# SMPS.net
KiCad netlist of a schematic drawn in Altium Designer
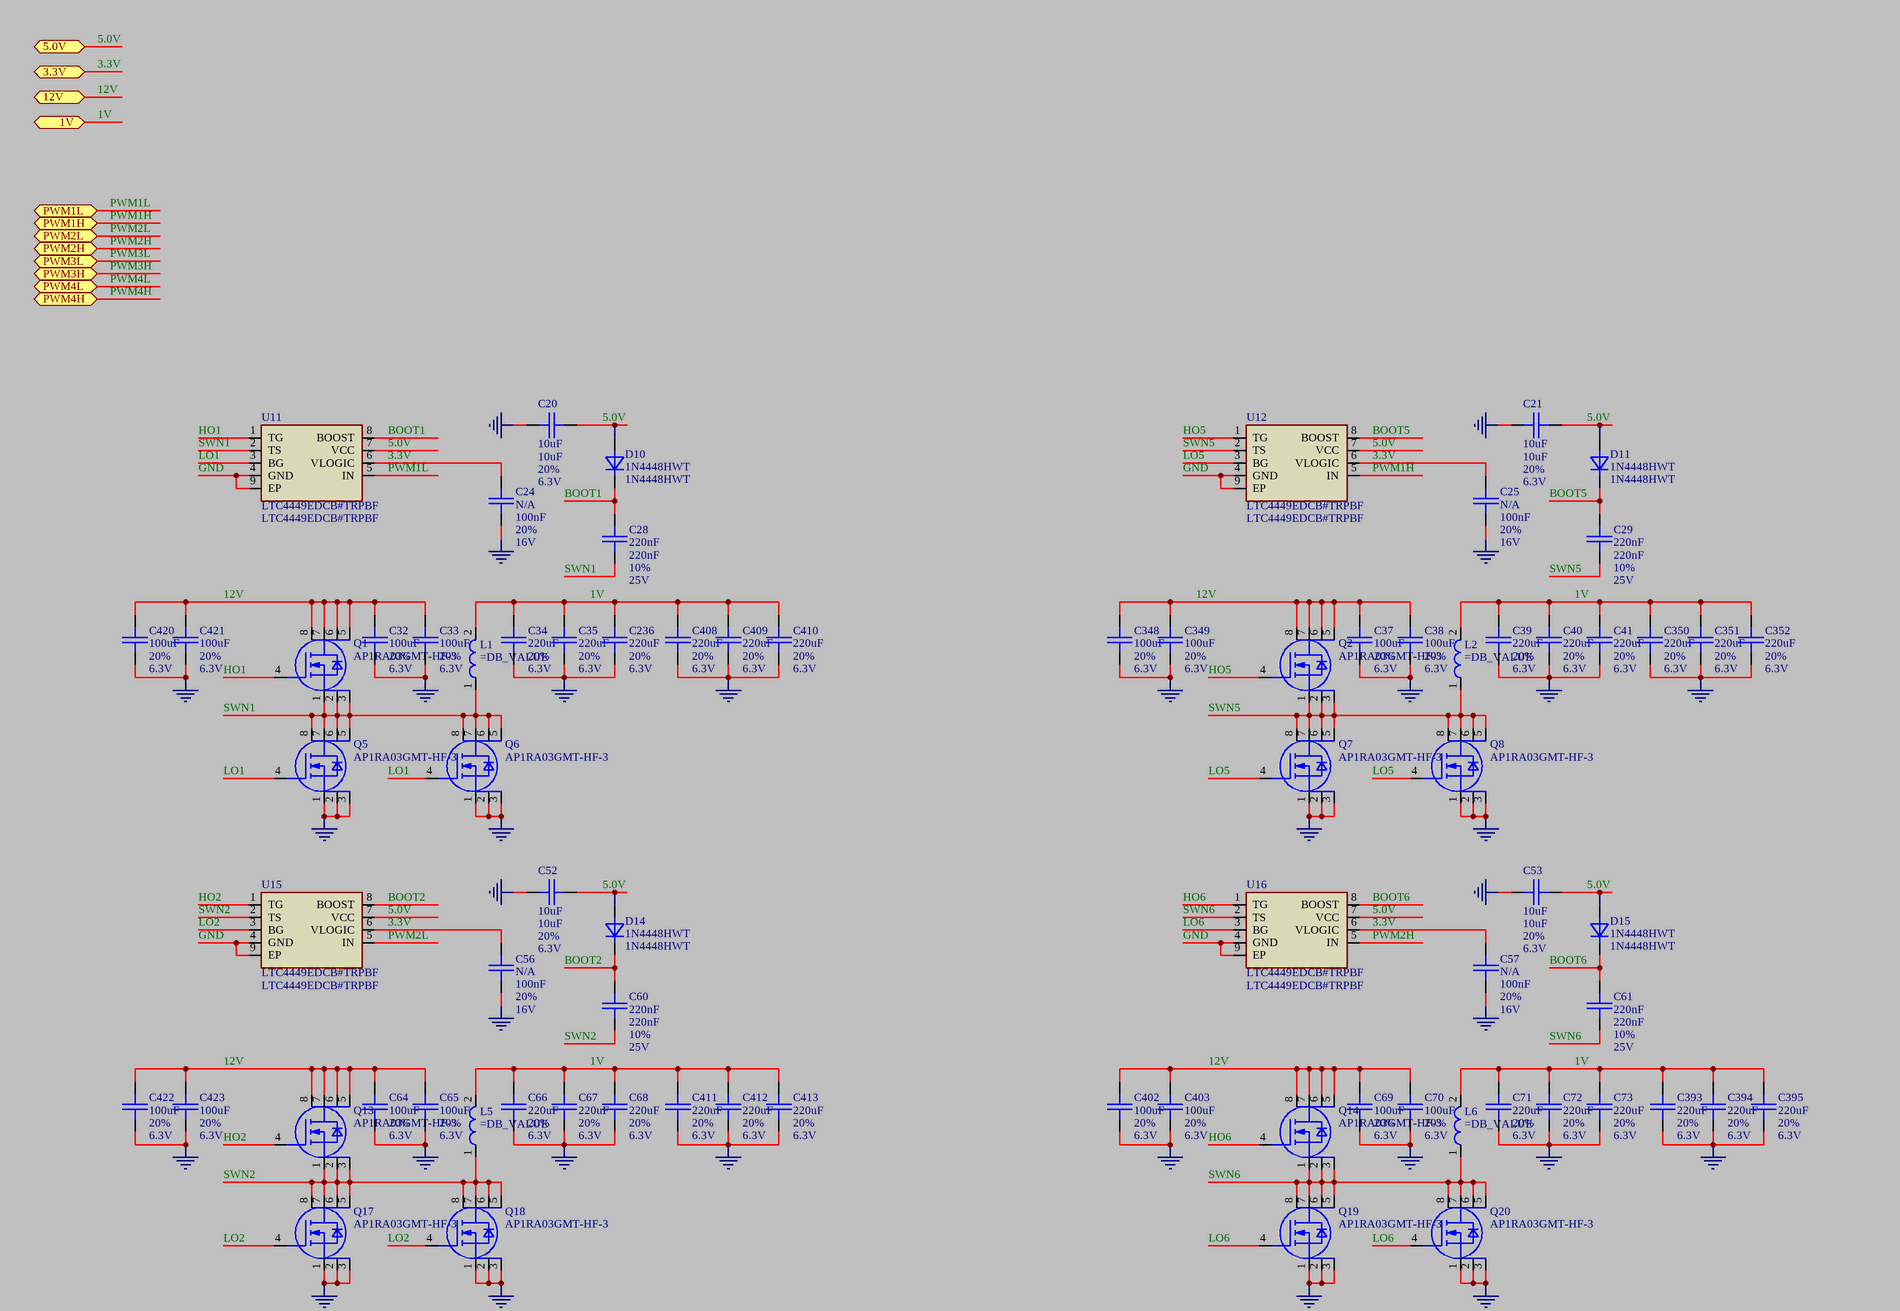
[diagram p0: SMPS.SchDoc, top left]
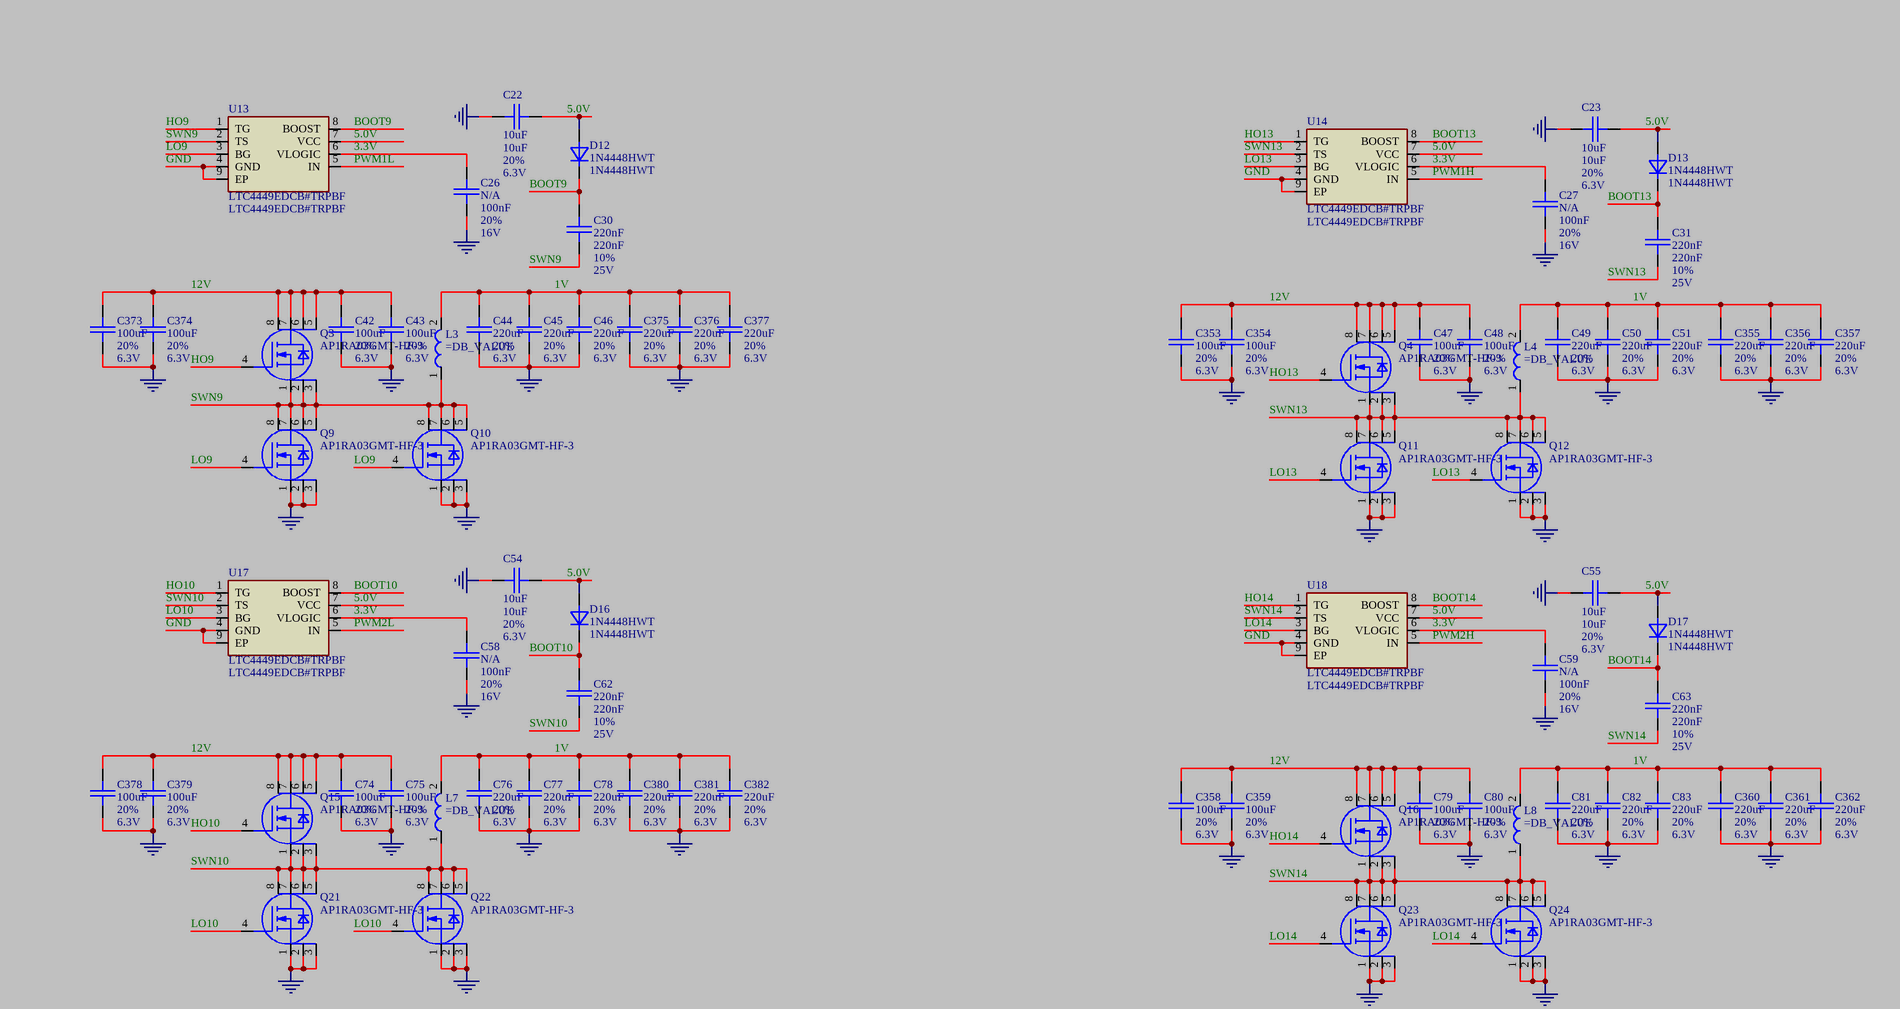
[diagram p1: SMPS.SchDoc, top right]
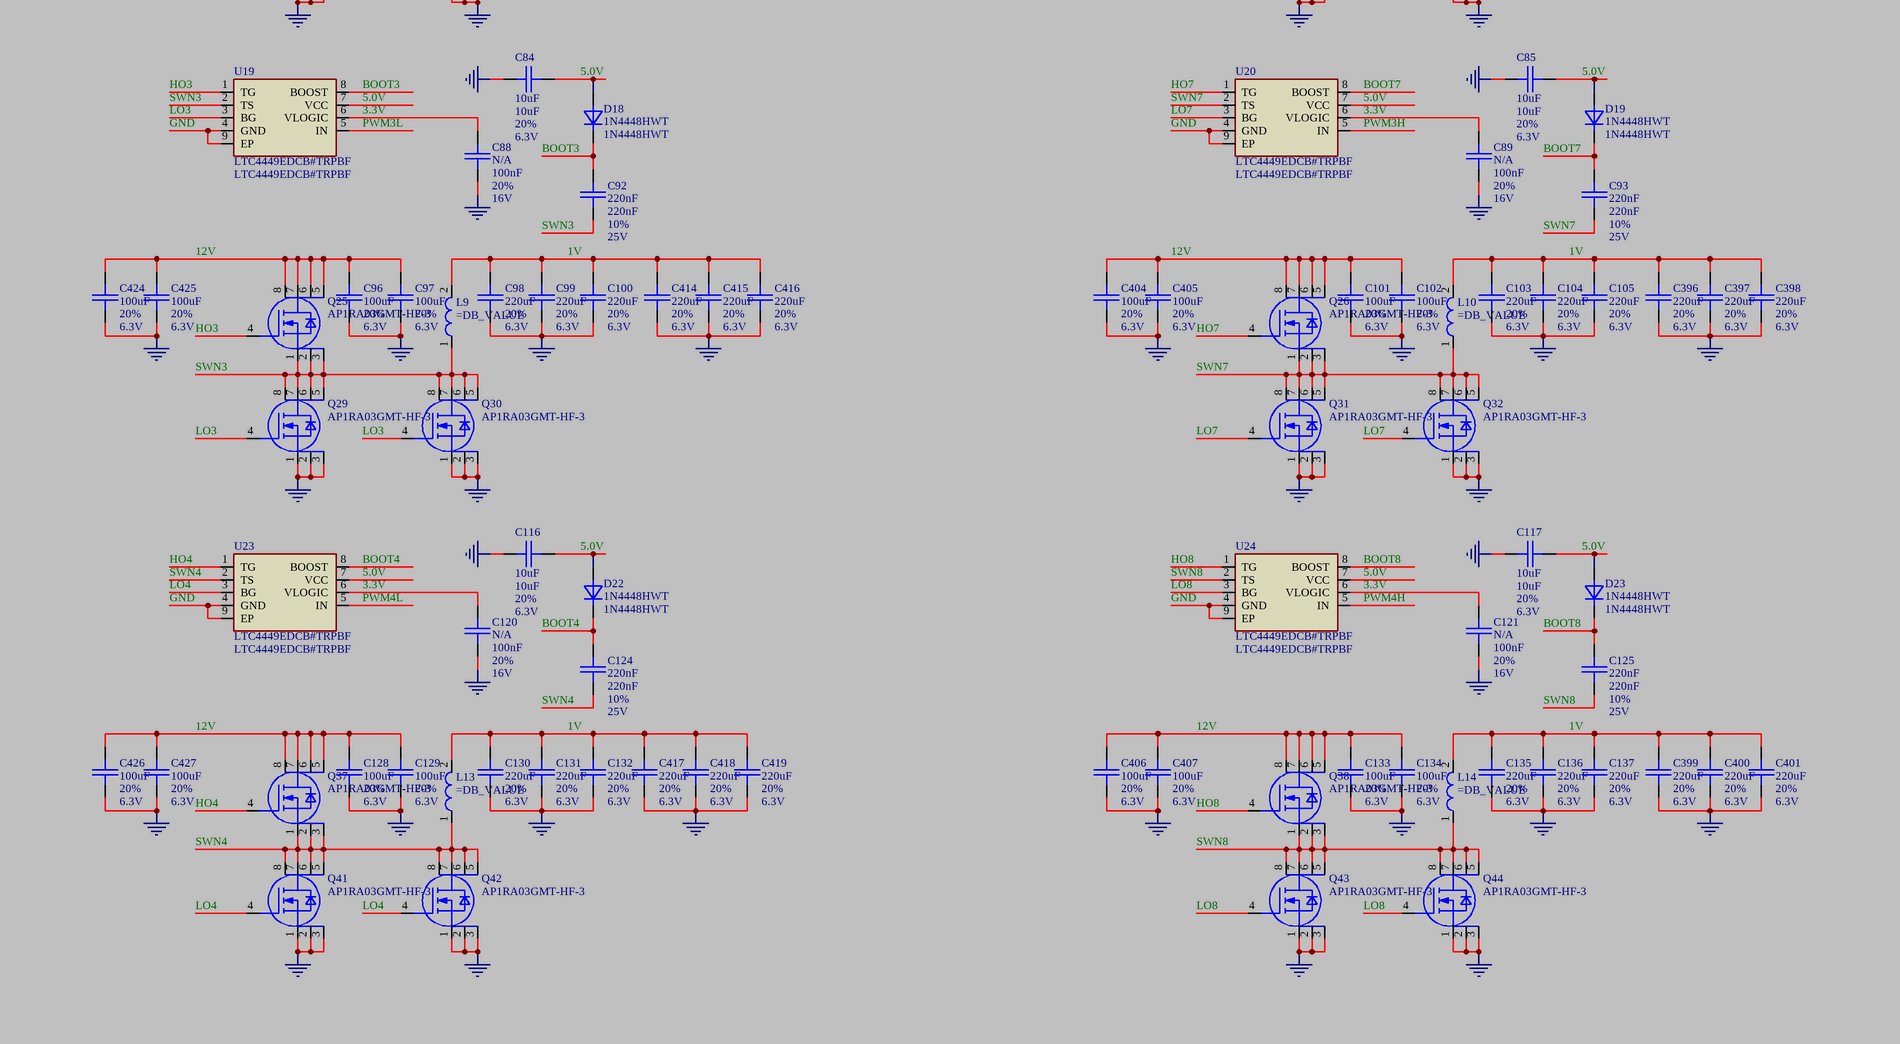
[diagram p2: SMPS.SchDoc, bottom left]
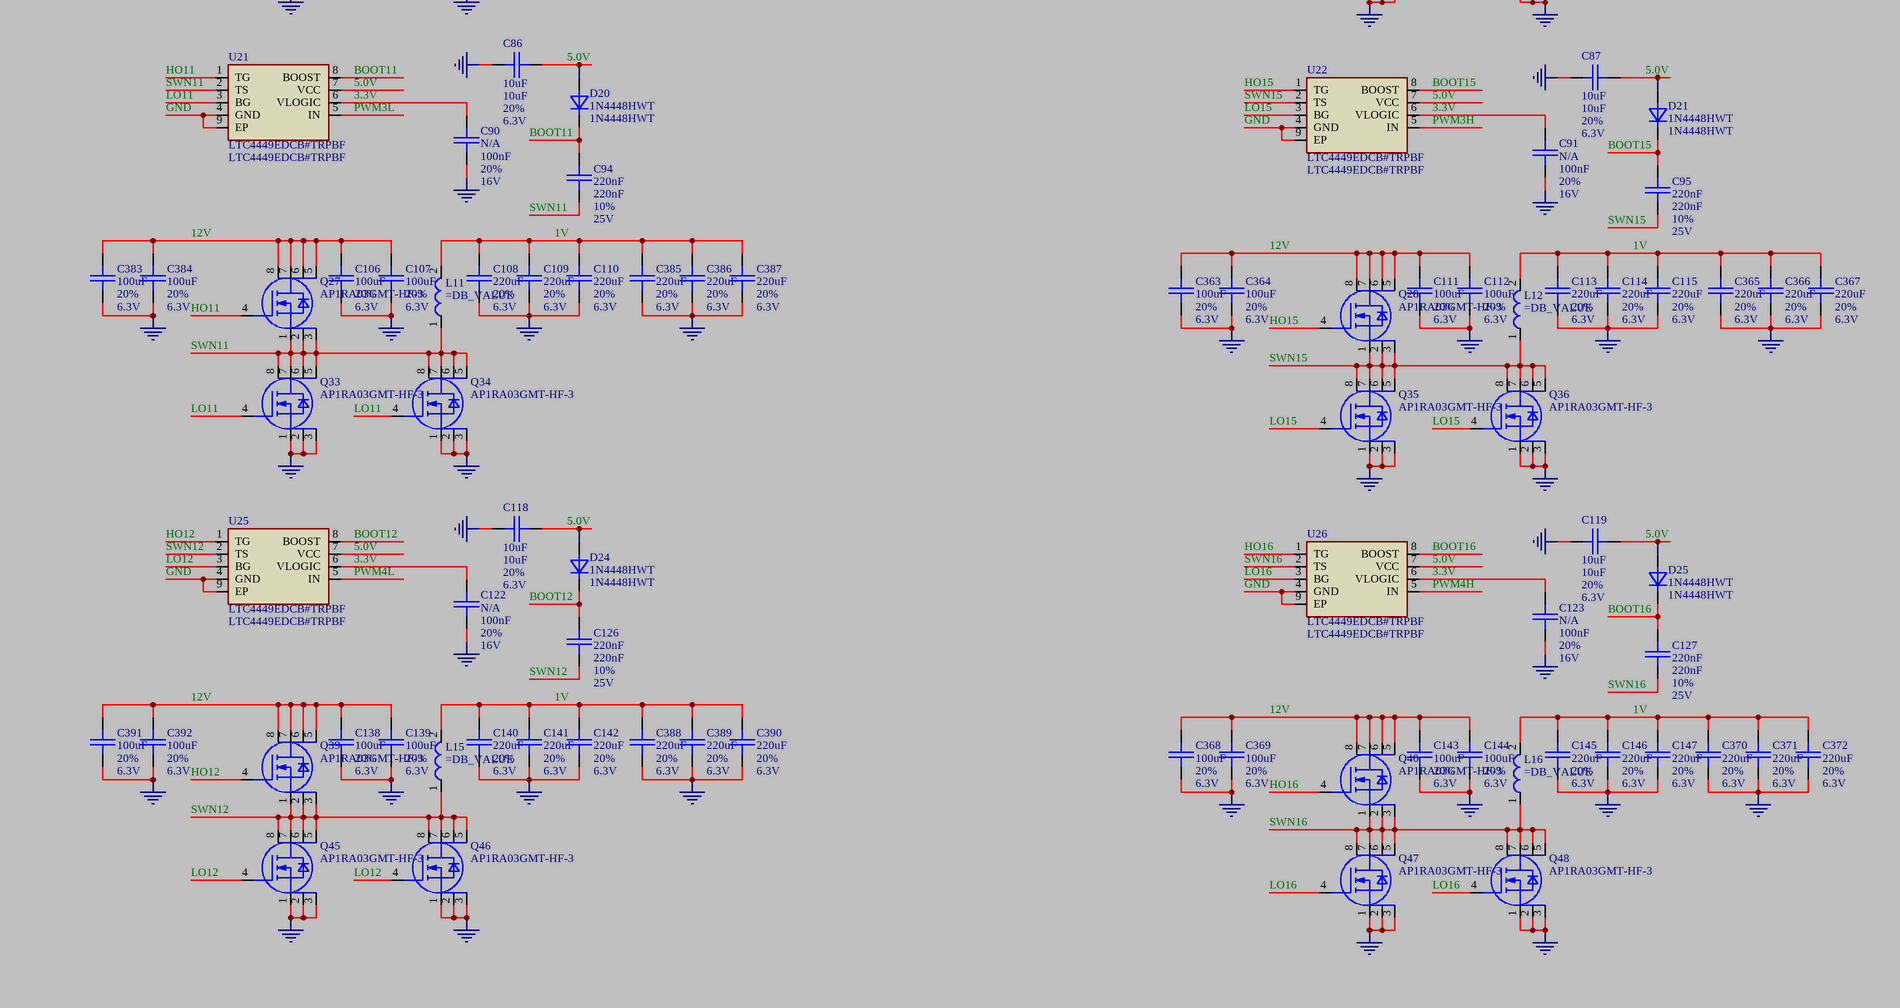
[diagram p3: SMPS.SchDoc, bottom right]

(export (version "E")
  (design (tool "Eeschema 10.0.6"))
  (components
    (comp (ref "C20")
      (value "10uF")
      (footprint "SMD_0603_CAPC1608X95N")
      (fields
        (field (name "DB_PART_NUMBER") "CAP000043646")
        (field (name "DB_VALUE") "10uF")
        (field (name "DB_TOLERANCE") "20%")
        (field (name "DB_VOLTAGE") "6.3V")
        (field (name "DB_MANUFACTURER_PART") "KEMET    C0603C106M9PAC")
      )
      (libsource (lib "Database_Libs1") (part "=DB_VALUE"))
    )
    (comp (ref "C21")
      (value "10uF")
      (footprint "SMD_0603_CAPC1608X95N")
      (fields
        (field (name "DB_PART_NUMBER") "CAP000043646")
        (field (name "DB_VALUE") "10uF")
        (field (name "DB_TOLERANCE") "20%")
        (field (name "DB_VOLTAGE") "6.3V")
        (field (name "DB_MANUFACTURER_PART") "KEMET    C0603C106M9PAC")
      )
      (libsource (lib "Database_Libs1") (part "=DB_VALUE"))
    )
    (comp (ref "C22")
      (value "10uF")
      (footprint "SMD_0603_CAPC1608X95N")
      (fields
        (field (name "DB_PART_NUMBER") "CAP000043646")
        (field (name "DB_VALUE") "10uF")
        (field (name "DB_TOLERANCE") "20%")
        (field (name "DB_VOLTAGE") "6.3V")
        (field (name "DB_MANUFACTURER_PART") "KEMET    C0603C106M9PAC")
      )
      (libsource (lib "Database_Libs1") (part "=DB_VALUE"))
    )
    (comp (ref "C23")
      (value "10uF")
      (footprint "SMD_0603_CAPC1608X95N")
      (fields
        (field (name "DB_PART_NUMBER") "CAP000043646")
        (field (name "DB_VALUE") "10uF")
        (field (name "DB_TOLERANCE") "20%")
        (field (name "DB_VOLTAGE") "6.3V")
        (field (name "DB_MANUFACTURER_PART") "KEMET    C0603C106M9PAC")
      )
      (libsource (lib "Database_Libs1") (part "=DB_VALUE"))
    )
    (comp (ref "C24")
      (value "N/A")
      (footprint "SMD_0402_CAPC1005X55N")
      (fields
        (field (name "DB_PART_NUMBER") "CAP000022751")
        (field (name "DB_VALUE") "100nF")
        (field (name "DB_TOLERANCE") "20%")
        (field (name "DB_VOLTAGE") "16V")
        (field (name "DB_MANUFACTURER_PART") "KEMET    C0402F104M4RAC")
      )
      (libsource (lib "Database_Libs1") (part "=DB_VALUE"))
    )
    (comp (ref "C25")
      (value "N/A")
      (footprint "SMD_0402_CAPC1005X55N")
      (fields
        (field (name "DB_PART_NUMBER") "CAP000022751")
        (field (name "DB_VALUE") "100nF")
        (field (name "DB_TOLERANCE") "20%")
        (field (name "DB_VOLTAGE") "16V")
        (field (name "DB_MANUFACTURER_PART") "KEMET    C0402F104M4RAC")
      )
      (libsource (lib "Database_Libs1") (part "=DB_VALUE"))
    )
    (comp (ref "C26")
      (value "N/A")
      (footprint "SMD_0402_CAPC1005X55N")
      (fields
        (field (name "DB_PART_NUMBER") "CAP000022751")
        (field (name "DB_VALUE") "100nF")
        (field (name "DB_TOLERANCE") "20%")
        (field (name "DB_VOLTAGE") "16V")
        (field (name "DB_MANUFACTURER_PART") "KEMET    C0402F104M4RAC")
      )
      (libsource (lib "Database_Libs1") (part "=DB_VALUE"))
    )
    (comp (ref "C27")
      (value "N/A")
      (footprint "SMD_0402_CAPC1005X55N")
      (fields
        (field (name "DB_PART_NUMBER") "CAP000022751")
        (field (name "DB_VALUE") "100nF")
        (field (name "DB_TOLERANCE") "20%")
        (field (name "DB_VOLTAGE") "16V")
        (field (name "DB_MANUFACTURER_PART") "KEMET    C0402F104M4RAC")
      )
      (libsource (lib "Database_Libs1") (part "=DB_VALUE"))
    )
    (comp (ref "C28")
      (value "220nF")
      (footprint "SMD_0603_CAPC1608X95N")
      (fields
        (field (name "DB_PART_NUMBER") "CAP000022968")
        (field (name "DB_VALUE") "220nF")
        (field (name "DB_TOLERANCE") "10%")
        (field (name "DB_VOLTAGE") "25V")
        (field (name "DB_MANUFACTURER_PART") "KEMET    C0603F224K3RAC")
      )
      (libsource (lib "Database_Libs1") (part "=DB_VALUE"))
    )
    (comp (ref "C29")
      (value "220nF")
      (footprint "SMD_0603_CAPC1608X95N")
      (fields
        (field (name "DB_PART_NUMBER") "CAP000022968")
        (field (name "DB_VALUE") "220nF")
        (field (name "DB_TOLERANCE") "10%")
        (field (name "DB_VOLTAGE") "25V")
        (field (name "DB_MANUFACTURER_PART") "KEMET    C0603F224K3RAC")
      )
      (libsource (lib "Database_Libs1") (part "=DB_VALUE"))
    )
    (comp (ref "C30")
      (value "220nF")
      (footprint "SMD_0603_CAPC1608X95N")
      (fields
        (field (name "DB_PART_NUMBER") "CAP000022968")
        (field (name "DB_VALUE") "220nF")
        (field (name "DB_TOLERANCE") "10%")
        (field (name "DB_VOLTAGE") "25V")
        (field (name "DB_MANUFACTURER_PART") "KEMET    C0603F224K3RAC")
      )
      (libsource (lib "Database_Libs1") (part "=DB_VALUE"))
    )
    (comp (ref "C31")
      (value "220nF")
      (footprint "SMD_0603_CAPC1608X95N")
      (fields
        (field (name "DB_PART_NUMBER") "CAP000022968")
        (field (name "DB_VALUE") "220nF")
        (field (name "DB_TOLERANCE") "10%")
        (field (name "DB_VOLTAGE") "25V")
        (field (name "DB_MANUFACTURER_PART") "KEMET    C0603F224K3RAC")
      )
      (libsource (lib "Database_Libs1") (part "=DB_VALUE"))
    )
    (comp (ref "C32")
      (value "100uF")
      (footprint "SMD_1210_CAPC3225X270N")
      (fields
        (field (name "DB_PART_NUMBER") "CAP000043701")
        (field (name "DB_VALUE") "100uF")
        (field (name "DB_TOLERANCE") "20%")
        (field (name "DB_VOLTAGE") "6.3V")
        (field (name "DB_MANUFACTURER_PART") "KEMET    C1210C107M9PAC")
      )
      (libsource (lib "Database_Libs1") (part "=DB_VALUE"))
    )
    (comp (ref "C33")
      (value "100uF")
      (footprint "SMD_1210_CAPC3225X270N")
      (fields
        (field (name "DB_PART_NUMBER") "CAP000043701")
        (field (name "DB_VALUE") "100uF")
        (field (name "DB_TOLERANCE") "20%")
        (field (name "DB_VOLTAGE") "6.3V")
        (field (name "DB_MANUFACTURER_PART") "KEMET    C1210C107M9PAC")
      )
      (libsource (lib "Database_Libs1") (part "=DB_VALUE"))
    )
    (comp (ref "C34")
      (value "220uF")
      (footprint "SMD_1210_CAPC3225X279N")
      (fields
        (field (name "DB_PART_NUMBER") "CAP000047355")
        (field (name "DB_VALUE") "220uF")
        (field (name "DB_TOLERANCE") "20%")
        (field (name "DB_VOLTAGE") "6.3V")
        (field (name "DB_MANUFACTURER_PART") "SAMSUNG    CL32A227MQVNNNE")
        (field (name "DB_APPROVED_BY") "VSN")
      )
      (libsource (lib "Database_Libs1") (part "=DB_VALUE"))
    )
    (comp (ref "C35")
      (value "220uF")
      (footprint "SMD_1210_CAPC3225X279N")
      (fields
        (field (name "DB_PART_NUMBER") "CAP000047355")
        (field (name "DB_VALUE") "220uF")
        (field (name "DB_TOLERANCE") "20%")
        (field (name "DB_VOLTAGE") "6.3V")
        (field (name "DB_MANUFACTURER_PART") "SAMSUNG    CL32A227MQVNNNE")
        (field (name "DB_APPROVED_BY") "VSN")
      )
      (libsource (lib "Database_Libs1") (part "=DB_VALUE"))
    )
    (comp (ref "C37")
      (value "100uF")
      (footprint "SMD_1210_CAPC3225X270N")
      (fields
        (field (name "DB_PART_NUMBER") "CAP000043701")
        (field (name "DB_VALUE") "100uF")
        (field (name "DB_TOLERANCE") "20%")
        (field (name "DB_VOLTAGE") "6.3V")
        (field (name "DB_MANUFACTURER_PART") "KEMET    C1210C107M9PAC")
      )
      (libsource (lib "Database_Libs1") (part "=DB_VALUE"))
    )
    (comp (ref "C38")
      (value "100uF")
      (footprint "SMD_1210_CAPC3225X270N")
      (fields
        (field (name "DB_PART_NUMBER") "CAP000043701")
        (field (name "DB_VALUE") "100uF")
        (field (name "DB_TOLERANCE") "20%")
        (field (name "DB_VOLTAGE") "6.3V")
        (field (name "DB_MANUFACTURER_PART") "KEMET    C1210C107M9PAC")
      )
      (libsource (lib "Database_Libs1") (part "=DB_VALUE"))
    )
    (comp (ref "C39")
      (value "220uF")
      (footprint "SMD_1210_CAPC3225X279N")
      (fields
        (field (name "DB_PART_NUMBER") "CAP000047355")
        (field (name "DB_VALUE") "220uF")
        (field (name "DB_TOLERANCE") "20%")
        (field (name "DB_VOLTAGE") "6.3V")
        (field (name "DB_MANUFACTURER_PART") "SAMSUNG    CL32A227MQVNNNE")
        (field (name "DB_APPROVED_BY") "VSN")
      )
      (libsource (lib "Database_Libs1") (part "=DB_VALUE"))
    )
    (comp (ref "C40")
      (value "220uF")
      (footprint "SMD_1210_CAPC3225X279N")
      (fields
        (field (name "DB_PART_NUMBER") "CAP000047355")
        (field (name "DB_VALUE") "220uF")
        (field (name "DB_TOLERANCE") "20%")
        (field (name "DB_VOLTAGE") "6.3V")
        (field (name "DB_MANUFACTURER_PART") "SAMSUNG    CL32A227MQVNNNE")
        (field (name "DB_APPROVED_BY") "VSN")
      )
      (libsource (lib "Database_Libs1") (part "=DB_VALUE"))
    )
    (comp (ref "C41")
      (value "220uF")
      (footprint "SMD_1210_CAPC3225X279N")
      (fields
        (field (name "DB_PART_NUMBER") "CAP000047355")
        (field (name "DB_VALUE") "220uF")
        (field (name "DB_TOLERANCE") "20%")
        (field (name "DB_VOLTAGE") "6.3V")
        (field (name "DB_MANUFACTURER_PART") "SAMSUNG    CL32A227MQVNNNE")
        (field (name "DB_APPROVED_BY") "VSN")
      )
      (libsource (lib "Database_Libs1") (part "=DB_VALUE"))
    )
    (comp (ref "C42")
      (value "100uF")
      (footprint "SMD_1210_CAPC3225X270N")
      (fields
        (field (name "DB_PART_NUMBER") "CAP000043701")
        (field (name "DB_VALUE") "100uF")
        (field (name "DB_TOLERANCE") "20%")
        (field (name "DB_VOLTAGE") "6.3V")
        (field (name "DB_MANUFACTURER_PART") "KEMET    C1210C107M9PAC")
      )
      (libsource (lib "Database_Libs1") (part "=DB_VALUE"))
    )
    (comp (ref "C43")
      (value "100uF")
      (footprint "SMD_1210_CAPC3225X270N")
      (fields
        (field (name "DB_PART_NUMBER") "CAP000043701")
        (field (name "DB_VALUE") "100uF")
        (field (name "DB_TOLERANCE") "20%")
        (field (name "DB_VOLTAGE") "6.3V")
        (field (name "DB_MANUFACTURER_PART") "KEMET    C1210C107M9PAC")
      )
      (libsource (lib "Database_Libs1") (part "=DB_VALUE"))
    )
    (comp (ref "C44")
      (value "220uF")
      (footprint "SMD_1210_CAPC3225X279N")
      (fields
        (field (name "DB_PART_NUMBER") "CAP000047355")
        (field (name "DB_VALUE") "220uF")
        (field (name "DB_TOLERANCE") "20%")
        (field (name "DB_VOLTAGE") "6.3V")
        (field (name "DB_MANUFACTURER_PART") "SAMSUNG    CL32A227MQVNNNE")
        (field (name "DB_APPROVED_BY") "VSN")
      )
      (libsource (lib "Database_Libs1") (part "=DB_VALUE"))
    )
    (comp (ref "C45")
      (value "220uF")
      (footprint "SMD_1210_CAPC3225X279N")
      (fields
        (field (name "DB_PART_NUMBER") "CAP000047355")
        (field (name "DB_VALUE") "220uF")
        (field (name "DB_TOLERANCE") "20%")
        (field (name "DB_VOLTAGE") "6.3V")
        (field (name "DB_MANUFACTURER_PART") "SAMSUNG    CL32A227MQVNNNE")
        (field (name "DB_APPROVED_BY") "VSN")
      )
      (libsource (lib "Database_Libs1") (part "=DB_VALUE"))
    )
    (comp (ref "C46")
      (value "220uF")
      (footprint "SMD_1210_CAPC3225X279N")
      (fields
        (field (name "DB_PART_NUMBER") "CAP000047355")
        (field (name "DB_VALUE") "220uF")
        (field (name "DB_TOLERANCE") "20%")
        (field (name "DB_VOLTAGE") "6.3V")
        (field (name "DB_MANUFACTURER_PART") "SAMSUNG    CL32A227MQVNNNE")
        (field (name "DB_APPROVED_BY") "VSN")
      )
      (libsource (lib "Database_Libs1") (part "=DB_VALUE"))
    )
    (comp (ref "C47")
      (value "100uF")
      (footprint "SMD_1210_CAPC3225X270N")
      (fields
        (field (name "DB_PART_NUMBER") "CAP000043701")
        (field (name "DB_VALUE") "100uF")
        (field (name "DB_TOLERANCE") "20%")
        (field (name "DB_VOLTAGE") "6.3V")
        (field (name "DB_MANUFACTURER_PART") "KEMET    C1210C107M9PAC")
      )
      (libsource (lib "Database_Libs1") (part "=DB_VALUE"))
    )
    (comp (ref "C48")
      (value "100uF")
      (footprint "SMD_1210_CAPC3225X270N")
      (fields
        (field (name "DB_PART_NUMBER") "CAP000043701")
        (field (name "DB_VALUE") "100uF")
        (field (name "DB_TOLERANCE") "20%")
        (field (name "DB_VOLTAGE") "6.3V")
        (field (name "DB_MANUFACTURER_PART") "KEMET    C1210C107M9PAC")
      )
      (libsource (lib "Database_Libs1") (part "=DB_VALUE"))
    )
    (comp (ref "C49")
      (value "220uF")
      (footprint "SMD_1210_CAPC3225X279N")
      (fields
        (field (name "DB_PART_NUMBER") "CAP000047355")
        (field (name "DB_VALUE") "220uF")
        (field (name "DB_TOLERANCE") "20%")
        (field (name "DB_VOLTAGE") "6.3V")
        (field (name "DB_MANUFACTURER_PART") "SAMSUNG    CL32A227MQVNNNE")
        (field (name "DB_APPROVED_BY") "VSN")
      )
      (libsource (lib "Database_Libs1") (part "=DB_VALUE"))
    )
    (comp (ref "C50")
      (value "220uF")
      (footprint "SMD_1210_CAPC3225X279N")
      (fields
        (field (name "DB_PART_NUMBER") "CAP000047355")
        (field (name "DB_VALUE") "220uF")
        (field (name "DB_TOLERANCE") "20%")
        (field (name "DB_VOLTAGE") "6.3V")
        (field (name "DB_MANUFACTURER_PART") "SAMSUNG    CL32A227MQVNNNE")
        (field (name "DB_APPROVED_BY") "VSN")
      )
      (libsource (lib "Database_Libs1") (part "=DB_VALUE"))
    )
    (comp (ref "C51")
      (value "220uF")
      (footprint "SMD_1210_CAPC3225X279N")
      (fields
        (field (name "DB_PART_NUMBER") "CAP000047355")
        (field (name "DB_VALUE") "220uF")
        (field (name "DB_TOLERANCE") "20%")
        (field (name "DB_VOLTAGE") "6.3V")
        (field (name "DB_MANUFACTURER_PART") "SAMSUNG    CL32A227MQVNNNE")
        (field (name "DB_APPROVED_BY") "VSN")
      )
      (libsource (lib "Database_Libs1") (part "=DB_VALUE"))
    )
    (comp (ref "C52")
      (value "10uF")
      (footprint "SMD_0603_CAPC1608X95N")
      (fields
        (field (name "DB_PART_NUMBER") "CAP000043646")
        (field (name "DB_VALUE") "10uF")
        (field (name "DB_TOLERANCE") "20%")
        (field (name "DB_VOLTAGE") "6.3V")
        (field (name "DB_MANUFACTURER_PART") "KEMET    C0603C106M9PAC")
      )
      (libsource (lib "Database_Libs1") (part "=DB_VALUE"))
    )
    (comp (ref "C53")
      (value "10uF")
      (footprint "SMD_0603_CAPC1608X95N")
      (fields
        (field (name "DB_PART_NUMBER") "CAP000043646")
        (field (name "DB_VALUE") "10uF")
        (field (name "DB_TOLERANCE") "20%")
        (field (name "DB_VOLTAGE") "6.3V")
        (field (name "DB_MANUFACTURER_PART") "KEMET    C0603C106M9PAC")
      )
      (libsource (lib "Database_Libs1") (part "=DB_VALUE"))
    )
    (comp (ref "C54")
      (value "10uF")
      (footprint "SMD_0603_CAPC1608X95N")
      (fields
        (field (name "DB_PART_NUMBER") "CAP000043646")
        (field (name "DB_VALUE") "10uF")
        (field (name "DB_TOLERANCE") "20%")
        (field (name "DB_VOLTAGE") "6.3V")
        (field (name "DB_MANUFACTURER_PART") "KEMET    C0603C106M9PAC")
      )
      (libsource (lib "Database_Libs1") (part "=DB_VALUE"))
    )
    (comp (ref "C55")
      (value "10uF")
      (footprint "SMD_0603_CAPC1608X95N")
      (fields
        (field (name "DB_PART_NUMBER") "CAP000043646")
        (field (name "DB_VALUE") "10uF")
        (field (name "DB_TOLERANCE") "20%")
        (field (name "DB_VOLTAGE") "6.3V")
        (field (name "DB_MANUFACTURER_PART") "KEMET    C0603C106M9PAC")
      )
      (libsource (lib "Database_Libs1") (part "=DB_VALUE"))
    )
    (comp (ref "C56")
      (value "N/A")
      (footprint "SMD_0402_CAPC1005X55N")
      (fields
        (field (name "DB_PART_NUMBER") "CAP000022751")
        (field (name "DB_VALUE") "100nF")
        (field (name "DB_TOLERANCE") "20%")
        (field (name "DB_VOLTAGE") "16V")
        (field (name "DB_MANUFACTURER_PART") "KEMET    C0402F104M4RAC")
      )
      (libsource (lib "Database_Libs1") (part "=DB_VALUE"))
    )
    (comp (ref "C57")
      (value "N/A")
      (footprint "SMD_0402_CAPC1005X55N")
      (fields
        (field (name "DB_PART_NUMBER") "CAP000022751")
        (field (name "DB_VALUE") "100nF")
        (field (name "DB_TOLERANCE") "20%")
        (field (name "DB_VOLTAGE") "16V")
        (field (name "DB_MANUFACTURER_PART") "KEMET    C0402F104M4RAC")
      )
      (libsource (lib "Database_Libs1") (part "=DB_VALUE"))
    )
    (comp (ref "C58")
      (value "N/A")
      (footprint "SMD_0402_CAPC1005X55N")
      (fields
        (field (name "DB_PART_NUMBER") "CAP000022751")
        (field (name "DB_VALUE") "100nF")
        (field (name "DB_TOLERANCE") "20%")
        (field (name "DB_VOLTAGE") "16V")
        (field (name "DB_MANUFACTURER_PART") "KEMET    C0402F104M4RAC")
      )
      (libsource (lib "Database_Libs1") (part "=DB_VALUE"))
    )
    (comp (ref "C59")
      (value "N/A")
      (footprint "SMD_0402_CAPC1005X55N")
      (fields
        (field (name "DB_PART_NUMBER") "CAP000022751")
        (field (name "DB_VALUE") "100nF")
        (field (name "DB_TOLERANCE") "20%")
        (field (name "DB_VOLTAGE") "16V")
        (field (name "DB_MANUFACTURER_PART") "KEMET    C0402F104M4RAC")
      )
      (libsource (lib "Database_Libs1") (part "=DB_VALUE"))
    )
    (comp (ref "C60")
      (value "220nF")
      (footprint "SMD_0603_CAPC1608X95N")
      (fields
        (field (name "DB_PART_NUMBER") "CAP000022968")
        (field (name "DB_VALUE") "220nF")
        (field (name "DB_TOLERANCE") "10%")
        (field (name "DB_VOLTAGE") "25V")
        (field (name "DB_MANUFACTURER_PART") "KEMET    C0603F224K3RAC")
      )
      (libsource (lib "Database_Libs1") (part "=DB_VALUE"))
    )
    (comp (ref "C61")
      (value "220nF")
      (footprint "SMD_0603_CAPC1608X95N")
      (fields
        (field (name "DB_PART_NUMBER") "CAP000022968")
        (field (name "DB_VALUE") "220nF")
        (field (name "DB_TOLERANCE") "10%")
        (field (name "DB_VOLTAGE") "25V")
        (field (name "DB_MANUFACTURER_PART") "KEMET    C0603F224K3RAC")
      )
      (libsource (lib "Database_Libs1") (part "=DB_VALUE"))
    )
    (comp (ref "C62")
      (value "220nF")
      (footprint "SMD_0603_CAPC1608X95N")
      (fields
        (field (name "DB_PART_NUMBER") "CAP000022968")
        (field (name "DB_VALUE") "220nF")
        (field (name "DB_TOLERANCE") "10%")
        (field (name "DB_VOLTAGE") "25V")
        (field (name "DB_MANUFACTURER_PART") "KEMET    C0603F224K3RAC")
      )
      (libsource (lib "Database_Libs1") (part "=DB_VALUE"))
    )
    (comp (ref "C63")
      (value "220nF")
      (footprint "SMD_0603_CAPC1608X95N")
      (fields
        (field (name "DB_PART_NUMBER") "CAP000022968")
        (field (name "DB_VALUE") "220nF")
        (field (name "DB_TOLERANCE") "10%")
        (field (name "DB_VOLTAGE") "25V")
        (field (name "DB_MANUFACTURER_PART") "KEMET    C0603F224K3RAC")
      )
      (libsource (lib "Database_Libs1") (part "=DB_VALUE"))
    )
    (comp (ref "C64")
      (value "100uF")
      (footprint "SMD_1210_CAPC3225X270N")
      (fields
        (field (name "DB_PART_NUMBER") "CAP000043701")
        (field (name "DB_VALUE") "100uF")
        (field (name "DB_TOLERANCE") "20%")
        (field (name "DB_VOLTAGE") "6.3V")
        (field (name "DB_MANUFACTURER_PART") "KEMET    C1210C107M9PAC")
      )
      (libsource (lib "Database_Libs1") (part "=DB_VALUE"))
    )
    (comp (ref "C65")
      (value "100uF")
      (footprint "SMD_1210_CAPC3225X270N")
      (fields
        (field (name "DB_PART_NUMBER") "CAP000043701")
        (field (name "DB_VALUE") "100uF")
        (field (name "DB_TOLERANCE") "20%")
        (field (name "DB_VOLTAGE") "6.3V")
        (field (name "DB_MANUFACTURER_PART") "KEMET    C1210C107M9PAC")
      )
      (libsource (lib "Database_Libs1") (part "=DB_VALUE"))
    )
    (comp (ref "C66")
      (value "220uF")
      (footprint "SMD_1210_CAPC3225X279N")
      (fields
        (field (name "DB_PART_NUMBER") "CAP000047355")
        (field (name "DB_VALUE") "220uF")
        (field (name "DB_TOLERANCE") "20%")
        (field (name "DB_VOLTAGE") "6.3V")
        (field (name "DB_MANUFACTURER_PART") "SAMSUNG    CL32A227MQVNNNE")
        (field (name "DB_APPROVED_BY") "VSN")
      )
      (libsource (lib "Database_Libs1") (part "=DB_VALUE"))
    )
    (comp (ref "C67")
      (value "220uF")
      (footprint "SMD_1210_CAPC3225X279N")
      (fields
        (field (name "DB_PART_NUMBER") "CAP000047355")
        (field (name "DB_VALUE") "220uF")
        (field (name "DB_TOLERANCE") "20%")
        (field (name "DB_VOLTAGE") "6.3V")
        (field (name "DB_MANUFACTURER_PART") "SAMSUNG    CL32A227MQVNNNE")
        (field (name "DB_APPROVED_BY") "VSN")
      )
      (libsource (lib "Database_Libs1") (part "=DB_VALUE"))
    )
    (comp (ref "C68")
      (value "220uF")
      (footprint "SMD_1210_CAPC3225X279N")
      (fields
        (field (name "DB_PART_NUMBER") "CAP000047355")
        (field (name "DB_VALUE") "220uF")
        (field (name "DB_TOLERANCE") "20%")
        (field (name "DB_VOLTAGE") "6.3V")
        (field (name "DB_MANUFACTURER_PART") "SAMSUNG    CL32A227MQVNNNE")
        (field (name "DB_APPROVED_BY") "VSN")
      )
      (libsource (lib "Database_Libs1") (part "=DB_VALUE"))
    )
    (comp (ref "C69")
      (value "100uF")
      (footprint "SMD_1210_CAPC3225X270N")
      (fields
        (field (name "DB_PART_NUMBER") "CAP000043701")
        (field (name "DB_VALUE") "100uF")
        (field (name "DB_TOLERANCE") "20%")
        (field (name "DB_VOLTAGE") "6.3V")
        (field (name "DB_MANUFACTURER_PART") "KEMET    C1210C107M9PAC")
      )
      (libsource (lib "Database_Libs1") (part "=DB_VALUE"))
    )
    (comp (ref "C70")
      (value "100uF")
      (footprint "SMD_1210_CAPC3225X270N")
      (fields
        (field (name "DB_PART_NUMBER") "CAP000043701")
        (field (name "DB_VALUE") "100uF")
        (field (name "DB_TOLERANCE") "20%")
        (field (name "DB_VOLTAGE") "6.3V")
        (field (name "DB_MANUFACTURER_PART") "KEMET    C1210C107M9PAC")
      )
      (libsource (lib "Database_Libs1") (part "=DB_VALUE"))
    )
    (comp (ref "C71")
      (value "220uF")
      (footprint "SMD_1210_CAPC3225X279N")
      (fields
        (field (name "DB_PART_NUMBER") "CAP000047355")
        (field (name "DB_VALUE") "220uF")
        (field (name "DB_TOLERANCE") "20%")
        (field (name "DB_VOLTAGE") "6.3V")
        (field (name "DB_MANUFACTURER_PART") "SAMSUNG    CL32A227MQVNNNE")
        (field (name "DB_APPROVED_BY") "VSN")
      )
      (libsource (lib "Database_Libs1") (part "=DB_VALUE"))
    )
    (comp (ref "C72")
      (value "220uF")
      (footprint "SMD_1210_CAPC3225X279N")
      (fields
        (field (name "DB_PART_NUMBER") "CAP000047355")
        (field (name "DB_VALUE") "220uF")
        (field (name "DB_TOLERANCE") "20%")
        (field (name "DB_VOLTAGE") "6.3V")
        (field (name "DB_MANUFACTURER_PART") "SAMSUNG    CL32A227MQVNNNE")
        (field (name "DB_APPROVED_BY") "VSN")
      )
      (libsource (lib "Database_Libs1") (part "=DB_VALUE"))
    )
    (comp (ref "C73")
      (value "220uF")
      (footprint "SMD_1210_CAPC3225X279N")
      (fields
        (field (name "DB_PART_NUMBER") "CAP000047355")
        (field (name "DB_VALUE") "220uF")
        (field (name "DB_TOLERANCE") "20%")
        (field (name "DB_VOLTAGE") "6.3V")
        (field (name "DB_MANUFACTURER_PART") "SAMSUNG    CL32A227MQVNNNE")
        (field (name "DB_APPROVED_BY") "VSN")
      )
      (libsource (lib "Database_Libs1") (part "=DB_VALUE"))
    )
    (comp (ref "C74")
      (value "100uF")
      (footprint "SMD_1210_CAPC3225X270N")
      (fields
        (field (name "DB_PART_NUMBER") "CAP000043701")
        (field (name "DB_VALUE") "100uF")
        (field (name "DB_TOLERANCE") "20%")
        (field (name "DB_VOLTAGE") "6.3V")
        (field (name "DB_MANUFACTURER_PART") "KEMET    C1210C107M9PAC")
      )
      (libsource (lib "Database_Libs1") (part "=DB_VALUE"))
    )
    (comp (ref "C75")
      (value "100uF")
      (footprint "SMD_1210_CAPC3225X270N")
      (fields
        (field (name "DB_PART_NUMBER") "CAP000043701")
        (field (name "DB_VALUE") "100uF")
        (field (name "DB_TOLERANCE") "20%")
        (field (name "DB_VOLTAGE") "6.3V")
        (field (name "DB_MANUFACTURER_PART") "KEMET    C1210C107M9PAC")
      )
      (libsource (lib "Database_Libs1") (part "=DB_VALUE"))
    )
    (comp (ref "C76")
      (value "220uF")
      (footprint "SMD_1210_CAPC3225X279N")
      (fields
        (field (name "DB_PART_NUMBER") "CAP000047355")
        (field (name "DB_VALUE") "220uF")
        (field (name "DB_TOLERANCE") "20%")
        (field (name "DB_VOLTAGE") "6.3V")
        (field (name "DB_MANUFACTURER_PART") "SAMSUNG    CL32A227MQVNNNE")
        (field (name "DB_APPROVED_BY") "VSN")
      )
      (libsource (lib "Database_Libs1") (part "=DB_VALUE"))
    )
    (comp (ref "C77")
      (value "220uF")
      (footprint "SMD_1210_CAPC3225X279N")
      (fields
        (field (name "DB_PART_NUMBER") "CAP000047355")
        (field (name "DB_VALUE") "220uF")
        (field (name "DB_TOLERANCE") "20%")
        (field (name "DB_VOLTAGE") "6.3V")
        (field (name "DB_MANUFACTURER_PART") "SAMSUNG    CL32A227MQVNNNE")
        (field (name "DB_APPROVED_BY") "VSN")
      )
      (libsource (lib "Database_Libs1") (part "=DB_VALUE"))
    )
    (comp (ref "C78")
      (value "220uF")
      (footprint "SMD_1210_CAPC3225X279N")
      (fields
        (field (name "DB_PART_NUMBER") "CAP000047355")
        (field (name "DB_VALUE") "220uF")
        (field (name "DB_TOLERANCE") "20%")
        (field (name "DB_VOLTAGE") "6.3V")
        (field (name "DB_MANUFACTURER_PART") "SAMSUNG    CL32A227MQVNNNE")
        (field (name "DB_APPROVED_BY") "VSN")
      )
      (libsource (lib "Database_Libs1") (part "=DB_VALUE"))
    )
    (comp (ref "C79")
      (value "100uF")
      (footprint "SMD_1210_CAPC3225X270N")
      (fields
        (field (name "DB_PART_NUMBER") "CAP000043701")
        (field (name "DB_VALUE") "100uF")
        (field (name "DB_TOLERANCE") "20%")
        (field (name "DB_VOLTAGE") "6.3V")
        (field (name "DB_MANUFACTURER_PART") "KEMET    C1210C107M9PAC")
      )
      (libsource (lib "Database_Libs1") (part "=DB_VALUE"))
    )
    (comp (ref "C80")
      (value "100uF")
      (footprint "SMD_1210_CAPC3225X270N")
      (fields
        (field (name "DB_PART_NUMBER") "CAP000043701")
        (field (name "DB_VALUE") "100uF")
        (field (name "DB_TOLERANCE") "20%")
        (field (name "DB_VOLTAGE") "6.3V")
        (field (name "DB_MANUFACTURER_PART") "KEMET    C1210C107M9PAC")
      )
      (libsource (lib "Database_Libs1") (part "=DB_VALUE"))
    )
    (comp (ref "C81")
      (value "220uF")
      (footprint "SMD_1210_CAPC3225X279N")
      (fields
        (field (name "DB_PART_NUMBER") "CAP000047355")
        (field (name "DB_VALUE") "220uF")
        (field (name "DB_TOLERANCE") "20%")
        (field (name "DB_VOLTAGE") "6.3V")
        (field (name "DB_MANUFACTURER_PART") "SAMSUNG    CL32A227MQVNNNE")
        (field (name "DB_APPROVED_BY") "VSN")
      )
      (libsource (lib "Database_Libs1") (part "=DB_VALUE"))
    )
    (comp (ref "C82")
      (value "220uF")
      (footprint "SMD_1210_CAPC3225X279N")
      (fields
        (field (name "DB_PART_NUMBER") "CAP000047355")
        (field (name "DB_VALUE") "220uF")
        (field (name "DB_TOLERANCE") "20%")
        (field (name "DB_VOLTAGE") "6.3V")
        (field (name "DB_MANUFACTURER_PART") "SAMSUNG    CL32A227MQVNNNE")
        (field (name "DB_APPROVED_BY") "VSN")
      )
      (libsource (lib "Database_Libs1") (part "=DB_VALUE"))
    )
    (comp (ref "C83")
      (value "220uF")
      (footprint "SMD_1210_CAPC3225X279N")
      (fields
        (field (name "DB_PART_NUMBER") "CAP000047355")
        (field (name "DB_VALUE") "220uF")
        (field (name "DB_TOLERANCE") "20%")
        (field (name "DB_VOLTAGE") "6.3V")
        (field (name "DB_MANUFACTURER_PART") "SAMSUNG    CL32A227MQVNNNE")
        (field (name "DB_APPROVED_BY") "VSN")
      )
      (libsource (lib "Database_Libs1") (part "=DB_VALUE"))
    )
    (comp (ref "C84")
      (value "10uF")
      (footprint "SMD_0603_CAPC1608X95N")
      (fields
        (field (name "DB_PART_NUMBER") "CAP000043646")
        (field (name "DB_VALUE") "10uF")
        (field (name "DB_TOLERANCE") "20%")
        (field (name "DB_VOLTAGE") "6.3V")
        (field (name "DB_MANUFACTURER_PART") "KEMET    C0603C106M9PAC")
      )
      (libsource (lib "Database_Libs1") (part "=DB_VALUE"))
    )
    (comp (ref "C85")
      (value "10uF")
      (footprint "SMD_0603_CAPC1608X95N")
      (fields
        (field (name "DB_PART_NUMBER") "CAP000043646")
        (field (name "DB_VALUE") "10uF")
        (field (name "DB_TOLERANCE") "20%")
        (field (name "DB_VOLTAGE") "6.3V")
        (field (name "DB_MANUFACTURER_PART") "KEMET    C0603C106M9PAC")
      )
      (libsource (lib "Database_Libs1") (part "=DB_VALUE"))
    )
    (comp (ref "C86")
      (value "10uF")
      (footprint "SMD_0603_CAPC1608X95N")
      (fields
        (field (name "DB_PART_NUMBER") "CAP000043646")
        (field (name "DB_VALUE") "10uF")
        (field (name "DB_TOLERANCE") "20%")
        (field (name "DB_VOLTAGE") "6.3V")
        (field (name "DB_MANUFACTURER_PART") "KEMET    C0603C106M9PAC")
      )
      (libsource (lib "Database_Libs1") (part "=DB_VALUE"))
    )
    (comp (ref "C87")
      (value "10uF")
      (footprint "SMD_0603_CAPC1608X95N")
      (fields
        (field (name "DB_PART_NUMBER") "CAP000043646")
        (field (name "DB_VALUE") "10uF")
        (field (name "DB_TOLERANCE") "20%")
        (field (name "DB_VOLTAGE") "6.3V")
        (field (name "DB_MANUFACTURER_PART") "KEMET    C0603C106M9PAC")
      )
      (libsource (lib "Database_Libs1") (part "=DB_VALUE"))
    )
    (comp (ref "C88")
      (value "N/A")
      (footprint "SMD_0402_CAPC1005X55N")
      (fields
        (field (name "DB_PART_NUMBER") "CAP000022751")
        (field (name "DB_VALUE") "100nF")
        (field (name "DB_TOLERANCE") "20%")
        (field (name "DB_VOLTAGE") "16V")
        (field (name "DB_MANUFACTURER_PART") "KEMET    C0402F104M4RAC")
      )
      (libsource (lib "Database_Libs1") (part "=DB_VALUE"))
    )
    (comp (ref "C89")
      (value "N/A")
      (footprint "SMD_0402_CAPC1005X55N")
      (fields
        (field (name "DB_PART_NUMBER") "CAP000022751")
        (field (name "DB_VALUE") "100nF")
        (field (name "DB_TOLERANCE") "20%")
        (field (name "DB_VOLTAGE") "16V")
        (field (name "DB_MANUFACTURER_PART") "KEMET    C0402F104M4RAC")
      )
      (libsource (lib "Database_Libs1") (part "=DB_VALUE"))
    )
    (comp (ref "C90")
      (value "N/A")
      (footprint "SMD_0402_CAPC1005X55N")
      (fields
        (field (name "DB_PART_NUMBER") "CAP000022751")
        (field (name "DB_VALUE") "100nF")
        (field (name "DB_TOLERANCE") "20%")
        (field (name "DB_VOLTAGE") "16V")
        (field (name "DB_MANUFACTURER_PART") "KEMET    C0402F104M4RAC")
      )
      (libsource (lib "Database_Libs1") (part "=DB_VALUE"))
    )
    (comp (ref "C91")
      (value "N/A")
      (footprint "SMD_0402_CAPC1005X55N")
      (fields
        (field (name "DB_PART_NUMBER") "CAP000022751")
        (field (name "DB_VALUE") "100nF")
        (field (name "DB_TOLERANCE") "20%")
        (field (name "DB_VOLTAGE") "16V")
        (field (name "DB_MANUFACTURER_PART") "KEMET    C0402F104M4RAC")
      )
      (libsource (lib "Database_Libs1") (part "=DB_VALUE"))
    )
    (comp (ref "C92")
      (value "220nF")
      (footprint "SMD_0603_CAPC1608X95N")
      (fields
        (field (name "DB_PART_NUMBER") "CAP000022968")
        (field (name "DB_VALUE") "220nF")
        (field (name "DB_TOLERANCE") "10%")
        (field (name "DB_VOLTAGE") "25V")
        (field (name "DB_MANUFACTURER_PART") "KEMET    C0603F224K3RAC")
      )
      (libsource (lib "Database_Libs1") (part "=DB_VALUE"))
    )
    (comp (ref "C93")
      (value "220nF")
      (footprint "SMD_0603_CAPC1608X95N")
      (fields
        (field (name "DB_PART_NUMBER") "CAP000022968")
        (field (name "DB_VALUE") "220nF")
        (field (name "DB_TOLERANCE") "10%")
        (field (name "DB_VOLTAGE") "25V")
        (field (name "DB_MANUFACTURER_PART") "KEMET    C0603F224K3RAC")
      )
      (libsource (lib "Database_Libs1") (part "=DB_VALUE"))
    )
    (comp (ref "C94")
      (value "220nF")
      (footprint "SMD_0603_CAPC1608X95N")
      (fields
        (field (name "DB_PART_NUMBER") "CAP000022968")
        (field (name "DB_VALUE") "220nF")
        (field (name "DB_TOLERANCE") "10%")
        (field (name "DB_VOLTAGE") "25V")
        (field (name "DB_MANUFACTURER_PART") "KEMET    C0603F224K3RAC")
      )
      (libsource (lib "Database_Libs1") (part "=DB_VALUE"))
    )
    (comp (ref "C95")
      (value "220nF")
      (footprint "SMD_0603_CAPC1608X95N")
      (fields
        (field (name "DB_PART_NUMBER") "CAP000022968")
        (field (name "DB_VALUE") "220nF")
        (field (name "DB_TOLERANCE") "10%")
        (field (name "DB_VOLTAGE") "25V")
        (field (name "DB_MANUFACTURER_PART") "KEMET    C0603F224K3RAC")
      )
      (libsource (lib "Database_Libs1") (part "=DB_VALUE"))
    )
    (comp (ref "C96")
      (value "100uF")
      (footprint "SMD_1210_CAPC3225X270N")
      (fields
        (field (name "DB_PART_NUMBER") "CAP000043701")
        (field (name "DB_VALUE") "100uF")
        (field (name "DB_TOLERANCE") "20%")
        (field (name "DB_VOLTAGE") "6.3V")
        (field (name "DB_MANUFACTURER_PART") "KEMET    C1210C107M9PAC")
      )
      (libsource (lib "Database_Libs1") (part "=DB_VALUE"))
    )
    (comp (ref "C97")
      (value "100uF")
      (footprint "SMD_1210_CAPC3225X270N")
      (fields
        (field (name "DB_PART_NUMBER") "CAP000043701")
        (field (name "DB_VALUE") "100uF")
        (field (name "DB_TOLERANCE") "20%")
        (field (name "DB_VOLTAGE") "6.3V")
        (field (name "DB_MANUFACTURER_PART") "KEMET    C1210C107M9PAC")
      )
      (libsource (lib "Database_Libs1") (part "=DB_VALUE"))
    )
    (comp (ref "C98")
      (value "220uF")
      (footprint "SMD_1210_CAPC3225X279N")
      (fields
        (field (name "DB_PART_NUMBER") "CAP000047355")
        (field (name "DB_VALUE") "220uF")
        (field (name "DB_TOLERANCE") "20%")
        (field (name "DB_VOLTAGE") "6.3V")
        (field (name "DB_MANUFACTURER_PART") "SAMSUNG    CL32A227MQVNNNE")
        (field (name "DB_APPROVED_BY") "VSN")
      )
      (libsource (lib "Database_Libs1") (part "=DB_VALUE"))
    )
    (comp (ref "C99")
      (value "220uF")
      (footprint "SMD_1210_CAPC3225X279N")
      (fields
        (field (name "DB_PART_NUMBER") "CAP000047355")
        (field (name "DB_VALUE") "220uF")
        (field (name "DB_TOLERANCE") "20%")
        (field (name "DB_VOLTAGE") "6.3V")
        (field (name "DB_MANUFACTURER_PART") "SAMSUNG    CL32A227MQVNNNE")
        (field (name "DB_APPROVED_BY") "VSN")
      )
      (libsource (lib "Database_Libs1") (part "=DB_VALUE"))
    )
    (comp (ref "C100")
      (value "220uF")
      (footprint "SMD_1210_CAPC3225X279N")
      (fields
        (field (name "DB_PART_NUMBER") "CAP000047355")
        (field (name "DB_VALUE") "220uF")
        (field (name "DB_TOLERANCE") "20%")
        (field (name "DB_VOLTAGE") "6.3V")
        (field (name "DB_MANUFACTURER_PART") "SAMSUNG    CL32A227MQVNNNE")
        (field (name "DB_APPROVED_BY") "VSN")
      )
      (libsource (lib "Database_Libs1") (part "=DB_VALUE"))
    )
    (comp (ref "C101")
      (value "100uF")
      (footprint "SMD_1210_CAPC3225X270N")
      (fields
        (field (name "DB_PART_NUMBER") "CAP000043701")
        (field (name "DB_VALUE") "100uF")
        (field (name "DB_TOLERANCE") "20%")
        (field (name "DB_VOLTAGE") "6.3V")
        (field (name "DB_MANUFACTURER_PART") "KEMET    C1210C107M9PAC")
      )
      (libsource (lib "Database_Libs1") (part "=DB_VALUE"))
    )
    (comp (ref "C102")
      (value "100uF")
      (footprint "SMD_1210_CAPC3225X270N")
      (fields
        (field (name "DB_PART_NUMBER") "CAP000043701")
        (field (name "DB_VALUE") "100uF")
        (field (name "DB_TOLERANCE") "20%")
        (field (name "DB_VOLTAGE") "6.3V")
        (field (name "DB_MANUFACTURER_PART") "KEMET    C1210C107M9PAC")
      )
      (libsource (lib "Database_Libs1") (part "=DB_VALUE"))
    )
    (comp (ref "C103")
      (value "220uF")
      (footprint "SMD_1210_CAPC3225X279N")
      (fields
        (field (name "DB_PART_NUMBER") "CAP000047355")
        (field (name "DB_VALUE") "220uF")
        (field (name "DB_TOLERANCE") "20%")
        (field (name "DB_VOLTAGE") "6.3V")
        (field (name "DB_MANUFACTURER_PART") "SAMSUNG    CL32A227MQVNNNE")
        (field (name "DB_APPROVED_BY") "VSN")
      )
      (libsource (lib "Database_Libs1") (part "=DB_VALUE"))
    )
    (comp (ref "C104")
      (value "220uF")
      (footprint "SMD_1210_CAPC3225X279N")
      (fields
        (field (name "DB_PART_NUMBER") "CAP000047355")
        (field (name "DB_VALUE") "220uF")
        (field (name "DB_TOLERANCE") "20%")
        (field (name "DB_VOLTAGE") "6.3V")
        (field (name "DB_MANUFACTURER_PART") "SAMSUNG    CL32A227MQVNNNE")
        (field (name "DB_APPROVED_BY") "VSN")
      )
      (libsource (lib "Database_Libs1") (part "=DB_VALUE"))
    )
    (comp (ref "C105")
      (value "220uF")
      (footprint "SMD_1210_CAPC3225X279N")
      (fields
        (field (name "DB_PART_NUMBER") "CAP000047355")
        (field (name "DB_VALUE") "220uF")
        (field (name "DB_TOLERANCE") "20%")
        (field (name "DB_VOLTAGE") "6.3V")
        (field (name "DB_MANUFACTURER_PART") "SAMSUNG    CL32A227MQVNNNE")
        (field (name "DB_APPROVED_BY") "VSN")
      )
      (libsource (lib "Database_Libs1") (part "=DB_VALUE"))
    )
    (comp (ref "C106")
      (value "100uF")
      (footprint "SMD_1210_CAPC3225X270N")
      (fields
        (field (name "DB_PART_NUMBER") "CAP000043701")
        (field (name "DB_VALUE") "100uF")
        (field (name "DB_TOLERANCE") "20%")
        (field (name "DB_VOLTAGE") "6.3V")
        (field (name "DB_MANUFACTURER_PART") "KEMET    C1210C107M9PAC")
      )
      (libsource (lib "Database_Libs1") (part "=DB_VALUE"))
    )
    (comp (ref "C107")
      (value "100uF")
      (footprint "SMD_1210_CAPC3225X270N")
      (fields
        (field (name "DB_PART_NUMBER") "CAP000043701")
        (field (name "DB_VALUE") "100uF")
        (field (name "DB_TOLERANCE") "20%")
        (field (name "DB_VOLTAGE") "6.3V")
        (field (name "DB_MANUFACTURER_PART") "KEMET    C1210C107M9PAC")
      )
      (libsource (lib "Database_Libs1") (part "=DB_VALUE"))
    )
    (comp (ref "C108")
      (value "220uF")
      (footprint "SMD_1210_CAPC3225X279N")
      (fields
        (field (name "DB_PART_NUMBER") "CAP000047355")
        (field (name "DB_VALUE") "220uF")
        (field (name "DB_TOLERANCE") "20%")
        (field (name "DB_VOLTAGE") "6.3V")
        (field (name "DB_MANUFACTURER_PART") "SAMSUNG    CL32A227MQVNNNE")
        (field (name "DB_APPROVED_BY") "VSN")
      )
      (libsource (lib "Database_Libs1") (part "=DB_VALUE"))
    )
    (comp (ref "C109")
      (value "220uF")
      (footprint "SMD_1210_CAPC3225X279N")
      (fields
        (field (name "DB_PART_NUMBER") "CAP000047355")
        (field (name "DB_VALUE") "220uF")
        (field (name "DB_TOLERANCE") "20%")
        (field (name "DB_VOLTAGE") "6.3V")
        (field (name "DB_MANUFACTURER_PART") "SAMSUNG    CL32A227MQVNNNE")
        (field (name "DB_APPROVED_BY") "VSN")
      )
      (libsource (lib "Database_Libs1") (part "=DB_VALUE"))
    )
    (comp (ref "C110")
      (value "220uF")
      (footprint "SMD_1210_CAPC3225X279N")
      (fields
        (field (name "DB_PART_NUMBER") "CAP000047355")
        (field (name "DB_VALUE") "220uF")
        (field (name "DB_TOLERANCE") "20%")
        (field (name "DB_VOLTAGE") "6.3V")
        (field (name "DB_MANUFACTURER_PART") "SAMSUNG    CL32A227MQVNNNE")
        (field (name "DB_APPROVED_BY") "VSN")
      )
      (libsource (lib "Database_Libs1") (part "=DB_VALUE"))
    )
    (comp (ref "C111")
      (value "100uF")
      (footprint "SMD_1210_CAPC3225X270N")
      (fields
        (field (name "DB_PART_NUMBER") "CAP000043701")
        (field (name "DB_VALUE") "100uF")
        (field (name "DB_TOLERANCE") "20%")
        (field (name "DB_VOLTAGE") "6.3V")
        (field (name "DB_MANUFACTURER_PART") "KEMET    C1210C107M9PAC")
      )
      (libsource (lib "Database_Libs1") (part "=DB_VALUE"))
    )
    (comp (ref "C112")
      (value "100uF")
      (footprint "SMD_1210_CAPC3225X270N")
      (fields
        (field (name "DB_PART_NUMBER") "CAP000043701")
        (field (name "DB_VALUE") "100uF")
        (field (name "DB_TOLERANCE") "20%")
        (field (name "DB_VOLTAGE") "6.3V")
        (field (name "DB_MANUFACTURER_PART") "KEMET    C1210C107M9PAC")
      )
      (libsource (lib "Database_Libs1") (part "=DB_VALUE"))
    )
    (comp (ref "C113")
      (value "220uF")
      (footprint "SMD_1210_CAPC3225X279N")
      (fields
        (field (name "DB_PART_NUMBER") "CAP000047355")
        (field (name "DB_VALUE") "220uF")
        (field (name "DB_TOLERANCE") "20%")
        (field (name "DB_VOLTAGE") "6.3V")
        (field (name "DB_MANUFACTURER_PART") "SAMSUNG    CL32A227MQVNNNE")
        (field (name "DB_APPROVED_BY") "VSN")
      )
      (libsource (lib "Database_Libs1") (part "=DB_VALUE"))
    )
    (comp (ref "C114")
      (value "220uF")
      (footprint "SMD_1210_CAPC3225X279N")
      (fields
        (field (name "DB_PART_NUMBER") "CAP000047355")
        (field (name "DB_VALUE") "220uF")
        (field (name "DB_TOLERANCE") "20%")
        (field (name "DB_VOLTAGE") "6.3V")
        (field (name "DB_MANUFACTURER_PART") "SAMSUNG    CL32A227MQVNNNE")
        (field (name "DB_APPROVED_BY") "VSN")
      )
      (libsource (lib "Database_Libs1") (part "=DB_VALUE"))
    )
    (comp (ref "C115")
      (value "220uF")
      (footprint "SMD_1210_CAPC3225X279N")
      (fields
        (field (name "DB_PART_NUMBER") "CAP000047355")
        (field (name "DB_VALUE") "220uF")
        (field (name "DB_TOLERANCE") "20%")
        (field (name "DB_VOLTAGE") "6.3V")
        (field (name "DB_MANUFACTURER_PART") "SAMSUNG    CL32A227MQVNNNE")
        (field (name "DB_APPROVED_BY") "VSN")
      )
      (libsource (lib "Database_Libs1") (part "=DB_VALUE"))
    )
    (comp (ref "C116")
      (value "10uF")
      (footprint "SMD_0603_CAPC1608X95N")
      (fields
        (field (name "DB_PART_NUMBER") "CAP000043646")
        (field (name "DB_VALUE") "10uF")
        (field (name "DB_TOLERANCE") "20%")
        (field (name "DB_VOLTAGE") "6.3V")
        (field (name "DB_MANUFACTURER_PART") "KEMET    C0603C106M9PAC")
      )
      (libsource (lib "Database_Libs1") (part "=DB_VALUE"))
    )
    (comp (ref "C117")
      (value "10uF")
      (footprint "SMD_0603_CAPC1608X95N")
      (fields
        (field (name "DB_PART_NUMBER") "CAP000043646")
        (field (name "DB_VALUE") "10uF")
        (field (name "DB_TOLERANCE") "20%")
        (field (name "DB_VOLTAGE") "6.3V")
        (field (name "DB_MANUFACTURER_PART") "KEMET    C0603C106M9PAC")
      )
      (libsource (lib "Database_Libs1") (part "=DB_VALUE"))
    )
    (comp (ref "C118")
      (value "10uF")
      (footprint "SMD_0603_CAPC1608X95N")
      (fields
        (field (name "DB_PART_NUMBER") "CAP000043646")
        (field (name "DB_VALUE") "10uF")
        (field (name "DB_TOLERANCE") "20%")
        (field (name "DB_VOLTAGE") "6.3V")
        (field (name "DB_MANUFACTURER_PART") "KEMET    C0603C106M9PAC")
      )
      (libsource (lib "Database_Libs1") (part "=DB_VALUE"))
    )
    (comp (ref "C119")
      (value "10uF")
      (footprint "SMD_0603_CAPC1608X95N")
      (fields
        (field (name "DB_PART_NUMBER") "CAP000043646")
        (field (name "DB_VALUE") "10uF")
        (field (name "DB_TOLERANCE") "20%")
        (field (name "DB_VOLTAGE") "6.3V")
        (field (name "DB_MANUFACTURER_PART") "KEMET    C0603C106M9PAC")
      )
      (libsource (lib "Database_Libs1") (part "=DB_VALUE"))
    )
    (comp (ref "C120")
      (value "N/A")
      (footprint "SMD_0402_CAPC1005X55N")
      (fields
        (field (name "DB_PART_NUMBER") "CAP000022751")
        (field (name "DB_VALUE") "100nF")
        (field (name "DB_TOLERANCE") "20%")
        (field (name "DB_VOLTAGE") "16V")
        (field (name "DB_MANUFACTURER_PART") "KEMET    C0402F104M4RAC")
      )
      (libsource (lib "Database_Libs1") (part "=DB_VALUE"))
    )
    (comp (ref "C121")
      (value "N/A")
      (footprint "SMD_0402_CAPC1005X55N")
      (fields
        (field (name "DB_PART_NUMBER") "CAP000022751")
        (field (name "DB_VALUE") "100nF")
        (field (name "DB_TOLERANCE") "20%")
        (field (name "DB_VOLTAGE") "16V")
        (field (name "DB_MANUFACTURER_PART") "KEMET    C0402F104M4RAC")
      )
      (libsource (lib "Database_Libs1") (part "=DB_VALUE"))
    )
    (comp (ref "C122")
      (value "N/A")
      (footprint "SMD_0402_CAPC1005X55N")
      (fields
        (field (name "DB_PART_NUMBER") "CAP000022751")
        (field (name "DB_VALUE") "100nF")
        (field (name "DB_TOLERANCE") "20%")
        (field (name "DB_VOLTAGE") "16V")
        (field (name "DB_MANUFACTURER_PART") "KEMET    C0402F104M4RAC")
      )
      (libsource (lib "Database_Libs1") (part "=DB_VALUE"))
    )
    (comp (ref "C123")
      (value "N/A")
      (footprint "SMD_0402_CAPC1005X55N")
      (fields
        (field (name "DB_PART_NUMBER") "CAP000022751")
        (field (name "DB_VALUE") "100nF")
        (field (name "DB_TOLERANCE") "20%")
        (field (name "DB_VOLTAGE") "16V")
        (field (name "DB_MANUFACTURER_PART") "KEMET    C0402F104M4RAC")
      )
      (libsource (lib "Database_Libs1") (part "=DB_VALUE"))
    )
    (comp (ref "C124")
      (value "220nF")
      (footprint "SMD_0603_CAPC1608X95N")
      (fields
        (field (name "DB_PART_NUMBER") "CAP000022968")
        (field (name "DB_VALUE") "220nF")
        (field (name "DB_TOLERANCE") "10%")
        (field (name "DB_VOLTAGE") "25V")
        (field (name "DB_MANUFACTURER_PART") "KEMET    C0603F224K3RAC")
      )
      (libsource (lib "Database_Libs1") (part "=DB_VALUE"))
    )
    (comp (ref "C125")
      (value "220nF")
      (footprint "SMD_0603_CAPC1608X95N")
      (fields
        (field (name "DB_PART_NUMBER") "CAP000022968")
        (field (name "DB_VALUE") "220nF")
        (field (name "DB_TOLERANCE") "10%")
        (field (name "DB_VOLTAGE") "25V")
        (field (name "DB_MANUFACTURER_PART") "KEMET    C0603F224K3RAC")
      )
      (libsource (lib "Database_Libs1") (part "=DB_VALUE"))
    )
    (comp (ref "C126")
      (value "220nF")
      (footprint "SMD_0603_CAPC1608X95N")
      (fields
        (field (name "DB_PART_NUMBER") "CAP000022968")
        (field (name "DB_VALUE") "220nF")
        (field (name "DB_TOLERANCE") "10%")
        (field (name "DB_VOLTAGE") "25V")
        (field (name "DB_MANUFACTURER_PART") "KEMET    C0603F224K3RAC")
      )
      (libsource (lib "Database_Libs1") (part "=DB_VALUE"))
    )
    (comp (ref "C127")
      (value "220nF")
      (footprint "SMD_0603_CAPC1608X95N")
      (fields
        (field (name "DB_PART_NUMBER") "CAP000022968")
        (field (name "DB_VALUE") "220nF")
        (field (name "DB_TOLERANCE") "10%")
        (field (name "DB_VOLTAGE") "25V")
        (field (name "DB_MANUFACTURER_PART") "KEMET    C0603F224K3RAC")
      )
      (libsource (lib "Database_Libs1") (part "=DB_VALUE"))
    )
    (comp (ref "C128")
      (value "100uF")
      (footprint "SMD_1210_CAPC3225X270N")
      (fields
        (field (name "DB_PART_NUMBER") "CAP000043701")
        (field (name "DB_VALUE") "100uF")
        (field (name "DB_TOLERANCE") "20%")
        (field (name "DB_VOLTAGE") "6.3V")
        (field (name "DB_MANUFACTURER_PART") "KEMET    C1210C107M9PAC")
      )
      (libsource (lib "Database_Libs1") (part "=DB_VALUE"))
    )
    (comp (ref "C129")
      (value "100uF")
      (footprint "SMD_1210_CAPC3225X270N")
      (fields
        (field (name "DB_PART_NUMBER") "CAP000043701")
        (field (name "DB_VALUE") "100uF")
        (field (name "DB_TOLERANCE") "20%")
        (field (name "DB_VOLTAGE") "6.3V")
        (field (name "DB_MANUFACTURER_PART") "KEMET    C1210C107M9PAC")
      )
      (libsource (lib "Database_Libs1") (part "=DB_VALUE"))
    )
    (comp (ref "C130")
      (value "220uF")
      (footprint "SMD_1210_CAPC3225X279N")
      (fields
        (field (name "DB_PART_NUMBER") "CAP000047355")
        (field (name "DB_VALUE") "220uF")
        (field (name "DB_TOLERANCE") "20%")
        (field (name "DB_VOLTAGE") "6.3V")
        (field (name "DB_MANUFACTURER_PART") "SAMSUNG    CL32A227MQVNNNE")
        (field (name "DB_APPROVED_BY") "VSN")
      )
      (libsource (lib "Database_Libs1") (part "=DB_VALUE"))
    )
    (comp (ref "C131")
      (value "220uF")
      (footprint "SMD_1210_CAPC3225X279N")
      (fields
        (field (name "DB_PART_NUMBER") "CAP000047355")
        (field (name "DB_VALUE") "220uF")
        (field (name "DB_TOLERANCE") "20%")
        (field (name "DB_VOLTAGE") "6.3V")
        (field (name "DB_MANUFACTURER_PART") "SAMSUNG    CL32A227MQVNNNE")
        (field (name "DB_APPROVED_BY") "VSN")
      )
      (libsource (lib "Database_Libs1") (part "=DB_VALUE"))
    )
    (comp (ref "C132")
      (value "220uF")
      (footprint "SMD_1210_CAPC3225X279N")
      (fields
        (field (name "DB_PART_NUMBER") "CAP000047355")
        (field (name "DB_VALUE") "220uF")
        (field (name "DB_TOLERANCE") "20%")
        (field (name "DB_VOLTAGE") "6.3V")
        (field (name "DB_MANUFACTURER_PART") "SAMSUNG    CL32A227MQVNNNE")
        (field (name "DB_APPROVED_BY") "VSN")
      )
      (libsource (lib "Database_Libs1") (part "=DB_VALUE"))
    )
    (comp (ref "C133")
      (value "100uF")
      (footprint "SMD_1210_CAPC3225X270N")
      (fields
        (field (name "DB_PART_NUMBER") "CAP000043701")
        (field (name "DB_VALUE") "100uF")
        (field (name "DB_TOLERANCE") "20%")
        (field (name "DB_VOLTAGE") "6.3V")
        (field (name "DB_MANUFACTURER_PART") "KEMET    C1210C107M9PAC")
      )
      (libsource (lib "Database_Libs1") (part "=DB_VALUE"))
    )
    (comp (ref "C134")
      (value "100uF")
      (footprint "SMD_1210_CAPC3225X270N")
      (fields
        (field (name "DB_PART_NUMBER") "CAP000043701")
        (field (name "DB_VALUE") "100uF")
        (field (name "DB_TOLERANCE") "20%")
        (field (name "DB_VOLTAGE") "6.3V")
        (field (name "DB_MANUFACTURER_PART") "KEMET    C1210C107M9PAC")
      )
      (libsource (lib "Database_Libs1") (part "=DB_VALUE"))
    )
    (comp (ref "C135")
      (value "220uF")
      (footprint "SMD_1210_CAPC3225X279N")
      (fields
        (field (name "DB_PART_NUMBER") "CAP000047355")
        (field (name "DB_VALUE") "220uF")
        (field (name "DB_TOLERANCE") "20%")
        (field (name "DB_VOLTAGE") "6.3V")
        (field (name "DB_MANUFACTURER_PART") "SAMSUNG    CL32A227MQVNNNE")
        (field (name "DB_APPROVED_BY") "VSN")
      )
      (libsource (lib "Database_Libs1") (part "=DB_VALUE"))
    )
    (comp (ref "C136")
      (value "220uF")
      (footprint "SMD_1210_CAPC3225X279N")
      (fields
        (field (name "DB_PART_NUMBER") "CAP000047355")
        (field (name "DB_VALUE") "220uF")
        (field (name "DB_TOLERANCE") "20%")
        (field (name "DB_VOLTAGE") "6.3V")
        (field (name "DB_MANUFACTURER_PART") "SAMSUNG    CL32A227MQVNNNE")
        (field (name "DB_APPROVED_BY") "VSN")
      )
      (libsource (lib "Database_Libs1") (part "=DB_VALUE"))
    )
    (comp (ref "C137")
      (value "220uF")
      (footprint "SMD_1210_CAPC3225X279N")
      (fields
        (field (name "DB_PART_NUMBER") "CAP000047355")
        (field (name "DB_VALUE") "220uF")
        (field (name "DB_TOLERANCE") "20%")
        (field (name "DB_VOLTAGE") "6.3V")
        (field (name "DB_MANUFACTURER_PART") "SAMSUNG    CL32A227MQVNNNE")
        (field (name "DB_APPROVED_BY") "VSN")
      )
      (libsource (lib "Database_Libs1") (part "=DB_VALUE"))
    )
    (comp (ref "C138")
      (value "100uF")
      (footprint "SMD_1210_CAPC3225X270N")
      (fields
        (field (name "DB_PART_NUMBER") "CAP000043701")
        (field (name "DB_VALUE") "100uF")
        (field (name "DB_TOLERANCE") "20%")
        (field (name "DB_VOLTAGE") "6.3V")
        (field (name "DB_MANUFACTURER_PART") "KEMET    C1210C107M9PAC")
      )
      (libsource (lib "Database_Libs1") (part "=DB_VALUE"))
    )
    (comp (ref "C139")
      (value "100uF")
      (footprint "SMD_1210_CAPC3225X270N")
      (fields
        (field (name "DB_PART_NUMBER") "CAP000043701")
        (field (name "DB_VALUE") "100uF")
        (field (name "DB_TOLERANCE") "20%")
        (field (name "DB_VOLTAGE") "6.3V")
        (field (name "DB_MANUFACTURER_PART") "KEMET    C1210C107M9PAC")
      )
      (libsource (lib "Database_Libs1") (part "=DB_VALUE"))
    )
    (comp (ref "C140")
      (value "220uF")
      (footprint "SMD_1210_CAPC3225X279N")
      (fields
        (field (name "DB_PART_NUMBER") "CAP000047355")
        (field (name "DB_VALUE") "220uF")
        (field (name "DB_TOLERANCE") "20%")
        (field (name "DB_VOLTAGE") "6.3V")
        (field (name "DB_MANUFACTURER_PART") "SAMSUNG    CL32A227MQVNNNE")
        (field (name "DB_APPROVED_BY") "VSN")
      )
      (libsource (lib "Database_Libs1") (part "=DB_VALUE"))
    )
    (comp (ref "C141")
      (value "220uF")
      (footprint "SMD_1210_CAPC3225X279N")
      (fields
        (field (name "DB_PART_NUMBER") "CAP000047355")
        (field (name "DB_VALUE") "220uF")
        (field (name "DB_TOLERANCE") "20%")
        (field (name "DB_VOLTAGE") "6.3V")
        (field (name "DB_MANUFACTURER_PART") "SAMSUNG    CL32A227MQVNNNE")
        (field (name "DB_APPROVED_BY") "VSN")
      )
      (libsource (lib "Database_Libs1") (part "=DB_VALUE"))
    )
    (comp (ref "C142")
      (value "220uF")
      (footprint "SMD_1210_CAPC3225X279N")
      (fields
        (field (name "DB_PART_NUMBER") "CAP000047355")
        (field (name "DB_VALUE") "220uF")
        (field (name "DB_TOLERANCE") "20%")
        (field (name "DB_VOLTAGE") "6.3V")
        (field (name "DB_MANUFACTURER_PART") "SAMSUNG    CL32A227MQVNNNE")
        (field (name "DB_APPROVED_BY") "VSN")
      )
      (libsource (lib "Database_Libs1") (part "=DB_VALUE"))
    )
    (comp (ref "C143")
      (value "100uF")
      (footprint "SMD_1210_CAPC3225X270N")
      (fields
        (field (name "DB_PART_NUMBER") "CAP000043701")
        (field (name "DB_VALUE") "100uF")
        (field (name "DB_TOLERANCE") "20%")
        (field (name "DB_VOLTAGE") "6.3V")
        (field (name "DB_MANUFACTURER_PART") "KEMET    C1210C107M9PAC")
      )
      (libsource (lib "Database_Libs1") (part "=DB_VALUE"))
    )
    (comp (ref "C144")
      (value "100uF")
      (footprint "SMD_1210_CAPC3225X270N")
      (fields
        (field (name "DB_PART_NUMBER") "CAP000043701")
        (field (name "DB_VALUE") "100uF")
        (field (name "DB_TOLERANCE") "20%")
        (field (name "DB_VOLTAGE") "6.3V")
        (field (name "DB_MANUFACTURER_PART") "KEMET    C1210C107M9PAC")
      )
      (libsource (lib "Database_Libs1") (part "=DB_VALUE"))
    )
    (comp (ref "C145")
      (value "220uF")
      (footprint "SMD_1210_CAPC3225X279N")
      (fields
        (field (name "DB_PART_NUMBER") "CAP000047355")
        (field (name "DB_VALUE") "220uF")
        (field (name "DB_TOLERANCE") "20%")
        (field (name "DB_VOLTAGE") "6.3V")
        (field (name "DB_MANUFACTURER_PART") "SAMSUNG    CL32A227MQVNNNE")
        (field (name "DB_APPROVED_BY") "VSN")
      )
      (libsource (lib "Database_Libs1") (part "=DB_VALUE"))
    )
    (comp (ref "C146")
      (value "220uF")
      (footprint "SMD_1210_CAPC3225X279N")
      (fields
        (field (name "DB_PART_NUMBER") "CAP000047355")
        (field (name "DB_VALUE") "220uF")
        (field (name "DB_TOLERANCE") "20%")
        (field (name "DB_VOLTAGE") "6.3V")
        (field (name "DB_MANUFACTURER_PART") "SAMSUNG    CL32A227MQVNNNE")
        (field (name "DB_APPROVED_BY") "VSN")
      )
      (libsource (lib "Database_Libs1") (part "=DB_VALUE"))
    )
    (comp (ref "C147")
      (value "220uF")
      (footprint "SMD_1210_CAPC3225X279N")
      (fields
        (field (name "DB_PART_NUMBER") "CAP000047355")
        (field (name "DB_VALUE") "220uF")
        (field (name "DB_TOLERANCE") "20%")
        (field (name "DB_VOLTAGE") "6.3V")
        (field (name "DB_MANUFACTURER_PART") "SAMSUNG    CL32A227MQVNNNE")
        (field (name "DB_APPROVED_BY") "VSN")
      )
      (libsource (lib "Database_Libs1") (part "=DB_VALUE"))
    )
    (comp (ref "C236")
      (value "220uF")
      (footprint "SMD_1210_CAPC3225X279N")
      (fields
        (field (name "DB_PART_NUMBER") "CAP000047355")
        (field (name "DB_VALUE") "220uF")
        (field (name "DB_TOLERANCE") "20%")
        (field (name "DB_VOLTAGE") "6.3V")
        (field (name "DB_MANUFACTURER_PART") "SAMSUNG    CL32A227MQVNNNE")
        (field (name "DB_APPROVED_BY") "VSN")
      )
      (libsource (lib "Database_Libs1") (part "=DB_VALUE"))
    )
    (comp (ref "C348")
      (value "100uF")
      (footprint "SMD_1210_CAPC3225X270N")
      (fields
        (field (name "DB_PART_NUMBER") "CAP000043701")
        (field (name "DB_VALUE") "100uF")
        (field (name "DB_TOLERANCE") "20%")
        (field (name "DB_VOLTAGE") "6.3V")
        (field (name "DB_MANUFACTURER_PART") "KEMET    C1210C107M9PAC")
      )
      (libsource (lib "Database_Libs1") (part "=DB_VALUE"))
    )
    (comp (ref "C349")
      (value "100uF")
      (footprint "SMD_1210_CAPC3225X270N")
      (fields
        (field (name "DB_PART_NUMBER") "CAP000043701")
        (field (name "DB_VALUE") "100uF")
        (field (name "DB_TOLERANCE") "20%")
        (field (name "DB_VOLTAGE") "6.3V")
        (field (name "DB_MANUFACTURER_PART") "KEMET    C1210C107M9PAC")
      )
      (libsource (lib "Database_Libs1") (part "=DB_VALUE"))
    )
    (comp (ref "C350")
      (value "220uF")
      (footprint "SMD_1210_CAPC3225X279N")
      (fields
        (field (name "DB_PART_NUMBER") "CAP000047355")
        (field (name "DB_VALUE") "220uF")
        (field (name "DB_TOLERANCE") "20%")
        (field (name "DB_VOLTAGE") "6.3V")
        (field (name "DB_MANUFACTURER_PART") "SAMSUNG    CL32A227MQVNNNE")
        (field (name "DB_APPROVED_BY") "VSN")
      )
      (libsource (lib "Database_Libs1") (part "=DB_VALUE"))
    )
    (comp (ref "C351")
      (value "220uF")
      (footprint "SMD_1210_CAPC3225X279N")
      (fields
        (field (name "DB_PART_NUMBER") "CAP000047355")
        (field (name "DB_VALUE") "220uF")
        (field (name "DB_TOLERANCE") "20%")
        (field (name "DB_VOLTAGE") "6.3V")
        (field (name "DB_MANUFACTURER_PART") "SAMSUNG    CL32A227MQVNNNE")
        (field (name "DB_APPROVED_BY") "VSN")
      )
      (libsource (lib "Database_Libs1") (part "=DB_VALUE"))
    )
    (comp (ref "C352")
      (value "220uF")
      (footprint "SMD_1210_CAPC3225X279N")
      (fields
        (field (name "DB_PART_NUMBER") "CAP000047355")
        (field (name "DB_VALUE") "220uF")
        (field (name "DB_TOLERANCE") "20%")
        (field (name "DB_VOLTAGE") "6.3V")
        (field (name "DB_MANUFACTURER_PART") "SAMSUNG    CL32A227MQVNNNE")
        (field (name "DB_APPROVED_BY") "VSN")
      )
      (libsource (lib "Database_Libs1") (part "=DB_VALUE"))
    )
    (comp (ref "C353")
      (value "100uF")
      (footprint "SMD_1210_CAPC3225X270N")
      (fields
        (field (name "DB_PART_NUMBER") "CAP000043701")
        (field (name "DB_VALUE") "100uF")
        (field (name "DB_TOLERANCE") "20%")
        (field (name "DB_VOLTAGE") "6.3V")
        (field (name "DB_MANUFACTURER_PART") "KEMET    C1210C107M9PAC")
      )
      (libsource (lib "Database_Libs1") (part "=DB_VALUE"))
    )
    (comp (ref "C354")
      (value "100uF")
      (footprint "SMD_1210_CAPC3225X270N")
      (fields
        (field (name "DB_PART_NUMBER") "CAP000043701")
        (field (name "DB_VALUE") "100uF")
        (field (name "DB_TOLERANCE") "20%")
        (field (name "DB_VOLTAGE") "6.3V")
        (field (name "DB_MANUFACTURER_PART") "KEMET    C1210C107M9PAC")
      )
      (libsource (lib "Database_Libs1") (part "=DB_VALUE"))
    )
    (comp (ref "C355")
      (value "220uF")
      (footprint "SMD_1210_CAPC3225X279N")
      (fields
        (field (name "DB_PART_NUMBER") "CAP000047355")
        (field (name "DB_VALUE") "220uF")
        (field (name "DB_TOLERANCE") "20%")
        (field (name "DB_VOLTAGE") "6.3V")
        (field (name "DB_MANUFACTURER_PART") "SAMSUNG    CL32A227MQVNNNE")
        (field (name "DB_APPROVED_BY") "VSN")
      )
      (libsource (lib "Database_Libs1") (part "=DB_VALUE"))
    )
    (comp (ref "C356")
      (value "220uF")
      (footprint "SMD_1210_CAPC3225X279N")
      (fields
        (field (name "DB_PART_NUMBER") "CAP000047355")
        (field (name "DB_VALUE") "220uF")
        (field (name "DB_TOLERANCE") "20%")
        (field (name "DB_VOLTAGE") "6.3V")
        (field (name "DB_MANUFACTURER_PART") "SAMSUNG    CL32A227MQVNNNE")
        (field (name "DB_APPROVED_BY") "VSN")
      )
      (libsource (lib "Database_Libs1") (part "=DB_VALUE"))
    )
    (comp (ref "C357")
      (value "220uF")
      (footprint "SMD_1210_CAPC3225X279N")
      (fields
        (field (name "DB_PART_NUMBER") "CAP000047355")
        (field (name "DB_VALUE") "220uF")
        (field (name "DB_TOLERANCE") "20%")
        (field (name "DB_VOLTAGE") "6.3V")
        (field (name "DB_MANUFACTURER_PART") "SAMSUNG    CL32A227MQVNNNE")
        (field (name "DB_APPROVED_BY") "VSN")
      )
      (libsource (lib "Database_Libs1") (part "=DB_VALUE"))
    )
    (comp (ref "C358")
      (value "100uF")
      (footprint "SMD_1210_CAPC3225X270N")
      (fields
        (field (name "DB_PART_NUMBER") "CAP000043701")
        (field (name "DB_VALUE") "100uF")
        (field (name "DB_TOLERANCE") "20%")
        (field (name "DB_VOLTAGE") "6.3V")
        (field (name "DB_MANUFACTURER_PART") "KEMET    C1210C107M9PAC")
      )
      (libsource (lib "Database_Libs1") (part "=DB_VALUE"))
    )
    (comp (ref "C359")
      (value "100uF")
      (footprint "SMD_1210_CAPC3225X270N")
      (fields
        (field (name "DB_PART_NUMBER") "CAP000043701")
        (field (name "DB_VALUE") "100uF")
        (field (name "DB_TOLERANCE") "20%")
        (field (name "DB_VOLTAGE") "6.3V")
        (field (name "DB_MANUFACTURER_PART") "KEMET    C1210C107M9PAC")
      )
      (libsource (lib "Database_Libs1") (part "=DB_VALUE"))
    )
    (comp (ref "C360")
      (value "220uF")
      (footprint "SMD_1210_CAPC3225X279N")
      (fields
        (field (name "DB_PART_NUMBER") "CAP000047355")
        (field (name "DB_VALUE") "220uF")
        (field (name "DB_TOLERANCE") "20%")
        (field (name "DB_VOLTAGE") "6.3V")
        (field (name "DB_MANUFACTURER_PART") "SAMSUNG    CL32A227MQVNNNE")
        (field (name "DB_APPROVED_BY") "VSN")
      )
      (libsource (lib "Database_Libs1") (part "=DB_VALUE"))
    )
    (comp (ref "C361")
      (value "220uF")
      (footprint "SMD_1210_CAPC3225X279N")
      (fields
        (field (name "DB_PART_NUMBER") "CAP000047355")
        (field (name "DB_VALUE") "220uF")
        (field (name "DB_TOLERANCE") "20%")
        (field (name "DB_VOLTAGE") "6.3V")
        (field (name "DB_MANUFACTURER_PART") "SAMSUNG    CL32A227MQVNNNE")
        (field (name "DB_APPROVED_BY") "VSN")
      )
      (libsource (lib "Database_Libs1") (part "=DB_VALUE"))
    )
    (comp (ref "C362")
      (value "220uF")
      (footprint "SMD_1210_CAPC3225X279N")
      (fields
        (field (name "DB_PART_NUMBER") "CAP000047355")
        (field (name "DB_VALUE") "220uF")
        (field (name "DB_TOLERANCE") "20%")
        (field (name "DB_VOLTAGE") "6.3V")
        (field (name "DB_MANUFACTURER_PART") "SAMSUNG    CL32A227MQVNNNE")
        (field (name "DB_APPROVED_BY") "VSN")
      )
      (libsource (lib "Database_Libs1") (part "=DB_VALUE"))
    )
    (comp (ref "C363")
      (value "100uF")
      (footprint "SMD_1210_CAPC3225X270N")
      (fields
        (field (name "DB_PART_NUMBER") "CAP000043701")
        (field (name "DB_VALUE") "100uF")
        (field (name "DB_TOLERANCE") "20%")
        (field (name "DB_VOLTAGE") "6.3V")
        (field (name "DB_MANUFACTURER_PART") "KEMET    C1210C107M9PAC")
      )
      (libsource (lib "Database_Libs1") (part "=DB_VALUE"))
    )
    (comp (ref "C364")
      (value "100uF")
      (footprint "SMD_1210_CAPC3225X270N")
      (fields
        (field (name "DB_PART_NUMBER") "CAP000043701")
        (field (name "DB_VALUE") "100uF")
        (field (name "DB_TOLERANCE") "20%")
        (field (name "DB_VOLTAGE") "6.3V")
        (field (name "DB_MANUFACTURER_PART") "KEMET    C1210C107M9PAC")
      )
      (libsource (lib "Database_Libs1") (part "=DB_VALUE"))
    )
    (comp (ref "C365")
      (value "220uF")
      (footprint "SMD_1210_CAPC3225X279N")
      (fields
        (field (name "DB_PART_NUMBER") "CAP000047355")
        (field (name "DB_VALUE") "220uF")
        (field (name "DB_TOLERANCE") "20%")
        (field (name "DB_VOLTAGE") "6.3V")
        (field (name "DB_MANUFACTURER_PART") "SAMSUNG    CL32A227MQVNNNE")
        (field (name "DB_APPROVED_BY") "VSN")
      )
      (libsource (lib "Database_Libs1") (part "=DB_VALUE"))
    )
    (comp (ref "C366")
      (value "220uF")
      (footprint "SMD_1210_CAPC3225X279N")
      (fields
        (field (name "DB_PART_NUMBER") "CAP000047355")
        (field (name "DB_VALUE") "220uF")
        (field (name "DB_TOLERANCE") "20%")
        (field (name "DB_VOLTAGE") "6.3V")
        (field (name "DB_MANUFACTURER_PART") "SAMSUNG    CL32A227MQVNNNE")
        (field (name "DB_APPROVED_BY") "VSN")
      )
      (libsource (lib "Database_Libs1") (part "=DB_VALUE"))
    )
    (comp (ref "C367")
      (value "220uF")
      (footprint "SMD_1210_CAPC3225X279N")
      (fields
        (field (name "DB_PART_NUMBER") "CAP000047355")
        (field (name "DB_VALUE") "220uF")
        (field (name "DB_TOLERANCE") "20%")
        (field (name "DB_VOLTAGE") "6.3V")
        (field (name "DB_MANUFACTURER_PART") "SAMSUNG    CL32A227MQVNNNE")
        (field (name "DB_APPROVED_BY") "VSN")
      )
      (libsource (lib "Database_Libs1") (part "=DB_VALUE"))
    )
    (comp (ref "C368")
      (value "100uF")
      (footprint "SMD_1210_CAPC3225X270N")
      (fields
        (field (name "DB_PART_NUMBER") "CAP000043701")
        (field (name "DB_VALUE") "100uF")
        (field (name "DB_TOLERANCE") "20%")
        (field (name "DB_VOLTAGE") "6.3V")
        (field (name "DB_MANUFACTURER_PART") "KEMET    C1210C107M9PAC")
      )
      (libsource (lib "Database_Libs1") (part "=DB_VALUE"))
    )
    (comp (ref "C369")
      (value "100uF")
      (footprint "SMD_1210_CAPC3225X270N")
      (fields
        (field (name "DB_PART_NUMBER") "CAP000043701")
        (field (name "DB_VALUE") "100uF")
        (field (name "DB_TOLERANCE") "20%")
        (field (name "DB_VOLTAGE") "6.3V")
        (field (name "DB_MANUFACTURER_PART") "KEMET    C1210C107M9PAC")
      )
      (libsource (lib "Database_Libs1") (part "=DB_VALUE"))
    )
    (comp (ref "C370")
      (value "220uF")
      (footprint "SMD_1210_CAPC3225X279N")
      (fields
        (field (name "DB_PART_NUMBER") "CAP000047355")
        (field (name "DB_VALUE") "220uF")
        (field (name "DB_TOLERANCE") "20%")
        (field (name "DB_VOLTAGE") "6.3V")
        (field (name "DB_MANUFACTURER_PART") "SAMSUNG    CL32A227MQVNNNE")
        (field (name "DB_APPROVED_BY") "VSN")
      )
      (libsource (lib "Database_Libs1") (part "=DB_VALUE"))
    )
    (comp (ref "C371")
      (value "220uF")
      (footprint "SMD_1210_CAPC3225X279N")
      (fields
        (field (name "DB_PART_NUMBER") "CAP000047355")
        (field (name "DB_VALUE") "220uF")
        (field (name "DB_TOLERANCE") "20%")
        (field (name "DB_VOLTAGE") "6.3V")
        (field (name "DB_MANUFACTURER_PART") "SAMSUNG    CL32A227MQVNNNE")
        (field (name "DB_APPROVED_BY") "VSN")
      )
      (libsource (lib "Database_Libs1") (part "=DB_VALUE"))
    )
    (comp (ref "C372")
      (value "220uF")
      (footprint "SMD_1210_CAPC3225X279N")
      (fields
        (field (name "DB_PART_NUMBER") "CAP000047355")
        (field (name "DB_VALUE") "220uF")
        (field (name "DB_TOLERANCE") "20%")
        (field (name "DB_VOLTAGE") "6.3V")
        (field (name "DB_MANUFACTURER_PART") "SAMSUNG    CL32A227MQVNNNE")
        (field (name "DB_APPROVED_BY") "VSN")
      )
      (libsource (lib "Database_Libs1") (part "=DB_VALUE"))
    )
    (comp (ref "C373")
      (value "100uF")
      (footprint "SMD_1210_CAPC3225X270N")
      (fields
        (field (name "DB_PART_NUMBER") "CAP000043701")
        (field (name "DB_VALUE") "100uF")
        (field (name "DB_TOLERANCE") "20%")
        (field (name "DB_VOLTAGE") "6.3V")
        (field (name "DB_MANUFACTURER_PART") "KEMET    C1210C107M9PAC")
      )
      (libsource (lib "Database_Libs1") (part "=DB_VALUE"))
    )
    (comp (ref "C374")
      (value "100uF")
      (footprint "SMD_1210_CAPC3225X270N")
      (fields
        (field (name "DB_PART_NUMBER") "CAP000043701")
        (field (name "DB_VALUE") "100uF")
        (field (name "DB_TOLERANCE") "20%")
        (field (name "DB_VOLTAGE") "6.3V")
        (field (name "DB_MANUFACTURER_PART") "KEMET    C1210C107M9PAC")
      )
      (libsource (lib "Database_Libs1") (part "=DB_VALUE"))
    )
    (comp (ref "C375")
      (value "220uF")
      (footprint "SMD_1210_CAPC3225X279N")
      (fields
        (field (name "DB_PART_NUMBER") "CAP000047355")
        (field (name "DB_VALUE") "220uF")
        (field (name "DB_TOLERANCE") "20%")
        (field (name "DB_VOLTAGE") "6.3V")
        (field (name "DB_MANUFACTURER_PART") "SAMSUNG    CL32A227MQVNNNE")
        (field (name "DB_APPROVED_BY") "VSN")
      )
      (libsource (lib "Database_Libs1") (part "=DB_VALUE"))
    )
    (comp (ref "C376")
      (value "220uF")
      (footprint "SMD_1210_CAPC3225X279N")
      (fields
        (field (name "DB_PART_NUMBER") "CAP000047355")
        (field (name "DB_VALUE") "220uF")
        (field (name "DB_TOLERANCE") "20%")
        (field (name "DB_VOLTAGE") "6.3V")
        (field (name "DB_MANUFACTURER_PART") "SAMSUNG    CL32A227MQVNNNE")
        (field (name "DB_APPROVED_BY") "VSN")
      )
      (libsource (lib "Database_Libs1") (part "=DB_VALUE"))
    )
    (comp (ref "C377")
      (value "220uF")
      (footprint "SMD_1210_CAPC3225X279N")
      (fields
        (field (name "DB_PART_NUMBER") "CAP000047355")
        (field (name "DB_VALUE") "220uF")
        (field (name "DB_TOLERANCE") "20%")
        (field (name "DB_VOLTAGE") "6.3V")
        (field (name "DB_MANUFACTURER_PART") "SAMSUNG    CL32A227MQVNNNE")
        (field (name "DB_APPROVED_BY") "VSN")
      )
      (libsource (lib "Database_Libs1") (part "=DB_VALUE"))
    )
    (comp (ref "C378")
      (value "100uF")
      (footprint "SMD_1210_CAPC3225X270N")
      (fields
        (field (name "DB_PART_NUMBER") "CAP000043701")
        (field (name "DB_VALUE") "100uF")
        (field (name "DB_TOLERANCE") "20%")
        (field (name "DB_VOLTAGE") "6.3V")
        (field (name "DB_MANUFACTURER_PART") "KEMET    C1210C107M9PAC")
      )
      (libsource (lib "Database_Libs1") (part "=DB_VALUE"))
    )
    (comp (ref "C379")
      (value "100uF")
      (footprint "SMD_1210_CAPC3225X270N")
      (fields
        (field (name "DB_PART_NUMBER") "CAP000043701")
        (field (name "DB_VALUE") "100uF")
        (field (name "DB_TOLERANCE") "20%")
        (field (name "DB_VOLTAGE") "6.3V")
        (field (name "DB_MANUFACTURER_PART") "KEMET    C1210C107M9PAC")
      )
      (libsource (lib "Database_Libs1") (part "=DB_VALUE"))
    )
    (comp (ref "C380")
      (value "220uF")
      (footprint "SMD_1210_CAPC3225X279N")
      (fields
        (field (name "DB_PART_NUMBER") "CAP000047355")
        (field (name "DB_VALUE") "220uF")
        (field (name "DB_TOLERANCE") "20%")
        (field (name "DB_VOLTAGE") "6.3V")
        (field (name "DB_MANUFACTURER_PART") "SAMSUNG    CL32A227MQVNNNE")
        (field (name "DB_APPROVED_BY") "VSN")
      )
      (libsource (lib "Database_Libs1") (part "=DB_VALUE"))
    )
    (comp (ref "C381")
      (value "220uF")
      (footprint "SMD_1210_CAPC3225X279N")
      (fields
        (field (name "DB_PART_NUMBER") "CAP000047355")
        (field (name "DB_VALUE") "220uF")
        (field (name "DB_TOLERANCE") "20%")
        (field (name "DB_VOLTAGE") "6.3V")
        (field (name "DB_MANUFACTURER_PART") "SAMSUNG    CL32A227MQVNNNE")
        (field (name "DB_APPROVED_BY") "VSN")
      )
      (libsource (lib "Database_Libs1") (part "=DB_VALUE"))
    )
    (comp (ref "C382")
      (value "220uF")
      (footprint "SMD_1210_CAPC3225X279N")
      (fields
        (field (name "DB_PART_NUMBER") "CAP000047355")
        (field (name "DB_VALUE") "220uF")
        (field (name "DB_TOLERANCE") "20%")
        (field (name "DB_VOLTAGE") "6.3V")
        (field (name "DB_MANUFACTURER_PART") "SAMSUNG    CL32A227MQVNNNE")
        (field (name "DB_APPROVED_BY") "VSN")
      )
      (libsource (lib "Database_Libs1") (part "=DB_VALUE"))
    )
    (comp (ref "C383")
      (value "100uF")
      (footprint "SMD_1210_CAPC3225X270N")
      (fields
        (field (name "DB_PART_NUMBER") "CAP000043701")
        (field (name "DB_VALUE") "100uF")
        (field (name "DB_TOLERANCE") "20%")
        (field (name "DB_VOLTAGE") "6.3V")
        (field (name "DB_MANUFACTURER_PART") "KEMET    C1210C107M9PAC")
      )
      (libsource (lib "Database_Libs1") (part "=DB_VALUE"))
    )
    (comp (ref "C384")
      (value "100uF")
      (footprint "SMD_1210_CAPC3225X270N")
      (fields
        (field (name "DB_PART_NUMBER") "CAP000043701")
        (field (name "DB_VALUE") "100uF")
        (field (name "DB_TOLERANCE") "20%")
        (field (name "DB_VOLTAGE") "6.3V")
        (field (name "DB_MANUFACTURER_PART") "KEMET    C1210C107M9PAC")
      )
      (libsource (lib "Database_Libs1") (part "=DB_VALUE"))
    )
    (comp (ref "C385")
      (value "220uF")
      (footprint "SMD_1210_CAPC3225X279N")
      (fields
        (field (name "DB_PART_NUMBER") "CAP000047355")
        (field (name "DB_VALUE") "220uF")
        (field (name "DB_TOLERANCE") "20%")
        (field (name "DB_VOLTAGE") "6.3V")
        (field (name "DB_MANUFACTURER_PART") "SAMSUNG    CL32A227MQVNNNE")
        (field (name "DB_APPROVED_BY") "VSN")
      )
      (libsource (lib "Database_Libs1") (part "=DB_VALUE"))
    )
    (comp (ref "C386")
      (value "220uF")
      (footprint "SMD_1210_CAPC3225X279N")
      (fields
        (field (name "DB_PART_NUMBER") "CAP000047355")
        (field (name "DB_VALUE") "220uF")
        (field (name "DB_TOLERANCE") "20%")
        (field (name "DB_VOLTAGE") "6.3V")
        (field (name "DB_MANUFACTURER_PART") "SAMSUNG    CL32A227MQVNNNE")
        (field (name "DB_APPROVED_BY") "VSN")
      )
      (libsource (lib "Database_Libs1") (part "=DB_VALUE"))
    )
    (comp (ref "C387")
      (value "220uF")
      (footprint "SMD_1210_CAPC3225X279N")
      (fields
        (field (name "DB_PART_NUMBER") "CAP000047355")
        (field (name "DB_VALUE") "220uF")
        (field (name "DB_TOLERANCE") "20%")
        (field (name "DB_VOLTAGE") "6.3V")
        (field (name "DB_MANUFACTURER_PART") "SAMSUNG    CL32A227MQVNNNE")
        (field (name "DB_APPROVED_BY") "VSN")
      )
      (libsource (lib "Database_Libs1") (part "=DB_VALUE"))
    )
    (comp (ref "C388")
      (value "220uF")
      (footprint "SMD_1210_CAPC3225X279N")
      (fields
        (field (name "DB_PART_NUMBER") "CAP000047355")
        (field (name "DB_VALUE") "220uF")
        (field (name "DB_TOLERANCE") "20%")
        (field (name "DB_VOLTAGE") "6.3V")
        (field (name "DB_MANUFACTURER_PART") "SAMSUNG    CL32A227MQVNNNE")
        (field (name "DB_APPROVED_BY") "VSN")
      )
      (libsource (lib "Database_Libs1") (part "=DB_VALUE"))
    )
    (comp (ref "C389")
      (value "220uF")
      (footprint "SMD_1210_CAPC3225X279N")
      (fields
        (field (name "DB_PART_NUMBER") "CAP000047355")
        (field (name "DB_VALUE") "220uF")
        (field (name "DB_TOLERANCE") "20%")
        (field (name "DB_VOLTAGE") "6.3V")
        (field (name "DB_MANUFACTURER_PART") "SAMSUNG    CL32A227MQVNNNE")
        (field (name "DB_APPROVED_BY") "VSN")
      )
      (libsource (lib "Database_Libs1") (part "=DB_VALUE"))
    )
    (comp (ref "C390")
      (value "220uF")
      (footprint "SMD_1210_CAPC3225X279N")
      (fields
        (field (name "DB_PART_NUMBER") "CAP000047355")
        (field (name "DB_VALUE") "220uF")
        (field (name "DB_TOLERANCE") "20%")
        (field (name "DB_VOLTAGE") "6.3V")
        (field (name "DB_MANUFACTURER_PART") "SAMSUNG    CL32A227MQVNNNE")
        (field (name "DB_APPROVED_BY") "VSN")
      )
      (libsource (lib "Database_Libs1") (part "=DB_VALUE"))
    )
    (comp (ref "C391")
      (value "100uF")
      (footprint "SMD_1210_CAPC3225X270N")
      (fields
        (field (name "DB_PART_NUMBER") "CAP000043701")
        (field (name "DB_VALUE") "100uF")
        (field (name "DB_TOLERANCE") "20%")
        (field (name "DB_VOLTAGE") "6.3V")
        (field (name "DB_MANUFACTURER_PART") "KEMET    C1210C107M9PAC")
      )
      (libsource (lib "Database_Libs1") (part "=DB_VALUE"))
    )
    (comp (ref "C392")
      (value "100uF")
      (footprint "SMD_1210_CAPC3225X270N")
      (fields
        (field (name "DB_PART_NUMBER") "CAP000043701")
        (field (name "DB_VALUE") "100uF")
        (field (name "DB_TOLERANCE") "20%")
        (field (name "DB_VOLTAGE") "6.3V")
        (field (name "DB_MANUFACTURER_PART") "KEMET    C1210C107M9PAC")
      )
      (libsource (lib "Database_Libs1") (part "=DB_VALUE"))
    )
    (comp (ref "C393")
      (value "220uF")
      (footprint "SMD_1210_CAPC3225X279N")
      (fields
        (field (name "DB_PART_NUMBER") "CAP000047355")
        (field (name "DB_VALUE") "220uF")
        (field (name "DB_TOLERANCE") "20%")
        (field (name "DB_VOLTAGE") "6.3V")
        (field (name "DB_MANUFACTURER_PART") "SAMSUNG    CL32A227MQVNNNE")
        (field (name "DB_APPROVED_BY") "VSN")
      )
      (libsource (lib "Database_Libs1") (part "=DB_VALUE"))
    )
    (comp (ref "C394")
      (value "220uF")
      (footprint "SMD_1210_CAPC3225X279N")
      (fields
        (field (name "DB_PART_NUMBER") "CAP000047355")
        (field (name "DB_VALUE") "220uF")
        (field (name "DB_TOLERANCE") "20%")
        (field (name "DB_VOLTAGE") "6.3V")
        (field (name "DB_MANUFACTURER_PART") "SAMSUNG    CL32A227MQVNNNE")
        (field (name "DB_APPROVED_BY") "VSN")
      )
      (libsource (lib "Database_Libs1") (part "=DB_VALUE"))
    )
    (comp (ref "C395")
      (value "220uF")
      (footprint "SMD_1210_CAPC3225X279N")
      (fields
        (field (name "DB_PART_NUMBER") "CAP000047355")
        (field (name "DB_VALUE") "220uF")
        (field (name "DB_TOLERANCE") "20%")
        (field (name "DB_VOLTAGE") "6.3V")
        (field (name "DB_MANUFACTURER_PART") "SAMSUNG    CL32A227MQVNNNE")
        (field (name "DB_APPROVED_BY") "VSN")
      )
      (libsource (lib "Database_Libs1") (part "=DB_VALUE"))
    )
    (comp (ref "C396")
      (value "220uF")
      (footprint "SMD_1210_CAPC3225X279N")
      (fields
        (field (name "DB_PART_NUMBER") "CAP000047355")
        (field (name "DB_VALUE") "220uF")
        (field (name "DB_TOLERANCE") "20%")
        (field (name "DB_VOLTAGE") "6.3V")
        (field (name "DB_MANUFACTURER_PART") "SAMSUNG    CL32A227MQVNNNE")
        (field (name "DB_APPROVED_BY") "VSN")
      )
      (libsource (lib "Database_Libs1") (part "=DB_VALUE"))
    )
    (comp (ref "C397")
      (value "220uF")
      (footprint "SMD_1210_CAPC3225X279N")
      (fields
        (field (name "DB_PART_NUMBER") "CAP000047355")
        (field (name "DB_VALUE") "220uF")
        (field (name "DB_TOLERANCE") "20%")
        (field (name "DB_VOLTAGE") "6.3V")
        (field (name "DB_MANUFACTURER_PART") "SAMSUNG    CL32A227MQVNNNE")
        (field (name "DB_APPROVED_BY") "VSN")
      )
      (libsource (lib "Database_Libs1") (part "=DB_VALUE"))
    )
    (comp (ref "C398")
      (value "220uF")
      (footprint "SMD_1210_CAPC3225X279N")
      (fields
        (field (name "DB_PART_NUMBER") "CAP000047355")
        (field (name "DB_VALUE") "220uF")
        (field (name "DB_TOLERANCE") "20%")
        (field (name "DB_VOLTAGE") "6.3V")
        (field (name "DB_MANUFACTURER_PART") "SAMSUNG    CL32A227MQVNNNE")
        (field (name "DB_APPROVED_BY") "VSN")
      )
      (libsource (lib "Database_Libs1") (part "=DB_VALUE"))
    )
    (comp (ref "C399")
      (value "220uF")
      (footprint "SMD_1210_CAPC3225X279N")
      (fields
        (field (name "DB_PART_NUMBER") "CAP000047355")
        (field (name "DB_VALUE") "220uF")
        (field (name "DB_TOLERANCE") "20%")
        (field (name "DB_VOLTAGE") "6.3V")
        (field (name "DB_MANUFACTURER_PART") "SAMSUNG    CL32A227MQVNNNE")
        (field (name "DB_APPROVED_BY") "VSN")
      )
      (libsource (lib "Database_Libs1") (part "=DB_VALUE"))
    )
    (comp (ref "C400")
      (value "220uF")
      (footprint "SMD_1210_CAPC3225X279N")
      (fields
        (field (name "DB_PART_NUMBER") "CAP000047355")
        (field (name "DB_VALUE") "220uF")
        (field (name "DB_TOLERANCE") "20%")
        (field (name "DB_VOLTAGE") "6.3V")
        (field (name "DB_MANUFACTURER_PART") "SAMSUNG    CL32A227MQVNNNE")
        (field (name "DB_APPROVED_BY") "VSN")
      )
      (libsource (lib "Database_Libs1") (part "=DB_VALUE"))
    )
    (comp (ref "C401")
      (value "220uF")
      (footprint "SMD_1210_CAPC3225X279N")
      (fields
        (field (name "DB_PART_NUMBER") "CAP000047355")
        (field (name "DB_VALUE") "220uF")
        (field (name "DB_TOLERANCE") "20%")
        (field (name "DB_VOLTAGE") "6.3V")
        (field (name "DB_MANUFACTURER_PART") "SAMSUNG    CL32A227MQVNNNE")
        (field (name "DB_APPROVED_BY") "VSN")
      )
      (libsource (lib "Database_Libs1") (part "=DB_VALUE"))
    )
    (comp (ref "C402")
      (value "100uF")
      (footprint "SMD_1210_CAPC3225X270N")
      (fields
        (field (name "DB_PART_NUMBER") "CAP000043701")
        (field (name "DB_VALUE") "100uF")
        (field (name "DB_TOLERANCE") "20%")
        (field (name "DB_VOLTAGE") "6.3V")
        (field (name "DB_MANUFACTURER_PART") "KEMET    C1210C107M9PAC")
      )
      (libsource (lib "Database_Libs1") (part "=DB_VALUE"))
    )
    (comp (ref "C403")
      (value "100uF")
      (footprint "SMD_1210_CAPC3225X270N")
      (fields
        (field (name "DB_PART_NUMBER") "CAP000043701")
        (field (name "DB_VALUE") "100uF")
        (field (name "DB_TOLERANCE") "20%")
        (field (name "DB_VOLTAGE") "6.3V")
        (field (name "DB_MANUFACTURER_PART") "KEMET    C1210C107M9PAC")
      )
      (libsource (lib "Database_Libs1") (part "=DB_VALUE"))
    )
    (comp (ref "C404")
      (value "100uF")
      (footprint "SMD_1210_CAPC3225X270N")
      (fields
        (field (name "DB_PART_NUMBER") "CAP000043701")
        (field (name "DB_VALUE") "100uF")
        (field (name "DB_TOLERANCE") "20%")
        (field (name "DB_VOLTAGE") "6.3V")
        (field (name "DB_MANUFACTURER_PART") "KEMET    C1210C107M9PAC")
      )
      (libsource (lib "Database_Libs1") (part "=DB_VALUE"))
    )
    (comp (ref "C405")
      (value "100uF")
      (footprint "SMD_1210_CAPC3225X270N")
      (fields
        (field (name "DB_PART_NUMBER") "CAP000043701")
        (field (name "DB_VALUE") "100uF")
        (field (name "DB_TOLERANCE") "20%")
        (field (name "DB_VOLTAGE") "6.3V")
        (field (name "DB_MANUFACTURER_PART") "KEMET    C1210C107M9PAC")
      )
      (libsource (lib "Database_Libs1") (part "=DB_VALUE"))
    )
    (comp (ref "C406")
      (value "100uF")
      (footprint "SMD_1210_CAPC3225X270N")
      (fields
        (field (name "DB_PART_NUMBER") "CAP000043701")
        (field (name "DB_VALUE") "100uF")
        (field (name "DB_TOLERANCE") "20%")
        (field (name "DB_VOLTAGE") "6.3V")
        (field (name "DB_MANUFACTURER_PART") "KEMET    C1210C107M9PAC")
      )
      (libsource (lib "Database_Libs1") (part "=DB_VALUE"))
    )
    (comp (ref "C407")
      (value "100uF")
      (footprint "SMD_1210_CAPC3225X270N")
      (fields
        (field (name "DB_PART_NUMBER") "CAP000043701")
        (field (name "DB_VALUE") "100uF")
        (field (name "DB_TOLERANCE") "20%")
        (field (name "DB_VOLTAGE") "6.3V")
        (field (name "DB_MANUFACTURER_PART") "KEMET    C1210C107M9PAC")
      )
      (libsource (lib "Database_Libs1") (part "=DB_VALUE"))
    )
    (comp (ref "C408")
      (value "220uF")
      (footprint "SMD_1210_CAPC3225X279N")
      (fields
        (field (name "DB_PART_NUMBER") "CAP000047355")
        (field (name "DB_VALUE") "220uF")
        (field (name "DB_TOLERANCE") "20%")
        (field (name "DB_VOLTAGE") "6.3V")
        (field (name "DB_MANUFACTURER_PART") "SAMSUNG    CL32A227MQVNNNE")
        (field (name "DB_APPROVED_BY") "VSN")
      )
      (libsource (lib "Database_Libs1") (part "=DB_VALUE"))
    )
    (comp (ref "C409")
      (value "220uF")
      (footprint "SMD_1210_CAPC3225X279N")
      (fields
        (field (name "DB_PART_NUMBER") "CAP000047355")
        (field (name "DB_VALUE") "220uF")
        (field (name "DB_TOLERANCE") "20%")
        (field (name "DB_VOLTAGE") "6.3V")
        (field (name "DB_MANUFACTURER_PART") "SAMSUNG    CL32A227MQVNNNE")
        (field (name "DB_APPROVED_BY") "VSN")
      )
      (libsource (lib "Database_Libs1") (part "=DB_VALUE"))
    )
    (comp (ref "C410")
      (value "220uF")
      (footprint "SMD_1210_CAPC3225X279N")
      (fields
        (field (name "DB_PART_NUMBER") "CAP000047355")
        (field (name "DB_VALUE") "220uF")
        (field (name "DB_TOLERANCE") "20%")
        (field (name "DB_VOLTAGE") "6.3V")
        (field (name "DB_MANUFACTURER_PART") "SAMSUNG    CL32A227MQVNNNE")
        (field (name "DB_APPROVED_BY") "VSN")
      )
      (libsource (lib "Database_Libs1") (part "=DB_VALUE"))
    )
    (comp (ref "C411")
      (value "220uF")
      (footprint "SMD_1210_CAPC3225X279N")
      (fields
        (field (name "DB_PART_NUMBER") "CAP000047355")
        (field (name "DB_VALUE") "220uF")
        (field (name "DB_TOLERANCE") "20%")
        (field (name "DB_VOLTAGE") "6.3V")
        (field (name "DB_MANUFACTURER_PART") "SAMSUNG    CL32A227MQVNNNE")
        (field (name "DB_APPROVED_BY") "VSN")
      )
      (libsource (lib "Database_Libs1") (part "=DB_VALUE"))
    )
    (comp (ref "C412")
      (value "220uF")
      (footprint "SMD_1210_CAPC3225X279N")
      (fields
        (field (name "DB_PART_NUMBER") "CAP000047355")
        (field (name "DB_VALUE") "220uF")
        (field (name "DB_TOLERANCE") "20%")
        (field (name "DB_VOLTAGE") "6.3V")
        (field (name "DB_MANUFACTURER_PART") "SAMSUNG    CL32A227MQVNNNE")
        (field (name "DB_APPROVED_BY") "VSN")
      )
      (libsource (lib "Database_Libs1") (part "=DB_VALUE"))
    )
    (comp (ref "C413")
      (value "220uF")
      (footprint "SMD_1210_CAPC3225X279N")
      (fields
        (field (name "DB_PART_NUMBER") "CAP000047355")
        (field (name "DB_VALUE") "220uF")
        (field (name "DB_TOLERANCE") "20%")
        (field (name "DB_VOLTAGE") "6.3V")
        (field (name "DB_MANUFACTURER_PART") "SAMSUNG    CL32A227MQVNNNE")
        (field (name "DB_APPROVED_BY") "VSN")
      )
      (libsource (lib "Database_Libs1") (part "=DB_VALUE"))
    )
    (comp (ref "C414")
      (value "220uF")
      (footprint "SMD_1210_CAPC3225X279N")
      (fields
        (field (name "DB_PART_NUMBER") "CAP000047355")
        (field (name "DB_VALUE") "220uF")
        (field (name "DB_TOLERANCE") "20%")
        (field (name "DB_VOLTAGE") "6.3V")
        (field (name "DB_MANUFACTURER_PART") "SAMSUNG    CL32A227MQVNNNE")
        (field (name "DB_APPROVED_BY") "VSN")
      )
      (libsource (lib "Database_Libs1") (part "=DB_VALUE"))
    )
    (comp (ref "C415")
      (value "220uF")
      (footprint "SMD_1210_CAPC3225X279N")
      (fields
        (field (name "DB_PART_NUMBER") "CAP000047355")
        (field (name "DB_VALUE") "220uF")
        (field (name "DB_TOLERANCE") "20%")
        (field (name "DB_VOLTAGE") "6.3V")
        (field (name "DB_MANUFACTURER_PART") "SAMSUNG    CL32A227MQVNNNE")
        (field (name "DB_APPROVED_BY") "VSN")
      )
      (libsource (lib "Database_Libs1") (part "=DB_VALUE"))
    )
    (comp (ref "C416")
      (value "220uF")
      (footprint "SMD_1210_CAPC3225X279N")
      (fields
        (field (name "DB_PART_NUMBER") "CAP000047355")
        (field (name "DB_VALUE") "220uF")
        (field (name "DB_TOLERANCE") "20%")
        (field (name "DB_VOLTAGE") "6.3V")
        (field (name "DB_MANUFACTURER_PART") "SAMSUNG    CL32A227MQVNNNE")
        (field (name "DB_APPROVED_BY") "VSN")
      )
      (libsource (lib "Database_Libs1") (part "=DB_VALUE"))
    )
    (comp (ref "C417")
      (value "220uF")
      (footprint "SMD_1210_CAPC3225X279N")
      (fields
        (field (name "DB_PART_NUMBER") "CAP000047355")
        (field (name "DB_VALUE") "220uF")
        (field (name "DB_TOLERANCE") "20%")
        (field (name "DB_VOLTAGE") "6.3V")
        (field (name "DB_MANUFACTURER_PART") "SAMSUNG    CL32A227MQVNNNE")
        (field (name "DB_APPROVED_BY") "VSN")
      )
      (libsource (lib "Database_Libs1") (part "=DB_VALUE"))
    )
    (comp (ref "C418")
      (value "220uF")
      (footprint "SMD_1210_CAPC3225X279N")
      (fields
        (field (name "DB_PART_NUMBER") "CAP000047355")
        (field (name "DB_VALUE") "220uF")
        (field (name "DB_TOLERANCE") "20%")
        (field (name "DB_VOLTAGE") "6.3V")
        (field (name "DB_MANUFACTURER_PART") "SAMSUNG    CL32A227MQVNNNE")
        (field (name "DB_APPROVED_BY") "VSN")
      )
      (libsource (lib "Database_Libs1") (part "=DB_VALUE"))
    )
    (comp (ref "C419")
      (value "220uF")
      (footprint "SMD_1210_CAPC3225X279N")
      (fields
        (field (name "DB_PART_NUMBER") "CAP000047355")
        (field (name "DB_VALUE") "220uF")
        (field (name "DB_TOLERANCE") "20%")
        (field (name "DB_VOLTAGE") "6.3V")
        (field (name "DB_MANUFACTURER_PART") "SAMSUNG    CL32A227MQVNNNE")
        (field (name "DB_APPROVED_BY") "VSN")
      )
      (libsource (lib "Database_Libs1") (part "=DB_VALUE"))
    )
    (comp (ref "C420")
      (value "100uF")
      (footprint "SMD_1210_CAPC3225X270N")
      (fields
        (field (name "DB_PART_NUMBER") "CAP000043701")
        (field (name "DB_VALUE") "100uF")
        (field (name "DB_TOLERANCE") "20%")
        (field (name "DB_VOLTAGE") "6.3V")
        (field (name "DB_MANUFACTURER_PART") "KEMET    C1210C107M9PAC")
      )
      (libsource (lib "Database_Libs1") (part "=DB_VALUE"))
    )
    (comp (ref "C421")
      (value "100uF")
      (footprint "SMD_1210_CAPC3225X270N")
      (fields
        (field (name "DB_PART_NUMBER") "CAP000043701")
        (field (name "DB_VALUE") "100uF")
        (field (name "DB_TOLERANCE") "20%")
        (field (name "DB_VOLTAGE") "6.3V")
        (field (name "DB_MANUFACTURER_PART") "KEMET    C1210C107M9PAC")
      )
      (libsource (lib "Database_Libs1") (part "=DB_VALUE"))
    )
    (comp (ref "C422")
      (value "100uF")
      (footprint "SMD_1210_CAPC3225X270N")
      (fields
        (field (name "DB_PART_NUMBER") "CAP000043701")
        (field (name "DB_VALUE") "100uF")
        (field (name "DB_TOLERANCE") "20%")
        (field (name "DB_VOLTAGE") "6.3V")
        (field (name "DB_MANUFACTURER_PART") "KEMET    C1210C107M9PAC")
      )
      (libsource (lib "Database_Libs1") (part "=DB_VALUE"))
    )
    (comp (ref "C423")
      (value "100uF")
      (footprint "SMD_1210_CAPC3225X270N")
      (fields
        (field (name "DB_PART_NUMBER") "CAP000043701")
        (field (name "DB_VALUE") "100uF")
        (field (name "DB_TOLERANCE") "20%")
        (field (name "DB_VOLTAGE") "6.3V")
        (field (name "DB_MANUFACTURER_PART") "KEMET    C1210C107M9PAC")
      )
      (libsource (lib "Database_Libs1") (part "=DB_VALUE"))
    )
    (comp (ref "C424")
      (value "100uF")
      (footprint "SMD_1210_CAPC3225X270N")
      (fields
        (field (name "DB_PART_NUMBER") "CAP000043701")
        (field (name "DB_VALUE") "100uF")
        (field (name "DB_TOLERANCE") "20%")
        (field (name "DB_VOLTAGE") "6.3V")
        (field (name "DB_MANUFACTURER_PART") "KEMET    C1210C107M9PAC")
      )
      (libsource (lib "Database_Libs1") (part "=DB_VALUE"))
    )
    (comp (ref "C425")
      (value "100uF")
      (footprint "SMD_1210_CAPC3225X270N")
      (fields
        (field (name "DB_PART_NUMBER") "CAP000043701")
        (field (name "DB_VALUE") "100uF")
        (field (name "DB_TOLERANCE") "20%")
        (field (name "DB_VOLTAGE") "6.3V")
        (field (name "DB_MANUFACTURER_PART") "KEMET    C1210C107M9PAC")
      )
      (libsource (lib "Database_Libs1") (part "=DB_VALUE"))
    )
    (comp (ref "C426")
      (value "100uF")
      (footprint "SMD_1210_CAPC3225X270N")
      (fields
        (field (name "DB_PART_NUMBER") "CAP000043701")
        (field (name "DB_VALUE") "100uF")
        (field (name "DB_TOLERANCE") "20%")
        (field (name "DB_VOLTAGE") "6.3V")
        (field (name "DB_MANUFACTURER_PART") "KEMET    C1210C107M9PAC")
      )
      (libsource (lib "Database_Libs1") (part "=DB_VALUE"))
    )
    (comp (ref "C427")
      (value "100uF")
      (footprint "SMD_1210_CAPC3225X270N")
      (fields
        (field (name "DB_PART_NUMBER") "CAP000043701")
        (field (name "DB_VALUE") "100uF")
        (field (name "DB_TOLERANCE") "20%")
        (field (name "DB_VOLTAGE") "6.3V")
        (field (name "DB_MANUFACTURER_PART") "KEMET    C1210C107M9PAC")
      )
      (libsource (lib "Database_Libs1") (part "=DB_VALUE"))
    )
    (comp (ref "D10")
      (value "1N4448HWT")
      (footprint "SMD_SOD523_SOD1608X65N")
      (fields
        (field (name "DB_PART_NUMBER") "DDE000001203")
        (field (name "DB_VALUE") "1N4448HWT")
        (field (name "DB_MANUFACTURER_PART") "Diodes        1N4448HWT")
      )
      (libsource (lib "") (part "=DB_VALUE_3"))
    )
    (comp (ref "D11")
      (value "1N4448HWT")
      (footprint "SMD_SOD523_SOD1608X65N")
      (fields
        (field (name "DB_PART_NUMBER") "DDE000001203")
        (field (name "DB_VALUE") "1N4448HWT")
        (field (name "DB_MANUFACTURER_PART") "Diodes        1N4448HWT")
      )
      (libsource (lib "") (part "=DB_VALUE_3"))
    )
    (comp (ref "D12")
      (value "1N4448HWT")
      (footprint "SMD_SOD523_SOD1608X65N")
      (fields
        (field (name "DB_PART_NUMBER") "DDE000001203")
        (field (name "DB_VALUE") "1N4448HWT")
        (field (name "DB_MANUFACTURER_PART") "Diodes        1N4448HWT")
      )
      (libsource (lib "") (part "=DB_VALUE_3"))
    )
    (comp (ref "D13")
      (value "1N4448HWT")
      (footprint "SMD_SOD523_SOD1608X65N")
      (fields
        (field (name "DB_PART_NUMBER") "DDE000001203")
        (field (name "DB_VALUE") "1N4448HWT")
        (field (name "DB_MANUFACTURER_PART") "Diodes        1N4448HWT")
      )
      (libsource (lib "") (part "=DB_VALUE_3"))
    )
    (comp (ref "D14")
      (value "1N4448HWT")
      (footprint "SMD_SOD523_SOD1608X65N")
      (fields
        (field (name "DB_PART_NUMBER") "DDE000001203")
        (field (name "DB_VALUE") "1N4448HWT")
        (field (name "DB_MANUFACTURER_PART") "Diodes        1N4448HWT")
      )
      (libsource (lib "") (part "=DB_VALUE_3"))
    )
    (comp (ref "D15")
      (value "1N4448HWT")
      (footprint "SMD_SOD523_SOD1608X65N")
      (fields
        (field (name "DB_PART_NUMBER") "DDE000001203")
        (field (name "DB_VALUE") "1N4448HWT")
        (field (name "DB_MANUFACTURER_PART") "Diodes        1N4448HWT")
      )
      (libsource (lib "") (part "=DB_VALUE_3"))
    )
    (comp (ref "D16")
      (value "1N4448HWT")
      (footprint "SMD_SOD523_SOD1608X65N")
      (fields
        (field (name "DB_PART_NUMBER") "DDE000001203")
        (field (name "DB_VALUE") "1N4448HWT")
        (field (name "DB_MANUFACTURER_PART") "Diodes        1N4448HWT")
      )
      (libsource (lib "") (part "=DB_VALUE_3"))
    )
    (comp (ref "D17")
      (value "1N4448HWT")
      (footprint "SMD_SOD523_SOD1608X65N")
      (fields
        (field (name "DB_PART_NUMBER") "DDE000001203")
        (field (name "DB_VALUE") "1N4448HWT")
        (field (name "DB_MANUFACTURER_PART") "Diodes        1N4448HWT")
      )
      (libsource (lib "") (part "=DB_VALUE_3"))
    )
    (comp (ref "D18")
      (value "1N4448HWT")
      (footprint "SMD_SOD523_SOD1608X65N")
      (fields
        (field (name "DB_PART_NUMBER") "DDE000001203")
        (field (name "DB_VALUE") "1N4448HWT")
        (field (name "DB_MANUFACTURER_PART") "Diodes        1N4448HWT")
      )
      (libsource (lib "") (part "=DB_VALUE_3"))
    )
    (comp (ref "D19")
      (value "1N4448HWT")
      (footprint "SMD_SOD523_SOD1608X65N")
      (fields
        (field (name "DB_PART_NUMBER") "DDE000001203")
        (field (name "DB_VALUE") "1N4448HWT")
        (field (name "DB_MANUFACTURER_PART") "Diodes        1N4448HWT")
      )
      (libsource (lib "") (part "=DB_VALUE_3"))
    )
    (comp (ref "D20")
      (value "1N4448HWT")
      (footprint "SMD_SOD523_SOD1608X65N")
      (fields
        (field (name "DB_PART_NUMBER") "DDE000001203")
        (field (name "DB_VALUE") "1N4448HWT")
        (field (name "DB_MANUFACTURER_PART") "Diodes        1N4448HWT")
      )
      (libsource (lib "") (part "=DB_VALUE_3"))
    )
    (comp (ref "D21")
      (value "1N4448HWT")
      (footprint "SMD_SOD523_SOD1608X65N")
      (fields
        (field (name "DB_PART_NUMBER") "DDE000001203")
        (field (name "DB_VALUE") "1N4448HWT")
        (field (name "DB_MANUFACTURER_PART") "Diodes        1N4448HWT")
      )
      (libsource (lib "") (part "=DB_VALUE_3"))
    )
    (comp (ref "D22")
      (value "1N4448HWT")
      (footprint "SMD_SOD523_SOD1608X65N")
      (fields
        (field (name "DB_PART_NUMBER") "DDE000001203")
        (field (name "DB_VALUE") "1N4448HWT")
        (field (name "DB_MANUFACTURER_PART") "Diodes        1N4448HWT")
      )
      (libsource (lib "") (part "=DB_VALUE_3"))
    )
    (comp (ref "D23")
      (value "1N4448HWT")
      (footprint "SMD_SOD523_SOD1608X65N")
      (fields
        (field (name "DB_PART_NUMBER") "DDE000001203")
        (field (name "DB_VALUE") "1N4448HWT")
        (field (name "DB_MANUFACTURER_PART") "Diodes        1N4448HWT")
      )
      (libsource (lib "") (part "=DB_VALUE_3"))
    )
    (comp (ref "D24")
      (value "1N4448HWT")
      (footprint "SMD_SOD523_SOD1608X65N")
      (fields
        (field (name "DB_PART_NUMBER") "DDE000001203")
        (field (name "DB_VALUE") "1N4448HWT")
        (field (name "DB_MANUFACTURER_PART") "Diodes        1N4448HWT")
      )
      (libsource (lib "") (part "=DB_VALUE_3"))
    )
    (comp (ref "D25")
      (value "1N4448HWT")
      (footprint "SMD_SOD523_SOD1608X65N")
      (fields
        (field (name "DB_PART_NUMBER") "DDE000001203")
        (field (name "DB_VALUE") "1N4448HWT")
        (field (name "DB_MANUFACTURER_PART") "Diodes        1N4448HWT")
      )
      (libsource (lib "") (part "=DB_VALUE_3"))
    )
    (comp (ref "L1")
      (value "~")
      (footprint "SMT_INDM135130X800N")
      (libsource (lib "EPIQ_DND_CIS_Library") (part "=DB_VALUE"))
    )
    (comp (ref "L2")
      (value "~")
      (footprint "SMT_INDM135130X800N")
      (libsource (lib "EPIQ_DND_CIS_Library") (part "=DB_VALUE"))
    )
    (comp (ref "L3")
      (value "~")
      (footprint "SMT_INDM135130X800N")
      (libsource (lib "EPIQ_DND_CIS_Library") (part "=DB_VALUE"))
    )
    (comp (ref "L4")
      (value "~")
      (footprint "SMT_INDM135130X800N")
      (libsource (lib "EPIQ_DND_CIS_Library") (part "=DB_VALUE"))
    )
    (comp (ref "L5")
      (value "~")
      (footprint "SMT_INDM135130X800N")
      (libsource (lib "EPIQ_DND_CIS_Library") (part "=DB_VALUE"))
    )
    (comp (ref "L6")
      (value "~")
      (footprint "SMT_INDM135130X800N")
      (libsource (lib "EPIQ_DND_CIS_Library") (part "=DB_VALUE"))
    )
    (comp (ref "L7")
      (value "~")
      (footprint "SMT_INDM135130X800N")
      (libsource (lib "EPIQ_DND_CIS_Library") (part "=DB_VALUE"))
    )
    (comp (ref "L8")
      (value "~")
      (footprint "SMT_INDM135130X800N")
      (libsource (lib "EPIQ_DND_CIS_Library") (part "=DB_VALUE"))
    )
    (comp (ref "L9")
      (value "~")
      (footprint "SMT_INDM135130X800N")
      (libsource (lib "EPIQ_DND_CIS_Library") (part "=DB_VALUE"))
    )
    (comp (ref "L10")
      (value "~")
      (footprint "SMT_INDM135130X800N")
      (libsource (lib "EPIQ_DND_CIS_Library") (part "=DB_VALUE"))
    )
    (comp (ref "L11")
      (value "~")
      (footprint "SMT_INDM135130X800N")
      (libsource (lib "EPIQ_DND_CIS_Library") (part "=DB_VALUE"))
    )
    (comp (ref "L12")
      (value "~")
      (footprint "SMT_INDM135130X800N")
      (libsource (lib "EPIQ_DND_CIS_Library") (part "=DB_VALUE"))
    )
    (comp (ref "L13")
      (value "~")
      (footprint "SMT_INDM135130X800N")
      (libsource (lib "EPIQ_DND_CIS_Library") (part "=DB_VALUE"))
    )
    (comp (ref "L14")
      (value "~")
      (footprint "SMT_INDM135130X800N")
      (libsource (lib "EPIQ_DND_CIS_Library") (part "=DB_VALUE"))
    )
    (comp (ref "L15")
      (value "~")
      (footprint "SMT_INDM135130X800N")
      (libsource (lib "EPIQ_DND_CIS_Library") (part "=DB_VALUE"))
    )
    (comp (ref "L16")
      (value "~")
      (footprint "SMT_INDM135130X800N")
      (libsource (lib "EPIQ_DND_CIS_Library") (part "=DB_VALUE"))
    )
    (comp (ref "Q1")
      (value "AP1RA03GMT-HF-3")
      (footprint "SMD_SOIC127P600X110-9AN")
      (fields
        (field (name "DB_PART_NUMBER") "TRA000001604")
        (field (name "DB_VALUE") "AP1RA03GMT-HF-3")
        (field (name "DB_MANUFACTURER_PART") "ADVANCED POWER ELECTRONICS CORP      AP1RA03GMT-HF-3")
        (field (name "DB_APPROVED_BY") "VSN")
      )
      (libsource (lib "") (part "=DB_VALUE_2"))
    )
    (comp (ref "Q2")
      (value "AP1RA03GMT-HF-3")
      (footprint "SMD_SOIC127P600X110-9AN")
      (fields
        (field (name "DB_PART_NUMBER") "TRA000001604")
        (field (name "DB_VALUE") "AP1RA03GMT-HF-3")
        (field (name "DB_MANUFACTURER_PART") "ADVANCED POWER ELECTRONICS CORP      AP1RA03GMT-HF-3")
        (field (name "DB_APPROVED_BY") "VSN")
      )
      (libsource (lib "") (part "=DB_VALUE_2"))
    )
    (comp (ref "Q3")
      (value "AP1RA03GMT-HF-3")
      (footprint "SMD_SOIC127P600X110-9AN")
      (fields
        (field (name "DB_PART_NUMBER") "TRA000001604")
        (field (name "DB_VALUE") "AP1RA03GMT-HF-3")
        (field (name "DB_MANUFACTURER_PART") "ADVANCED POWER ELECTRONICS CORP      AP1RA03GMT-HF-3")
        (field (name "DB_APPROVED_BY") "VSN")
      )
      (libsource (lib "") (part "=DB_VALUE_2"))
    )
    (comp (ref "Q4")
      (value "AP1RA03GMT-HF-3")
      (footprint "SMD_SOIC127P600X110-9AN")
      (fields
        (field (name "DB_PART_NUMBER") "TRA000001604")
        (field (name "DB_VALUE") "AP1RA03GMT-HF-3")
        (field (name "DB_MANUFACTURER_PART") "ADVANCED POWER ELECTRONICS CORP      AP1RA03GMT-HF-3")
        (field (name "DB_APPROVED_BY") "VSN")
      )
      (libsource (lib "") (part "=DB_VALUE_2"))
    )
    (comp (ref "Q5")
      (value "AP1RA03GMT-HF-3")
      (footprint "SMD_SOIC127P600X110-9AN")
      (fields
        (field (name "DB_PART_NUMBER") "TRA000001604")
        (field (name "DB_VALUE") "AP1RA03GMT-HF-3")
        (field (name "DB_MANUFACTURER_PART") "ADVANCED POWER ELECTRONICS CORP      AP1RA03GMT-HF-3")
        (field (name "DB_APPROVED_BY") "VSN")
      )
      (libsource (lib "") (part "=DB_VALUE_2"))
    )
    (comp (ref "Q6")
      (value "AP1RA03GMT-HF-3")
      (footprint "SMD_SOIC127P600X110-9AN")
      (fields
        (field (name "DB_PART_NUMBER") "TRA000001604")
        (field (name "DB_VALUE") "AP1RA03GMT-HF-3")
        (field (name "DB_MANUFACTURER_PART") "ADVANCED POWER ELECTRONICS CORP      AP1RA03GMT-HF-3")
        (field (name "DB_APPROVED_BY") "VSN")
      )
      (libsource (lib "") (part "=DB_VALUE_2"))
    )
    (comp (ref "Q7")
      (value "AP1RA03GMT-HF-3")
      (footprint "SMD_SOIC127P600X110-9AN")
      (fields
        (field (name "DB_PART_NUMBER") "TRA000001604")
        (field (name "DB_VALUE") "AP1RA03GMT-HF-3")
        (field (name "DB_MANUFACTURER_PART") "ADVANCED POWER ELECTRONICS CORP      AP1RA03GMT-HF-3")
        (field (name "DB_APPROVED_BY") "VSN")
      )
      (libsource (lib "") (part "=DB_VALUE_2"))
    )
    (comp (ref "Q8")
      (value "AP1RA03GMT-HF-3")
      (footprint "SMD_SOIC127P600X110-9AN")
      (fields
        (field (name "DB_PART_NUMBER") "TRA000001604")
        (field (name "DB_VALUE") "AP1RA03GMT-HF-3")
        (field (name "DB_MANUFACTURER_PART") "ADVANCED POWER ELECTRONICS CORP      AP1RA03GMT-HF-3")
        (field (name "DB_APPROVED_BY") "VSN")
      )
      (libsource (lib "") (part "=DB_VALUE_2"))
    )
    (comp (ref "Q9")
      (value "AP1RA03GMT-HF-3")
      (footprint "SMD_SOIC127P600X110-9AN")
      (fields
        (field (name "DB_PART_NUMBER") "TRA000001604")
        (field (name "DB_VALUE") "AP1RA03GMT-HF-3")
        (field (name "DB_MANUFACTURER_PART") "ADVANCED POWER ELECTRONICS CORP      AP1RA03GMT-HF-3")
        (field (name "DB_APPROVED_BY") "VSN")
      )
      (libsource (lib "") (part "=DB_VALUE_2"))
    )
    (comp (ref "Q10")
      (value "AP1RA03GMT-HF-3")
      (footprint "SMD_SOIC127P600X110-9AN")
      (fields
        (field (name "DB_PART_NUMBER") "TRA000001604")
        (field (name "DB_VALUE") "AP1RA03GMT-HF-3")
        (field (name "DB_MANUFACTURER_PART") "ADVANCED POWER ELECTRONICS CORP      AP1RA03GMT-HF-3")
        (field (name "DB_APPROVED_BY") "VSN")
      )
      (libsource (lib "") (part "=DB_VALUE_2"))
    )
    (comp (ref "Q11")
      (value "AP1RA03GMT-HF-3")
      (footprint "SMD_SOIC127P600X110-9AN")
      (fields
        (field (name "DB_PART_NUMBER") "TRA000001604")
        (field (name "DB_VALUE") "AP1RA03GMT-HF-3")
        (field (name "DB_MANUFACTURER_PART") "ADVANCED POWER ELECTRONICS CORP      AP1RA03GMT-HF-3")
        (field (name "DB_APPROVED_BY") "VSN")
      )
      (libsource (lib "") (part "=DB_VALUE_2"))
    )
    (comp (ref "Q12")
      (value "AP1RA03GMT-HF-3")
      (footprint "SMD_SOIC127P600X110-9AN")
      (fields
        (field (name "DB_PART_NUMBER") "TRA000001604")
        (field (name "DB_VALUE") "AP1RA03GMT-HF-3")
        (field (name "DB_MANUFACTURER_PART") "ADVANCED POWER ELECTRONICS CORP      AP1RA03GMT-HF-3")
        (field (name "DB_APPROVED_BY") "VSN")
      )
      (libsource (lib "") (part "=DB_VALUE_2"))
    )
    (comp (ref "Q13")
      (value "AP1RA03GMT-HF-3")
      (footprint "SMD_SOIC127P600X110-9AN")
      (fields
        (field (name "DB_PART_NUMBER") "TRA000001604")
        (field (name "DB_VALUE") "AP1RA03GMT-HF-3")
        (field (name "DB_MANUFACTURER_PART") "ADVANCED POWER ELECTRONICS CORP      AP1RA03GMT-HF-3")
        (field (name "DB_APPROVED_BY") "VSN")
      )
      (libsource (lib "") (part "=DB_VALUE_2"))
    )
    (comp (ref "Q14")
      (value "AP1RA03GMT-HF-3")
      (footprint "SMD_SOIC127P600X110-9AN")
      (fields
        (field (name "DB_PART_NUMBER") "TRA000001604")
        (field (name "DB_VALUE") "AP1RA03GMT-HF-3")
        (field (name "DB_MANUFACTURER_PART") "ADVANCED POWER ELECTRONICS CORP      AP1RA03GMT-HF-3")
        (field (name "DB_APPROVED_BY") "VSN")
      )
      (libsource (lib "") (part "=DB_VALUE_2"))
    )
    (comp (ref "Q15")
      (value "AP1RA03GMT-HF-3")
      (footprint "SMD_SOIC127P600X110-9AN")
      (fields
        (field (name "DB_PART_NUMBER") "TRA000001604")
        (field (name "DB_VALUE") "AP1RA03GMT-HF-3")
        (field (name "DB_MANUFACTURER_PART") "ADVANCED POWER ELECTRONICS CORP      AP1RA03GMT-HF-3")
        (field (name "DB_APPROVED_BY") "VSN")
      )
      (libsource (lib "") (part "=DB_VALUE_2"))
    )
    (comp (ref "Q16")
      (value "AP1RA03GMT-HF-3")
      (footprint "SMD_SOIC127P600X110-9AN")
      (fields
        (field (name "DB_PART_NUMBER") "TRA000001604")
        (field (name "DB_VALUE") "AP1RA03GMT-HF-3")
        (field (name "DB_MANUFACTURER_PART") "ADVANCED POWER ELECTRONICS CORP      AP1RA03GMT-HF-3")
        (field (name "DB_APPROVED_BY") "VSN")
      )
      (libsource (lib "") (part "=DB_VALUE_2"))
    )
    (comp (ref "Q17")
      (value "AP1RA03GMT-HF-3")
      (footprint "SMD_SOIC127P600X110-9AN")
      (fields
        (field (name "DB_PART_NUMBER") "TRA000001604")
        (field (name "DB_VALUE") "AP1RA03GMT-HF-3")
        (field (name "DB_MANUFACTURER_PART") "ADVANCED POWER ELECTRONICS CORP      AP1RA03GMT-HF-3")
        (field (name "DB_APPROVED_BY") "VSN")
      )
      (libsource (lib "") (part "=DB_VALUE_2"))
    )
    (comp (ref "Q18")
      (value "AP1RA03GMT-HF-3")
      (footprint "SMD_SOIC127P600X110-9AN")
      (fields
        (field (name "DB_PART_NUMBER") "TRA000001604")
        (field (name "DB_VALUE") "AP1RA03GMT-HF-3")
        (field (name "DB_MANUFACTURER_PART") "ADVANCED POWER ELECTRONICS CORP      AP1RA03GMT-HF-3")
        (field (name "DB_APPROVED_BY") "VSN")
      )
      (libsource (lib "") (part "=DB_VALUE_2"))
    )
    (comp (ref "Q19")
      (value "AP1RA03GMT-HF-3")
      (footprint "SMD_SOIC127P600X110-9AN")
      (fields
        (field (name "DB_PART_NUMBER") "TRA000001604")
        (field (name "DB_VALUE") "AP1RA03GMT-HF-3")
        (field (name "DB_MANUFACTURER_PART") "ADVANCED POWER ELECTRONICS CORP      AP1RA03GMT-HF-3")
        (field (name "DB_APPROVED_BY") "VSN")
      )
      (libsource (lib "") (part "=DB_VALUE_2"))
    )
    (comp (ref "Q20")
      (value "AP1RA03GMT-HF-3")
      (footprint "SMD_SOIC127P600X110-9AN")
      (fields
        (field (name "DB_PART_NUMBER") "TRA000001604")
        (field (name "DB_VALUE") "AP1RA03GMT-HF-3")
        (field (name "DB_MANUFACTURER_PART") "ADVANCED POWER ELECTRONICS CORP      AP1RA03GMT-HF-3")
        (field (name "DB_APPROVED_BY") "VSN")
      )
      (libsource (lib "") (part "=DB_VALUE_2"))
    )
    (comp (ref "Q21")
      (value "AP1RA03GMT-HF-3")
      (footprint "SMD_SOIC127P600X110-9AN")
      (fields
        (field (name "DB_PART_NUMBER") "TRA000001604")
        (field (name "DB_VALUE") "AP1RA03GMT-HF-3")
        (field (name "DB_MANUFACTURER_PART") "ADVANCED POWER ELECTRONICS CORP      AP1RA03GMT-HF-3")
        (field (name "DB_APPROVED_BY") "VSN")
      )
      (libsource (lib "") (part "=DB_VALUE_2"))
    )
    (comp (ref "Q22")
      (value "AP1RA03GMT-HF-3")
      (footprint "SMD_SOIC127P600X110-9AN")
      (fields
        (field (name "DB_PART_NUMBER") "TRA000001604")
        (field (name "DB_VALUE") "AP1RA03GMT-HF-3")
        (field (name "DB_MANUFACTURER_PART") "ADVANCED POWER ELECTRONICS CORP      AP1RA03GMT-HF-3")
        (field (name "DB_APPROVED_BY") "VSN")
      )
      (libsource (lib "") (part "=DB_VALUE_2"))
    )
    (comp (ref "Q23")
      (value "AP1RA03GMT-HF-3")
      (footprint "SMD_SOIC127P600X110-9AN")
      (fields
        (field (name "DB_PART_NUMBER") "TRA000001604")
        (field (name "DB_VALUE") "AP1RA03GMT-HF-3")
        (field (name "DB_MANUFACTURER_PART") "ADVANCED POWER ELECTRONICS CORP      AP1RA03GMT-HF-3")
        (field (name "DB_APPROVED_BY") "VSN")
      )
      (libsource (lib "") (part "=DB_VALUE_2"))
    )
    (comp (ref "Q24")
      (value "AP1RA03GMT-HF-3")
      (footprint "SMD_SOIC127P600X110-9AN")
      (fields
        (field (name "DB_PART_NUMBER") "TRA000001604")
        (field (name "DB_VALUE") "AP1RA03GMT-HF-3")
        (field (name "DB_MANUFACTURER_PART") "ADVANCED POWER ELECTRONICS CORP      AP1RA03GMT-HF-3")
        (field (name "DB_APPROVED_BY") "VSN")
      )
      (libsource (lib "") (part "=DB_VALUE_2"))
    )
    (comp (ref "Q25")
      (value "AP1RA03GMT-HF-3")
      (footprint "SMD_SOIC127P600X110-9AN")
      (fields
        (field (name "DB_PART_NUMBER") "TRA000001604")
        (field (name "DB_VALUE") "AP1RA03GMT-HF-3")
        (field (name "DB_MANUFACTURER_PART") "ADVANCED POWER ELECTRONICS CORP      AP1RA03GMT-HF-3")
        (field (name "DB_APPROVED_BY") "VSN")
      )
      (libsource (lib "") (part "=DB_VALUE_2"))
    )
    (comp (ref "Q26")
      (value "AP1RA03GMT-HF-3")
      (footprint "SMD_SOIC127P600X110-9AN")
      (fields
        (field (name "DB_PART_NUMBER") "TRA000001604")
        (field (name "DB_VALUE") "AP1RA03GMT-HF-3")
        (field (name "DB_MANUFACTURER_PART") "ADVANCED POWER ELECTRONICS CORP      AP1RA03GMT-HF-3")
        (field (name "DB_APPROVED_BY") "VSN")
      )
      (libsource (lib "") (part "=DB_VALUE_2"))
    )
    (comp (ref "Q27")
      (value "AP1RA03GMT-HF-3")
      (footprint "SMD_SOIC127P600X110-9AN")
      (fields
        (field (name "DB_PART_NUMBER") "TRA000001604")
        (field (name "DB_VALUE") "AP1RA03GMT-HF-3")
        (field (name "DB_MANUFACTURER_PART") "ADVANCED POWER ELECTRONICS CORP      AP1RA03GMT-HF-3")
        (field (name "DB_APPROVED_BY") "VSN")
      )
      (libsource (lib "") (part "=DB_VALUE_2"))
    )
    (comp (ref "Q28")
      (value "AP1RA03GMT-HF-3")
      (footprint "SMD_SOIC127P600X110-9AN")
      (fields
        (field (name "DB_PART_NUMBER") "TRA000001604")
        (field (name "DB_VALUE") "AP1RA03GMT-HF-3")
        (field (name "DB_MANUFACTURER_PART") "ADVANCED POWER ELECTRONICS CORP      AP1RA03GMT-HF-3")
        (field (name "DB_APPROVED_BY") "VSN")
      )
      (libsource (lib "") (part "=DB_VALUE_2"))
    )
    (comp (ref "Q29")
      (value "AP1RA03GMT-HF-3")
      (footprint "SMD_SOIC127P600X110-9AN")
      (fields
        (field (name "DB_PART_NUMBER") "TRA000001604")
        (field (name "DB_VALUE") "AP1RA03GMT-HF-3")
        (field (name "DB_MANUFACTURER_PART") "ADVANCED POWER ELECTRONICS CORP      AP1RA03GMT-HF-3")
        (field (name "DB_APPROVED_BY") "VSN")
      )
      (libsource (lib "") (part "=DB_VALUE_2"))
    )
    (comp (ref "Q30")
      (value "AP1RA03GMT-HF-3")
      (footprint "SMD_SOIC127P600X110-9AN")
      (fields
        (field (name "DB_PART_NUMBER") "TRA000001604")
        (field (name "DB_VALUE") "AP1RA03GMT-HF-3")
        (field (name "DB_MANUFACTURER_PART") "ADVANCED POWER ELECTRONICS CORP      AP1RA03GMT-HF-3")
        (field (name "DB_APPROVED_BY") "VSN")
      )
      (libsource (lib "") (part "=DB_VALUE_2"))
    )
    (comp (ref "Q31")
      (value "AP1RA03GMT-HF-3")
      (footprint "SMD_SOIC127P600X110-9AN")
      (fields
        (field (name "DB_PART_NUMBER") "TRA000001604")
        (field (name "DB_VALUE") "AP1RA03GMT-HF-3")
        (field (name "DB_MANUFACTURER_PART") "ADVANCED POWER ELECTRONICS CORP      AP1RA03GMT-HF-3")
        (field (name "DB_APPROVED_BY") "VSN")
      )
      (libsource (lib "") (part "=DB_VALUE_2"))
    )
    (comp (ref "Q32")
      (value "AP1RA03GMT-HF-3")
      (footprint "SMD_SOIC127P600X110-9AN")
      (fields
        (field (name "DB_PART_NUMBER") "TRA000001604")
        (field (name "DB_VALUE") "AP1RA03GMT-HF-3")
        (field (name "DB_MANUFACTURER_PART") "ADVANCED POWER ELECTRONICS CORP      AP1RA03GMT-HF-3")
        (field (name "DB_APPROVED_BY") "VSN")
      )
      (libsource (lib "") (part "=DB_VALUE_2"))
    )
    (comp (ref "Q33")
      (value "AP1RA03GMT-HF-3")
      (footprint "SMD_SOIC127P600X110-9AN")
      (fields
        (field (name "DB_PART_NUMBER") "TRA000001604")
        (field (name "DB_VALUE") "AP1RA03GMT-HF-3")
        (field (name "DB_MANUFACTURER_PART") "ADVANCED POWER ELECTRONICS CORP      AP1RA03GMT-HF-3")
        (field (name "DB_APPROVED_BY") "VSN")
      )
      (libsource (lib "") (part "=DB_VALUE_2"))
    )
    (comp (ref "Q34")
      (value "AP1RA03GMT-HF-3")
      (footprint "SMD_SOIC127P600X110-9AN")
      (fields
        (field (name "DB_PART_NUMBER") "TRA000001604")
        (field (name "DB_VALUE") "AP1RA03GMT-HF-3")
        (field (name "DB_MANUFACTURER_PART") "ADVANCED POWER ELECTRONICS CORP      AP1RA03GMT-HF-3")
        (field (name "DB_APPROVED_BY") "VSN")
      )
      (libsource (lib "") (part "=DB_VALUE_2"))
    )
    (comp (ref "Q35")
      (value "AP1RA03GMT-HF-3")
      (footprint "SMD_SOIC127P600X110-9AN")
      (fields
        (field (name "DB_PART_NUMBER") "TRA000001604")
        (field (name "DB_VALUE") "AP1RA03GMT-HF-3")
        (field (name "DB_MANUFACTURER_PART") "ADVANCED POWER ELECTRONICS CORP      AP1RA03GMT-HF-3")
        (field (name "DB_APPROVED_BY") "VSN")
      )
      (libsource (lib "") (part "=DB_VALUE_2"))
    )
    (comp (ref "Q36")
      (value "AP1RA03GMT-HF-3")
      (footprint "SMD_SOIC127P600X110-9AN")
      (fields
        (field (name "DB_PART_NUMBER") "TRA000001604")
        (field (name "DB_VALUE") "AP1RA03GMT-HF-3")
        (field (name "DB_MANUFACTURER_PART") "ADVANCED POWER ELECTRONICS CORP      AP1RA03GMT-HF-3")
        (field (name "DB_APPROVED_BY") "VSN")
      )
      (libsource (lib "") (part "=DB_VALUE_2"))
    )
    (comp (ref "Q37")
      (value "AP1RA03GMT-HF-3")
      (footprint "SMD_SOIC127P600X110-9AN")
      (fields
        (field (name "DB_PART_NUMBER") "TRA000001604")
        (field (name "DB_VALUE") "AP1RA03GMT-HF-3")
        (field (name "DB_MANUFACTURER_PART") "ADVANCED POWER ELECTRONICS CORP      AP1RA03GMT-HF-3")
        (field (name "DB_APPROVED_BY") "VSN")
      )
      (libsource (lib "") (part "=DB_VALUE_2"))
    )
    (comp (ref "Q38")
      (value "AP1RA03GMT-HF-3")
      (footprint "SMD_SOIC127P600X110-9AN")
      (fields
        (field (name "DB_PART_NUMBER") "TRA000001604")
        (field (name "DB_VALUE") "AP1RA03GMT-HF-3")
        (field (name "DB_MANUFACTURER_PART") "ADVANCED POWER ELECTRONICS CORP      AP1RA03GMT-HF-3")
        (field (name "DB_APPROVED_BY") "VSN")
      )
      (libsource (lib "") (part "=DB_VALUE_2"))
    )
    (comp (ref "Q39")
      (value "AP1RA03GMT-HF-3")
      (footprint "SMD_SOIC127P600X110-9AN")
      (fields
        (field (name "DB_PART_NUMBER") "TRA000001604")
        (field (name "DB_VALUE") "AP1RA03GMT-HF-3")
        (field (name "DB_MANUFACTURER_PART") "ADVANCED POWER ELECTRONICS CORP      AP1RA03GMT-HF-3")
        (field (name "DB_APPROVED_BY") "VSN")
      )
      (libsource (lib "") (part "=DB_VALUE_2"))
    )
    (comp (ref "Q40")
      (value "AP1RA03GMT-HF-3")
      (footprint "SMD_SOIC127P600X110-9AN")
      (fields
        (field (name "DB_PART_NUMBER") "TRA000001604")
        (field (name "DB_VALUE") "AP1RA03GMT-HF-3")
        (field (name "DB_MANUFACTURER_PART") "ADVANCED POWER ELECTRONICS CORP      AP1RA03GMT-HF-3")
        (field (name "DB_APPROVED_BY") "VSN")
      )
      (libsource (lib "") (part "=DB_VALUE_2"))
    )
    (comp (ref "Q41")
      (value "AP1RA03GMT-HF-3")
      (footprint "SMD_SOIC127P600X110-9AN")
      (fields
        (field (name "DB_PART_NUMBER") "TRA000001604")
        (field (name "DB_VALUE") "AP1RA03GMT-HF-3")
        (field (name "DB_MANUFACTURER_PART") "ADVANCED POWER ELECTRONICS CORP      AP1RA03GMT-HF-3")
        (field (name "DB_APPROVED_BY") "VSN")
      )
      (libsource (lib "") (part "=DB_VALUE_2"))
    )
    (comp (ref "Q42")
      (value "AP1RA03GMT-HF-3")
      (footprint "SMD_SOIC127P600X110-9AN")
      (fields
        (field (name "DB_PART_NUMBER") "TRA000001604")
        (field (name "DB_VALUE") "AP1RA03GMT-HF-3")
        (field (name "DB_MANUFACTURER_PART") "ADVANCED POWER ELECTRONICS CORP      AP1RA03GMT-HF-3")
        (field (name "DB_APPROVED_BY") "VSN")
      )
      (libsource (lib "") (part "=DB_VALUE_2"))
    )
    (comp (ref "Q43")
      (value "AP1RA03GMT-HF-3")
      (footprint "SMD_SOIC127P600X110-9AN")
      (fields
        (field (name "DB_PART_NUMBER") "TRA000001604")
        (field (name "DB_VALUE") "AP1RA03GMT-HF-3")
        (field (name "DB_MANUFACTURER_PART") "ADVANCED POWER ELECTRONICS CORP      AP1RA03GMT-HF-3")
        (field (name "DB_APPROVED_BY") "VSN")
      )
      (libsource (lib "") (part "=DB_VALUE_2"))
    )
    (comp (ref "Q44")
      (value "AP1RA03GMT-HF-3")
      (footprint "SMD_SOIC127P600X110-9AN")
      (fields
        (field (name "DB_PART_NUMBER") "TRA000001604")
        (field (name "DB_VALUE") "AP1RA03GMT-HF-3")
        (field (name "DB_MANUFACTURER_PART") "ADVANCED POWER ELECTRONICS CORP      AP1RA03GMT-HF-3")
        (field (name "DB_APPROVED_BY") "VSN")
      )
      (libsource (lib "") (part "=DB_VALUE_2"))
    )
    (comp (ref "Q45")
      (value "AP1RA03GMT-HF-3")
      (footprint "SMD_SOIC127P600X110-9AN")
      (fields
        (field (name "DB_PART_NUMBER") "TRA000001604")
        (field (name "DB_VALUE") "AP1RA03GMT-HF-3")
        (field (name "DB_MANUFACTURER_PART") "ADVANCED POWER ELECTRONICS CORP      AP1RA03GMT-HF-3")
        (field (name "DB_APPROVED_BY") "VSN")
      )
      (libsource (lib "") (part "=DB_VALUE_2"))
    )
    (comp (ref "Q46")
      (value "AP1RA03GMT-HF-3")
      (footprint "SMD_SOIC127P600X110-9AN")
      (fields
        (field (name "DB_PART_NUMBER") "TRA000001604")
        (field (name "DB_VALUE") "AP1RA03GMT-HF-3")
        (field (name "DB_MANUFACTURER_PART") "ADVANCED POWER ELECTRONICS CORP      AP1RA03GMT-HF-3")
        (field (name "DB_APPROVED_BY") "VSN")
      )
      (libsource (lib "") (part "=DB_VALUE_2"))
    )
    (comp (ref "Q47")
      (value "AP1RA03GMT-HF-3")
      (footprint "SMD_SOIC127P600X110-9AN")
      (fields
        (field (name "DB_PART_NUMBER") "TRA000001604")
        (field (name "DB_VALUE") "AP1RA03GMT-HF-3")
        (field (name "DB_MANUFACTURER_PART") "ADVANCED POWER ELECTRONICS CORP      AP1RA03GMT-HF-3")
        (field (name "DB_APPROVED_BY") "VSN")
      )
      (libsource (lib "") (part "=DB_VALUE_2"))
    )
    (comp (ref "Q48")
      (value "AP1RA03GMT-HF-3")
      (footprint "SMD_SOIC127P600X110-9AN")
      (fields
        (field (name "DB_PART_NUMBER") "TRA000001604")
        (field (name "DB_VALUE") "AP1RA03GMT-HF-3")
        (field (name "DB_MANUFACTURER_PART") "ADVANCED POWER ELECTRONICS CORP      AP1RA03GMT-HF-3")
        (field (name "DB_APPROVED_BY") "VSN")
      )
      (libsource (lib "") (part "=DB_VALUE_2"))
    )
    (comp (ref "U11")
      (value "LTC4449EDCB#TRPBF")
      (footprint "SMD_SON45P300X200X80-9N")
      (fields
        (field (name "DB_PART_NUMBER") "DRV000000079")
        (field (name "DB_VALUE") "LTC4449EDCB#TRPBF")
        (field (name "DB_MANUFACTURER_PART") "LINEAR       LTC4449EDCB#TRPBF")
        (field (name "DB_APPROVED_BY") "VSN")
      )
      (libsource (lib "") (part "=DB_VALUE_1"))
    )
    (comp (ref "U12")
      (value "LTC4449EDCB#TRPBF")
      (footprint "SMD_SON45P300X200X80-9N")
      (fields
        (field (name "DB_PART_NUMBER") "DRV000000079")
        (field (name "DB_VALUE") "LTC4449EDCB#TRPBF")
        (field (name "DB_MANUFACTURER_PART") "LINEAR       LTC4449EDCB#TRPBF")
        (field (name "DB_APPROVED_BY") "VSN")
      )
      (libsource (lib "") (part "=DB_VALUE_1"))
    )
    (comp (ref "U13")
      (value "LTC4449EDCB#TRPBF")
      (footprint "SMD_SON45P300X200X80-9N")
      (fields
        (field (name "DB_PART_NUMBER") "DRV000000079")
        (field (name "DB_VALUE") "LTC4449EDCB#TRPBF")
        (field (name "DB_MANUFACTURER_PART") "LINEAR       LTC4449EDCB#TRPBF")
        (field (name "DB_APPROVED_BY") "VSN")
      )
      (libsource (lib "") (part "=DB_VALUE_1"))
    )
    (comp (ref "U14")
      (value "LTC4449EDCB#TRPBF")
      (footprint "SMD_SON45P300X200X80-9N")
      (fields
        (field (name "DB_PART_NUMBER") "DRV000000079")
        (field (name "DB_VALUE") "LTC4449EDCB#TRPBF")
        (field (name "DB_MANUFACTURER_PART") "LINEAR       LTC4449EDCB#TRPBF")
        (field (name "DB_APPROVED_BY") "VSN")
      )
      (libsource (lib "") (part "=DB_VALUE_1"))
    )
    (comp (ref "U15")
      (value "LTC4449EDCB#TRPBF")
      (footprint "SMD_SON45P300X200X80-9N")
      (fields
        (field (name "DB_PART_NUMBER") "DRV000000079")
        (field (name "DB_VALUE") "LTC4449EDCB#TRPBF")
        (field (name "DB_MANUFACTURER_PART") "LINEAR       LTC4449EDCB#TRPBF")
        (field (name "DB_APPROVED_BY") "VSN")
      )
      (libsource (lib "") (part "=DB_VALUE_1"))
    )
    (comp (ref "U16")
      (value "LTC4449EDCB#TRPBF")
      (footprint "SMD_SON45P300X200X80-9N")
      (fields
        (field (name "DB_PART_NUMBER") "DRV000000079")
        (field (name "DB_VALUE") "LTC4449EDCB#TRPBF")
        (field (name "DB_MANUFACTURER_PART") "LINEAR       LTC4449EDCB#TRPBF")
        (field (name "DB_APPROVED_BY") "VSN")
      )
      (libsource (lib "") (part "=DB_VALUE_1"))
    )
    (comp (ref "U17")
      (value "LTC4449EDCB#TRPBF")
      (footprint "SMD_SON45P300X200X80-9N")
      (fields
        (field (name "DB_PART_NUMBER") "DRV000000079")
        (field (name "DB_VALUE") "LTC4449EDCB#TRPBF")
        (field (name "DB_MANUFACTURER_PART") "LINEAR       LTC4449EDCB#TRPBF")
        (field (name "DB_APPROVED_BY") "VSN")
      )
      (libsource (lib "") (part "=DB_VALUE_1"))
    )
    (comp (ref "U18")
      (value "LTC4449EDCB#TRPBF")
      (footprint "SMD_SON45P300X200X80-9N")
      (fields
        (field (name "DB_PART_NUMBER") "DRV000000079")
        (field (name "DB_VALUE") "LTC4449EDCB#TRPBF")
        (field (name "DB_MANUFACTURER_PART") "LINEAR       LTC4449EDCB#TRPBF")
        (field (name "DB_APPROVED_BY") "VSN")
      )
      (libsource (lib "") (part "=DB_VALUE_1"))
    )
    (comp (ref "U19")
      (value "LTC4449EDCB#TRPBF")
      (footprint "SMD_SON45P300X200X80-9N")
      (fields
        (field (name "DB_PART_NUMBER") "DRV000000079")
        (field (name "DB_VALUE") "LTC4449EDCB#TRPBF")
        (field (name "DB_MANUFACTURER_PART") "LINEAR       LTC4449EDCB#TRPBF")
        (field (name "DB_APPROVED_BY") "VSN")
      )
      (libsource (lib "") (part "=DB_VALUE_1"))
    )
    (comp (ref "U20")
      (value "LTC4449EDCB#TRPBF")
      (footprint "SMD_SON45P300X200X80-9N")
      (fields
        (field (name "DB_PART_NUMBER") "DRV000000079")
        (field (name "DB_VALUE") "LTC4449EDCB#TRPBF")
        (field (name "DB_MANUFACTURER_PART") "LINEAR       LTC4449EDCB#TRPBF")
        (field (name "DB_APPROVED_BY") "VSN")
      )
      (libsource (lib "") (part "=DB_VALUE_1"))
    )
    (comp (ref "U21")
      (value "LTC4449EDCB#TRPBF")
      (footprint "SMD_SON45P300X200X80-9N")
      (fields
        (field (name "DB_PART_NUMBER") "DRV000000079")
        (field (name "DB_VALUE") "LTC4449EDCB#TRPBF")
        (field (name "DB_MANUFACTURER_PART") "LINEAR       LTC4449EDCB#TRPBF")
        (field (name "DB_APPROVED_BY") "VSN")
      )
      (libsource (lib "") (part "=DB_VALUE_1"))
    )
    (comp (ref "U22")
      (value "LTC4449EDCB#TRPBF")
      (footprint "SMD_SON45P300X200X80-9N")
      (fields
        (field (name "DB_PART_NUMBER") "DRV000000079")
        (field (name "DB_VALUE") "LTC4449EDCB#TRPBF")
        (field (name "DB_MANUFACTURER_PART") "LINEAR       LTC4449EDCB#TRPBF")
        (field (name "DB_APPROVED_BY") "VSN")
      )
      (libsource (lib "") (part "=DB_VALUE_1"))
    )
    (comp (ref "U23")
      (value "LTC4449EDCB#TRPBF")
      (footprint "SMD_SON45P300X200X80-9N")
      (fields
        (field (name "DB_PART_NUMBER") "DRV000000079")
        (field (name "DB_VALUE") "LTC4449EDCB#TRPBF")
        (field (name "DB_MANUFACTURER_PART") "LINEAR       LTC4449EDCB#TRPBF")
        (field (name "DB_APPROVED_BY") "VSN")
      )
      (libsource (lib "") (part "=DB_VALUE_1"))
    )
    (comp (ref "U24")
      (value "LTC4449EDCB#TRPBF")
      (footprint "SMD_SON45P300X200X80-9N")
      (fields
        (field (name "DB_PART_NUMBER") "DRV000000079")
        (field (name "DB_VALUE") "LTC4449EDCB#TRPBF")
        (field (name "DB_MANUFACTURER_PART") "LINEAR       LTC4449EDCB#TRPBF")
        (field (name "DB_APPROVED_BY") "VSN")
      )
      (libsource (lib "") (part "=DB_VALUE_1"))
    )
    (comp (ref "U25")
      (value "LTC4449EDCB#TRPBF")
      (footprint "SMD_SON45P300X200X80-9N")
      (fields
        (field (name "DB_PART_NUMBER") "DRV000000079")
        (field (name "DB_VALUE") "LTC4449EDCB#TRPBF")
        (field (name "DB_MANUFACTURER_PART") "LINEAR       LTC4449EDCB#TRPBF")
        (field (name "DB_APPROVED_BY") "VSN")
      )
      (libsource (lib "") (part "=DB_VALUE_1"))
    )
    (comp (ref "U26")
      (value "LTC4449EDCB#TRPBF")
      (footprint "SMD_SON45P300X200X80-9N")
      (fields
        (field (name "DB_PART_NUMBER") "DRV000000079")
        (field (name "DB_VALUE") "LTC4449EDCB#TRPBF")
        (field (name "DB_MANUFACTURER_PART") "LINEAR       LTC4449EDCB#TRPBF")
        (field (name "DB_APPROVED_BY") "VSN")
      )
      (libsource (lib "") (part "=DB_VALUE_1"))
    )
  )
  (nets
    (net (code "1") (name "/1V") (class "Default")
      (node (ref "C100") (pin "2") (pinfunction "2_2") (pintype "passive"))
      (node (ref "C103") (pin "2") (pinfunction "2_2") (pintype "passive"))
      (node (ref "C104") (pin "2") (pinfunction "2_2") (pintype "passive"))
      (node (ref "C105") (pin "2") (pinfunction "2_2") (pintype "passive"))
      (node (ref "C108") (pin "2") (pinfunction "2_2") (pintype "passive"))
      (node (ref "C109") (pin "2") (pinfunction "2_2") (pintype "passive"))
      (node (ref "C110") (pin "2") (pinfunction "2_2") (pintype "passive"))
      (node (ref "C113") (pin "2") (pinfunction "2_2") (pintype "passive"))
      (node (ref "C114") (pin "2") (pinfunction "2_2") (pintype "passive"))
      (node (ref "C115") (pin "2") (pinfunction "2_2") (pintype "passive"))
      (node (ref "C130") (pin "2") (pinfunction "2_2") (pintype "passive"))
      (node (ref "C131") (pin "2") (pinfunction "2_2") (pintype "passive"))
      (node (ref "C132") (pin "2") (pinfunction "2_2") (pintype "passive"))
      (node (ref "C135") (pin "2") (pinfunction "2_2") (pintype "passive"))
      (node (ref "C136") (pin "2") (pinfunction "2_2") (pintype "passive"))
      (node (ref "C137") (pin "2") (pinfunction "2_2") (pintype "passive"))
      (node (ref "C140") (pin "2") (pinfunction "2_2") (pintype "passive"))
      (node (ref "C141") (pin "2") (pinfunction "2_2") (pintype "passive"))
      (node (ref "C142") (pin "2") (pinfunction "2_2") (pintype "passive"))
      (node (ref "C145") (pin "2") (pinfunction "2_2") (pintype "passive"))
      (node (ref "C146") (pin "2") (pinfunction "2_2") (pintype "passive"))
      (node (ref "C147") (pin "2") (pinfunction "2_2") (pintype "passive"))
      (node (ref "C236") (pin "2") (pinfunction "2_2") (pintype "passive"))
      (node (ref "C34") (pin "2") (pinfunction "2_2") (pintype "passive"))
      (node (ref "C35") (pin "2") (pinfunction "2_2") (pintype "passive"))
      (node (ref "C350") (pin "2") (pinfunction "2_2") (pintype "passive"))
      (node (ref "C351") (pin "2") (pinfunction "2_2") (pintype "passive"))
      (node (ref "C352") (pin "2") (pinfunction "2_2") (pintype "passive"))
      (node (ref "C355") (pin "2") (pinfunction "2_2") (pintype "passive"))
      (node (ref "C356") (pin "2") (pinfunction "2_2") (pintype "passive"))
      (node (ref "C357") (pin "2") (pinfunction "2_2") (pintype "passive"))
      (node (ref "C360") (pin "2") (pinfunction "2_2") (pintype "passive"))
      (node (ref "C361") (pin "2") (pinfunction "2_2") (pintype "passive"))
      (node (ref "C362") (pin "2") (pinfunction "2_2") (pintype "passive"))
      (node (ref "C365") (pin "2") (pinfunction "2_2") (pintype "passive"))
      (node (ref "C366") (pin "2") (pinfunction "2_2") (pintype "passive"))
      (node (ref "C367") (pin "2") (pinfunction "2_2") (pintype "passive"))
      (node (ref "C370") (pin "2") (pinfunction "2_2") (pintype "passive"))
      (node (ref "C371") (pin "2") (pinfunction "2_2") (pintype "passive"))
      (node (ref "C372") (pin "2") (pinfunction "2_2") (pintype "passive"))
      (node (ref "C375") (pin "2") (pinfunction "2_2") (pintype "passive"))
      (node (ref "C376") (pin "2") (pinfunction "2_2") (pintype "passive"))
      (node (ref "C377") (pin "2") (pinfunction "2_2") (pintype "passive"))
      (node (ref "C380") (pin "2") (pinfunction "2_2") (pintype "passive"))
      (node (ref "C381") (pin "2") (pinfunction "2_2") (pintype "passive"))
      (node (ref "C382") (pin "2") (pinfunction "2_2") (pintype "passive"))
      (node (ref "C385") (pin "2") (pinfunction "2_2") (pintype "passive"))
      (node (ref "C386") (pin "2") (pinfunction "2_2") (pintype "passive"))
      (node (ref "C387") (pin "2") (pinfunction "2_2") (pintype "passive"))
      (node (ref "C388") (pin "2") (pinfunction "2_2") (pintype "passive"))
      (node (ref "C389") (pin "2") (pinfunction "2_2") (pintype "passive"))
      (node (ref "C39") (pin "2") (pinfunction "2_2") (pintype "passive"))
      (node (ref "C390") (pin "2") (pinfunction "2_2") (pintype "passive"))
      (node (ref "C393") (pin "2") (pinfunction "2_2") (pintype "passive"))
      (node (ref "C394") (pin "2") (pinfunction "2_2") (pintype "passive"))
      (node (ref "C395") (pin "2") (pinfunction "2_2") (pintype "passive"))
      (node (ref "C396") (pin "2") (pinfunction "2_2") (pintype "passive"))
      (node (ref "C397") (pin "2") (pinfunction "2_2") (pintype "passive"))
      (node (ref "C398") (pin "2") (pinfunction "2_2") (pintype "passive"))
      (node (ref "C399") (pin "2") (pinfunction "2_2") (pintype "passive"))
      (node (ref "C40") (pin "2") (pinfunction "2_2") (pintype "passive"))
      (node (ref "C400") (pin "2") (pinfunction "2_2") (pintype "passive"))
      (node (ref "C401") (pin "2") (pinfunction "2_2") (pintype "passive"))
      (node (ref "C408") (pin "2") (pinfunction "2_2") (pintype "passive"))
      (node (ref "C409") (pin "2") (pinfunction "2_2") (pintype "passive"))
      (node (ref "C41") (pin "2") (pinfunction "2_2") (pintype "passive"))
      (node (ref "C410") (pin "2") (pinfunction "2_2") (pintype "passive"))
      (node (ref "C411") (pin "2") (pinfunction "2_2") (pintype "passive"))
      (node (ref "C412") (pin "2") (pinfunction "2_2") (pintype "passive"))
      (node (ref "C413") (pin "2") (pinfunction "2_2") (pintype "passive"))
      (node (ref "C414") (pin "2") (pinfunction "2_2") (pintype "passive"))
      (node (ref "C415") (pin "2") (pinfunction "2_2") (pintype "passive"))
      (node (ref "C416") (pin "2") (pinfunction "2_2") (pintype "passive"))
      (node (ref "C417") (pin "2") (pinfunction "2_2") (pintype "passive"))
      (node (ref "C418") (pin "2") (pinfunction "2_2") (pintype "passive"))
      (node (ref "C419") (pin "2") (pinfunction "2_2") (pintype "passive"))
      (node (ref "C44") (pin "2") (pinfunction "2_2") (pintype "passive"))
      (node (ref "C45") (pin "2") (pinfunction "2_2") (pintype "passive"))
      (node (ref "C46") (pin "2") (pinfunction "2_2") (pintype "passive"))
      (node (ref "C49") (pin "2") (pinfunction "2_2") (pintype "passive"))
      (node (ref "C50") (pin "2") (pinfunction "2_2") (pintype "passive"))
      (node (ref "C51") (pin "2") (pinfunction "2_2") (pintype "passive"))
      (node (ref "C66") (pin "2") (pinfunction "2_2") (pintype "passive"))
      (node (ref "C67") (pin "2") (pinfunction "2_2") (pintype "passive"))
      (node (ref "C68") (pin "2") (pinfunction "2_2") (pintype "passive"))
      (node (ref "C71") (pin "2") (pinfunction "2_2") (pintype "passive"))
      (node (ref "C72") (pin "2") (pinfunction "2_2") (pintype "passive"))
      (node (ref "C73") (pin "2") (pinfunction "2_2") (pintype "passive"))
      (node (ref "C76") (pin "2") (pinfunction "2_2") (pintype "passive"))
      (node (ref "C77") (pin "2") (pinfunction "2_2") (pintype "passive"))
      (node (ref "C78") (pin "2") (pinfunction "2_2") (pintype "passive"))
      (node (ref "C81") (pin "2") (pinfunction "2_2") (pintype "passive"))
      (node (ref "C82") (pin "2") (pinfunction "2_2") (pintype "passive"))
      (node (ref "C83") (pin "2") (pinfunction "2_2") (pintype "passive"))
      (node (ref "C98") (pin "2") (pinfunction "2_2") (pintype "passive"))
      (node (ref "C99") (pin "2") (pinfunction "2_2") (pintype "passive"))
      (node (ref "L1") (pin "2") (pinfunction "2_2") (pintype "passive"))
      (node (ref "L10") (pin "2") (pinfunction "2_2") (pintype "passive"))
      (node (ref "L11") (pin "2") (pinfunction "2_2") (pintype "passive"))
      (node (ref "L12") (pin "2") (pinfunction "2_2") (pintype "passive"))
      (node (ref "L13") (pin "2") (pinfunction "2_2") (pintype "passive"))
      (node (ref "L14") (pin "2") (pinfunction "2_2") (pintype "passive"))
      (node (ref "L15") (pin "2") (pinfunction "2_2") (pintype "passive"))
      (node (ref "L16") (pin "2") (pinfunction "2_2") (pintype "passive"))
      (node (ref "L2") (pin "2") (pinfunction "2_2") (pintype "passive"))
      (node (ref "L3") (pin "2") (pinfunction "2_2") (pintype "passive"))
      (node (ref "L4") (pin "2") (pinfunction "2_2") (pintype "passive"))
      (node (ref "L5") (pin "2") (pinfunction "2_2") (pintype "passive"))
      (node (ref "L6") (pin "2") (pinfunction "2_2") (pintype "passive"))
      (node (ref "L7") (pin "2") (pinfunction "2_2") (pintype "passive"))
      (node (ref "L8") (pin "2") (pinfunction "2_2") (pintype "passive"))
      (node (ref "L9") (pin "2") (pinfunction "2_2") (pintype "passive"))
    )
    (net (code "2") (name "/3.3V") (class "Default")
      (node (ref "C120") (pin "1") (pinfunction "1_1") (pintype "passive"))
      (node (ref "C121") (pin "1") (pinfunction "1_1") (pintype "passive"))
      (node (ref "C122") (pin "1") (pinfunction "1_1") (pintype "passive"))
      (node (ref "C123") (pin "1") (pinfunction "1_1") (pintype "passive"))
      (node (ref "C24") (pin "1") (pinfunction "1_1") (pintype "passive"))
      (node (ref "C25") (pin "1") (pinfunction "1_1") (pintype "passive"))
      (node (ref "C26") (pin "1") (pinfunction "1_1") (pintype "passive"))
      (node (ref "C27") (pin "1") (pinfunction "1_1") (pintype "passive"))
      (node (ref "C56") (pin "1") (pinfunction "1_1") (pintype "passive"))
      (node (ref "C57") (pin "1") (pinfunction "1_1") (pintype "passive"))
      (node (ref "C58") (pin "1") (pinfunction "1_1") (pintype "passive"))
      (node (ref "C59") (pin "1") (pinfunction "1_1") (pintype "passive"))
      (node (ref "C88") (pin "1") (pinfunction "1_1") (pintype "passive"))
      (node (ref "C89") (pin "1") (pinfunction "1_1") (pintype "passive"))
      (node (ref "C90") (pin "1") (pinfunction "1_1") (pintype "passive"))
      (node (ref "C91") (pin "1") (pinfunction "1_1") (pintype "passive"))
      (node (ref "U11") (pin "6") (pinfunction "VLOGIC_6") (pintype "passive"))
      (node (ref "U12") (pin "6") (pinfunction "VLOGIC_6") (pintype "passive"))
      (node (ref "U13") (pin "6") (pinfunction "VLOGIC_6") (pintype "passive"))
      (node (ref "U14") (pin "6") (pinfunction "VLOGIC_6") (pintype "passive"))
      (node (ref "U15") (pin "6") (pinfunction "VLOGIC_6") (pintype "passive"))
      (node (ref "U16") (pin "6") (pinfunction "VLOGIC_6") (pintype "passive"))
      (node (ref "U17") (pin "6") (pinfunction "VLOGIC_6") (pintype "passive"))
      (node (ref "U18") (pin "6") (pinfunction "VLOGIC_6") (pintype "passive"))
      (node (ref "U19") (pin "6") (pinfunction "VLOGIC_6") (pintype "passive"))
      (node (ref "U20") (pin "6") (pinfunction "VLOGIC_6") (pintype "passive"))
      (node (ref "U21") (pin "6") (pinfunction "VLOGIC_6") (pintype "passive"))
      (node (ref "U22") (pin "6") (pinfunction "VLOGIC_6") (pintype "passive"))
      (node (ref "U23") (pin "6") (pinfunction "VLOGIC_6") (pintype "passive"))
      (node (ref "U24") (pin "6") (pinfunction "VLOGIC_6") (pintype "passive"))
      (node (ref "U25") (pin "6") (pinfunction "VLOGIC_6") (pintype "passive"))
      (node (ref "U26") (pin "6") (pinfunction "VLOGIC_6") (pintype "passive"))
    )
    (net (code "3") (name "/5.0V") (class "Default")
      (node (ref "C116") (pin "2") (pinfunction "2_2") (pintype "passive"))
      (node (ref "C117") (pin "2") (pinfunction "2_2") (pintype "passive"))
      (node (ref "C118") (pin "2") (pinfunction "2_2") (pintype "passive"))
      (node (ref "C119") (pin "2") (pinfunction "2_2") (pintype "passive"))
      (node (ref "C20") (pin "2") (pinfunction "2_2") (pintype "passive"))
      (node (ref "C21") (pin "2") (pinfunction "2_2") (pintype "passive"))
      (node (ref "C22") (pin "2") (pinfunction "2_2") (pintype "passive"))
      (node (ref "C23") (pin "2") (pinfunction "2_2") (pintype "passive"))
      (node (ref "C52") (pin "2") (pinfunction "2_2") (pintype "passive"))
      (node (ref "C53") (pin "2") (pinfunction "2_2") (pintype "passive"))
      (node (ref "C54") (pin "2") (pinfunction "2_2") (pintype "passive"))
      (node (ref "C55") (pin "2") (pinfunction "2_2") (pintype "passive"))
      (node (ref "C84") (pin "2") (pinfunction "2_2") (pintype "passive"))
      (node (ref "C85") (pin "2") (pinfunction "2_2") (pintype "passive"))
      (node (ref "C86") (pin "2") (pinfunction "2_2") (pintype "passive"))
      (node (ref "C87") (pin "2") (pinfunction "2_2") (pintype "passive"))
      (node (ref "D10") (pin "2") (pinfunction "A_2") (pintype "passive"))
      (node (ref "D11") (pin "2") (pinfunction "A_2") (pintype "passive"))
      (node (ref "D12") (pin "2") (pinfunction "A_2") (pintype "passive"))
      (node (ref "D13") (pin "2") (pinfunction "A_2") (pintype "passive"))
      (node (ref "D14") (pin "2") (pinfunction "A_2") (pintype "passive"))
      (node (ref "D15") (pin "2") (pinfunction "A_2") (pintype "passive"))
      (node (ref "D16") (pin "2") (pinfunction "A_2") (pintype "passive"))
      (node (ref "D17") (pin "2") (pinfunction "A_2") (pintype "passive"))
      (node (ref "D18") (pin "2") (pinfunction "A_2") (pintype "passive"))
      (node (ref "D19") (pin "2") (pinfunction "A_2") (pintype "passive"))
      (node (ref "D20") (pin "2") (pinfunction "A_2") (pintype "passive"))
      (node (ref "D21") (pin "2") (pinfunction "A_2") (pintype "passive"))
      (node (ref "D22") (pin "2") (pinfunction "A_2") (pintype "passive"))
      (node (ref "D23") (pin "2") (pinfunction "A_2") (pintype "passive"))
      (node (ref "D24") (pin "2") (pinfunction "A_2") (pintype "passive"))
      (node (ref "D25") (pin "2") (pinfunction "A_2") (pintype "passive"))
      (node (ref "U11") (pin "7") (pinfunction "VCC_7") (pintype "passive"))
      (node (ref "U12") (pin "7") (pinfunction "VCC_7") (pintype "passive"))
      (node (ref "U13") (pin "7") (pinfunction "VCC_7") (pintype "passive"))
      (node (ref "U14") (pin "7") (pinfunction "VCC_7") (pintype "passive"))
      (node (ref "U15") (pin "7") (pinfunction "VCC_7") (pintype "passive"))
      (node (ref "U16") (pin "7") (pinfunction "VCC_7") (pintype "passive"))
      (node (ref "U17") (pin "7") (pinfunction "VCC_7") (pintype "passive"))
      (node (ref "U18") (pin "7") (pinfunction "VCC_7") (pintype "passive"))
      (node (ref "U19") (pin "7") (pinfunction "VCC_7") (pintype "passive"))
      (node (ref "U20") (pin "7") (pinfunction "VCC_7") (pintype "passive"))
      (node (ref "U21") (pin "7") (pinfunction "VCC_7") (pintype "passive"))
      (node (ref "U22") (pin "7") (pinfunction "VCC_7") (pintype "passive"))
      (node (ref "U23") (pin "7") (pinfunction "VCC_7") (pintype "passive"))
      (node (ref "U24") (pin "7") (pinfunction "VCC_7") (pintype "passive"))
      (node (ref "U25") (pin "7") (pinfunction "VCC_7") (pintype "passive"))
      (node (ref "U26") (pin "7") (pinfunction "VCC_7") (pintype "passive"))
    )
    (net (code "4") (name "/12V") (class "Default")
      (node (ref "C101") (pin "2") (pinfunction "2_2") (pintype "passive"))
      (node (ref "C102") (pin "2") (pinfunction "2_2") (pintype "passive"))
      (node (ref "C106") (pin "2") (pinfunction "2_2") (pintype "passive"))
      (node (ref "C107") (pin "2") (pinfunction "2_2") (pintype "passive"))
      (node (ref "C111") (pin "2") (pinfunction "2_2") (pintype "passive"))
      (node (ref "C112") (pin "2") (pinfunction "2_2") (pintype "passive"))
      (node (ref "C128") (pin "2") (pinfunction "2_2") (pintype "passive"))
      (node (ref "C129") (pin "2") (pinfunction "2_2") (pintype "passive"))
      (node (ref "C133") (pin "2") (pinfunction "2_2") (pintype "passive"))
      (node (ref "C134") (pin "2") (pinfunction "2_2") (pintype "passive"))
      (node (ref "C138") (pin "2") (pinfunction "2_2") (pintype "passive"))
      (node (ref "C139") (pin "2") (pinfunction "2_2") (pintype "passive"))
      (node (ref "C143") (pin "2") (pinfunction "2_2") (pintype "passive"))
      (node (ref "C144") (pin "2") (pinfunction "2_2") (pintype "passive"))
      (node (ref "C32") (pin "2") (pinfunction "2_2") (pintype "passive"))
      (node (ref "C33") (pin "2") (pinfunction "2_2") (pintype "passive"))
      (node (ref "C348") (pin "2") (pinfunction "2_2") (pintype "passive"))
      (node (ref "C349") (pin "2") (pinfunction "2_2") (pintype "passive"))
      (node (ref "C353") (pin "2") (pinfunction "2_2") (pintype "passive"))
      (node (ref "C354") (pin "2") (pinfunction "2_2") (pintype "passive"))
      (node (ref "C358") (pin "2") (pinfunction "2_2") (pintype "passive"))
      (node (ref "C359") (pin "2") (pinfunction "2_2") (pintype "passive"))
      (node (ref "C363") (pin "2") (pinfunction "2_2") (pintype "passive"))
      (node (ref "C364") (pin "2") (pinfunction "2_2") (pintype "passive"))
      (node (ref "C368") (pin "2") (pinfunction "2_2") (pintype "passive"))
      (node (ref "C369") (pin "2") (pinfunction "2_2") (pintype "passive"))
      (node (ref "C37") (pin "2") (pinfunction "2_2") (pintype "passive"))
      (node (ref "C373") (pin "2") (pinfunction "2_2") (pintype "passive"))
      (node (ref "C374") (pin "2") (pinfunction "2_2") (pintype "passive"))
      (node (ref "C378") (pin "2") (pinfunction "2_2") (pintype "passive"))
      (node (ref "C379") (pin "2") (pinfunction "2_2") (pintype "passive"))
      (node (ref "C38") (pin "2") (pinfunction "2_2") (pintype "passive"))
      (node (ref "C383") (pin "2") (pinfunction "2_2") (pintype "passive"))
      (node (ref "C384") (pin "2") (pinfunction "2_2") (pintype "passive"))
      (node (ref "C391") (pin "2") (pinfunction "2_2") (pintype "passive"))
      (node (ref "C392") (pin "2") (pinfunction "2_2") (pintype "passive"))
      (node (ref "C402") (pin "2") (pinfunction "2_2") (pintype "passive"))
      (node (ref "C403") (pin "2") (pinfunction "2_2") (pintype "passive"))
      (node (ref "C404") (pin "2") (pinfunction "2_2") (pintype "passive"))
      (node (ref "C405") (pin "2") (pinfunction "2_2") (pintype "passive"))
      (node (ref "C406") (pin "2") (pinfunction "2_2") (pintype "passive"))
      (node (ref "C407") (pin "2") (pinfunction "2_2") (pintype "passive"))
      (node (ref "C42") (pin "2") (pinfunction "2_2") (pintype "passive"))
      (node (ref "C420") (pin "2") (pinfunction "2_2") (pintype "passive"))
      (node (ref "C421") (pin "2") (pinfunction "2_2") (pintype "passive"))
      (node (ref "C422") (pin "2") (pinfunction "2_2") (pintype "passive"))
      (node (ref "C423") (pin "2") (pinfunction "2_2") (pintype "passive"))
      (node (ref "C424") (pin "2") (pinfunction "2_2") (pintype "passive"))
      (node (ref "C425") (pin "2") (pinfunction "2_2") (pintype "passive"))
      (node (ref "C426") (pin "2") (pinfunction "2_2") (pintype "passive"))
      (node (ref "C427") (pin "2") (pinfunction "2_2") (pintype "passive"))
      (node (ref "C43") (pin "2") (pinfunction "2_2") (pintype "passive"))
      (node (ref "C47") (pin "2") (pinfunction "2_2") (pintype "passive"))
      (node (ref "C48") (pin "2") (pinfunction "2_2") (pintype "passive"))
      (node (ref "C64") (pin "2") (pinfunction "2_2") (pintype "passive"))
      (node (ref "C65") (pin "2") (pinfunction "2_2") (pintype "passive"))
      (node (ref "C69") (pin "2") (pinfunction "2_2") (pintype "passive"))
      (node (ref "C70") (pin "2") (pinfunction "2_2") (pintype "passive"))
      (node (ref "C74") (pin "2") (pinfunction "2_2") (pintype "passive"))
      (node (ref "C75") (pin "2") (pinfunction "2_2") (pintype "passive"))
      (node (ref "C79") (pin "2") (pinfunction "2_2") (pintype "passive"))
      (node (ref "C80") (pin "2") (pinfunction "2_2") (pintype "passive"))
      (node (ref "C96") (pin "2") (pinfunction "2_2") (pintype "passive"))
      (node (ref "C97") (pin "2") (pinfunction "2_2") (pintype "passive"))
      (node (ref "Q1") (pin "5") (pinfunction "D_5") (pintype "passive"))
      (node (ref "Q1") (pin "6") (pinfunction "D_6") (pintype "passive"))
      (node (ref "Q1") (pin "7") (pinfunction "D_7") (pintype "passive"))
      (node (ref "Q1") (pin "8") (pinfunction "D_8") (pintype "passive"))
      (node (ref "Q13") (pin "5") (pinfunction "D_5") (pintype "passive"))
      (node (ref "Q13") (pin "6") (pinfunction "D_6") (pintype "passive"))
      (node (ref "Q13") (pin "7") (pinfunction "D_7") (pintype "passive"))
      (node (ref "Q13") (pin "8") (pinfunction "D_8") (pintype "passive"))
      (node (ref "Q14") (pin "5") (pinfunction "D_5") (pintype "passive"))
      (node (ref "Q14") (pin "6") (pinfunction "D_6") (pintype "passive"))
      (node (ref "Q14") (pin "7") (pinfunction "D_7") (pintype "passive"))
      (node (ref "Q14") (pin "8") (pinfunction "D_8") (pintype "passive"))
      (node (ref "Q15") (pin "5") (pinfunction "D_5") (pintype "passive"))
      (node (ref "Q15") (pin "6") (pinfunction "D_6") (pintype "passive"))
      (node (ref "Q15") (pin "7") (pinfunction "D_7") (pintype "passive"))
      (node (ref "Q15") (pin "8") (pinfunction "D_8") (pintype "passive"))
      (node (ref "Q16") (pin "5") (pinfunction "D_5") (pintype "passive"))
      (node (ref "Q16") (pin "6") (pinfunction "D_6") (pintype "passive"))
      (node (ref "Q16") (pin "7") (pinfunction "D_7") (pintype "passive"))
      (node (ref "Q16") (pin "8") (pinfunction "D_8") (pintype "passive"))
      (node (ref "Q2") (pin "5") (pinfunction "D_5") (pintype "passive"))
      (node (ref "Q2") (pin "6") (pinfunction "D_6") (pintype "passive"))
      (node (ref "Q2") (pin "7") (pinfunction "D_7") (pintype "passive"))
      (node (ref "Q2") (pin "8") (pinfunction "D_8") (pintype "passive"))
      (node (ref "Q25") (pin "5") (pinfunction "D_5") (pintype "passive"))
      (node (ref "Q25") (pin "6") (pinfunction "D_6") (pintype "passive"))
      (node (ref "Q25") (pin "7") (pinfunction "D_7") (pintype "passive"))
      (node (ref "Q25") (pin "8") (pinfunction "D_8") (pintype "passive"))
      (node (ref "Q26") (pin "5") (pinfunction "D_5") (pintype "passive"))
      (node (ref "Q26") (pin "6") (pinfunction "D_6") (pintype "passive"))
      (node (ref "Q26") (pin "7") (pinfunction "D_7") (pintype "passive"))
      (node (ref "Q26") (pin "8") (pinfunction "D_8") (pintype "passive"))
      (node (ref "Q27") (pin "5") (pinfunction "D_5") (pintype "passive"))
      (node (ref "Q27") (pin "6") (pinfunction "D_6") (pintype "passive"))
      (node (ref "Q27") (pin "7") (pinfunction "D_7") (pintype "passive"))
      (node (ref "Q27") (pin "8") (pinfunction "D_8") (pintype "passive"))
      (node (ref "Q28") (pin "5") (pinfunction "D_5") (pintype "passive"))
      (node (ref "Q28") (pin "6") (pinfunction "D_6") (pintype "passive"))
      (node (ref "Q28") (pin "7") (pinfunction "D_7") (pintype "passive"))
      (node (ref "Q28") (pin "8") (pinfunction "D_8") (pintype "passive"))
      (node (ref "Q3") (pin "5") (pinfunction "D_5") (pintype "passive"))
      (node (ref "Q3") (pin "6") (pinfunction "D_6") (pintype "passive"))
      (node (ref "Q3") (pin "7") (pinfunction "D_7") (pintype "passive"))
      (node (ref "Q3") (pin "8") (pinfunction "D_8") (pintype "passive"))
      (node (ref "Q37") (pin "5") (pinfunction "D_5") (pintype "passive"))
      (node (ref "Q37") (pin "6") (pinfunction "D_6") (pintype "passive"))
      (node (ref "Q37") (pin "7") (pinfunction "D_7") (pintype "passive"))
      (node (ref "Q37") (pin "8") (pinfunction "D_8") (pintype "passive"))
      (node (ref "Q38") (pin "5") (pinfunction "D_5") (pintype "passive"))
      (node (ref "Q38") (pin "6") (pinfunction "D_6") (pintype "passive"))
      (node (ref "Q38") (pin "7") (pinfunction "D_7") (pintype "passive"))
      (node (ref "Q38") (pin "8") (pinfunction "D_8") (pintype "passive"))
      (node (ref "Q39") (pin "5") (pinfunction "D_5") (pintype "passive"))
      (node (ref "Q39") (pin "6") (pinfunction "D_6") (pintype "passive"))
      (node (ref "Q39") (pin "7") (pinfunction "D_7") (pintype "passive"))
      (node (ref "Q39") (pin "8") (pinfunction "D_8") (pintype "passive"))
      (node (ref "Q4") (pin "5") (pinfunction "D_5") (pintype "passive"))
      (node (ref "Q4") (pin "6") (pinfunction "D_6") (pintype "passive"))
      (node (ref "Q4") (pin "7") (pinfunction "D_7") (pintype "passive"))
      (node (ref "Q4") (pin "8") (pinfunction "D_8") (pintype "passive"))
      (node (ref "Q40") (pin "5") (pinfunction "D_5") (pintype "passive"))
      (node (ref "Q40") (pin "6") (pinfunction "D_6") (pintype "passive"))
      (node (ref "Q40") (pin "7") (pinfunction "D_7") (pintype "passive"))
      (node (ref "Q40") (pin "8") (pinfunction "D_8") (pintype "passive"))
    )
    (net (code "5") (name "/BOOT1") (class "Default")
      (node (ref "C28") (pin "1") (pinfunction "1_1") (pintype "passive"))
      (node (ref "D10") (pin "1") (pinfunction "C_1") (pintype "passive"))
      (node (ref "U11") (pin "8") (pinfunction "BOOST_8") (pintype "passive"))
    )
    (net (code "6") (name "/BOOT2") (class "Default")
      (node (ref "C60") (pin "1") (pinfunction "1_1") (pintype "passive"))
      (node (ref "D14") (pin "1") (pinfunction "C_1") (pintype "passive"))
      (node (ref "U15") (pin "8") (pinfunction "BOOST_8") (pintype "passive"))
    )
    (net (code "7") (name "/BOOT3") (class "Default")
      (node (ref "C92") (pin "1") (pinfunction "1_1") (pintype "passive"))
      (node (ref "D18") (pin "1") (pinfunction "C_1") (pintype "passive"))
      (node (ref "U19") (pin "8") (pinfunction "BOOST_8") (pintype "passive"))
    )
    (net (code "8") (name "/BOOT4") (class "Default")
      (node (ref "C124") (pin "1") (pinfunction "1_1") (pintype "passive"))
      (node (ref "D22") (pin "1") (pinfunction "C_1") (pintype "passive"))
      (node (ref "U23") (pin "8") (pinfunction "BOOST_8") (pintype "passive"))
    )
    (net (code "9") (name "/BOOT5") (class "Default")
      (node (ref "C29") (pin "1") (pinfunction "1_1") (pintype "passive"))
      (node (ref "D11") (pin "1") (pinfunction "C_1") (pintype "passive"))
      (node (ref "U12") (pin "8") (pinfunction "BOOST_8") (pintype "passive"))
    )
    (net (code "10") (name "/BOOT6") (class "Default")
      (node (ref "C61") (pin "1") (pinfunction "1_1") (pintype "passive"))
      (node (ref "D15") (pin "1") (pinfunction "C_1") (pintype "passive"))
      (node (ref "U16") (pin "8") (pinfunction "BOOST_8") (pintype "passive"))
    )
    (net (code "11") (name "/BOOT7") (class "Default")
      (node (ref "C93") (pin "1") (pinfunction "1_1") (pintype "passive"))
      (node (ref "D19") (pin "1") (pinfunction "C_1") (pintype "passive"))
      (node (ref "U20") (pin "8") (pinfunction "BOOST_8") (pintype "passive"))
    )
    (net (code "12") (name "/BOOT8") (class "Default")
      (node (ref "C125") (pin "1") (pinfunction "1_1") (pintype "passive"))
      (node (ref "D23") (pin "1") (pinfunction "C_1") (pintype "passive"))
      (node (ref "U24") (pin "8") (pinfunction "BOOST_8") (pintype "passive"))
    )
    (net (code "13") (name "/BOOT9") (class "Default")
      (node (ref "C30") (pin "1") (pinfunction "1_1") (pintype "passive"))
      (node (ref "D12") (pin "1") (pinfunction "C_1") (pintype "passive"))
      (node (ref "U13") (pin "8") (pinfunction "BOOST_8") (pintype "passive"))
    )
    (net (code "14") (name "/BOOT10") (class "Default")
      (node (ref "C62") (pin "1") (pinfunction "1_1") (pintype "passive"))
      (node (ref "D16") (pin "1") (pinfunction "C_1") (pintype "passive"))
      (node (ref "U17") (pin "8") (pinfunction "BOOST_8") (pintype "passive"))
    )
    (net (code "15") (name "/BOOT11") (class "Default")
      (node (ref "C94") (pin "1") (pinfunction "1_1") (pintype "passive"))
      (node (ref "D20") (pin "1") (pinfunction "C_1") (pintype "passive"))
      (node (ref "U21") (pin "8") (pinfunction "BOOST_8") (pintype "passive"))
    )
    (net (code "16") (name "/BOOT12") (class "Default")
      (node (ref "C126") (pin "1") (pinfunction "1_1") (pintype "passive"))
      (node (ref "D24") (pin "1") (pinfunction "C_1") (pintype "passive"))
      (node (ref "U25") (pin "8") (pinfunction "BOOST_8") (pintype "passive"))
    )
    (net (code "17") (name "/BOOT13") (class "Default")
      (node (ref "C31") (pin "1") (pinfunction "1_1") (pintype "passive"))
      (node (ref "D13") (pin "1") (pinfunction "C_1") (pintype "passive"))
      (node (ref "U14") (pin "8") (pinfunction "BOOST_8") (pintype "passive"))
    )
    (net (code "18") (name "/BOOT14") (class "Default")
      (node (ref "C63") (pin "1") (pinfunction "1_1") (pintype "passive"))
      (node (ref "D17") (pin "1") (pinfunction "C_1") (pintype "passive"))
      (node (ref "U18") (pin "8") (pinfunction "BOOST_8") (pintype "passive"))
    )
    (net (code "19") (name "/BOOT15") (class "Default")
      (node (ref "C95") (pin "1") (pinfunction "1_1") (pintype "passive"))
      (node (ref "D21") (pin "1") (pinfunction "C_1") (pintype "passive"))
      (node (ref "U22") (pin "8") (pinfunction "BOOST_8") (pintype "passive"))
    )
    (net (code "20") (name "/BOOT16") (class "Default")
      (node (ref "C127") (pin "1") (pinfunction "1_1") (pintype "passive"))
      (node (ref "D25") (pin "1") (pinfunction "C_1") (pintype "passive"))
      (node (ref "U26") (pin "8") (pinfunction "BOOST_8") (pintype "passive"))
    )
    (net (code "21") (name "/HO1") (class "Default")
      (node (ref "Q1") (pin "4") (pinfunction "G_4") (pintype "passive"))
      (node (ref "U11") (pin "1") (pinfunction "TG_1") (pintype "passive"))
    )
    (net (code "22") (name "/HO2") (class "Default")
      (node (ref "Q13") (pin "4") (pinfunction "G_4") (pintype "passive"))
      (node (ref "U15") (pin "1") (pinfunction "TG_1") (pintype "passive"))
    )
    (net (code "23") (name "/HO3") (class "Default")
      (node (ref "Q25") (pin "4") (pinfunction "G_4") (pintype "passive"))
      (node (ref "U19") (pin "1") (pinfunction "TG_1") (pintype "passive"))
    )
    (net (code "24") (name "/HO4") (class "Default")
      (node (ref "Q37") (pin "4") (pinfunction "G_4") (pintype "passive"))
      (node (ref "U23") (pin "1") (pinfunction "TG_1") (pintype "passive"))
    )
    (net (code "25") (name "/HO5") (class "Default")
      (node (ref "Q2") (pin "4") (pinfunction "G_4") (pintype "passive"))
      (node (ref "U12") (pin "1") (pinfunction "TG_1") (pintype "passive"))
    )
    (net (code "26") (name "/HO6") (class "Default")
      (node (ref "Q14") (pin "4") (pinfunction "G_4") (pintype "passive"))
      (node (ref "U16") (pin "1") (pinfunction "TG_1") (pintype "passive"))
    )
    (net (code "27") (name "/HO7") (class "Default")
      (node (ref "Q26") (pin "4") (pinfunction "G_4") (pintype "passive"))
      (node (ref "U20") (pin "1") (pinfunction "TG_1") (pintype "passive"))
    )
    (net (code "28") (name "/HO8") (class "Default")
      (node (ref "Q38") (pin "4") (pinfunction "G_4") (pintype "passive"))
      (node (ref "U24") (pin "1") (pinfunction "TG_1") (pintype "passive"))
    )
    (net (code "29") (name "/HO9") (class "Default")
      (node (ref "Q3") (pin "4") (pinfunction "G_4") (pintype "passive"))
      (node (ref "U13") (pin "1") (pinfunction "TG_1") (pintype "passive"))
    )
    (net (code "30") (name "/HO10") (class "Default")
      (node (ref "Q15") (pin "4") (pinfunction "G_4") (pintype "passive"))
      (node (ref "U17") (pin "1") (pinfunction "TG_1") (pintype "passive"))
    )
    (net (code "31") (name "/HO11") (class "Default")
      (node (ref "Q27") (pin "4") (pinfunction "G_4") (pintype "passive"))
      (node (ref "U21") (pin "1") (pinfunction "TG_1") (pintype "passive"))
    )
    (net (code "32") (name "/HO12") (class "Default")
      (node (ref "Q39") (pin "4") (pinfunction "G_4") (pintype "passive"))
      (node (ref "U25") (pin "1") (pinfunction "TG_1") (pintype "passive"))
    )
    (net (code "33") (name "/HO13") (class "Default")
      (node (ref "Q4") (pin "4") (pinfunction "G_4") (pintype "passive"))
      (node (ref "U14") (pin "1") (pinfunction "TG_1") (pintype "passive"))
    )
    (net (code "34") (name "/HO14") (class "Default")
      (node (ref "Q16") (pin "4") (pinfunction "G_4") (pintype "passive"))
      (node (ref "U18") (pin "1") (pinfunction "TG_1") (pintype "passive"))
    )
    (net (code "35") (name "/HO15") (class "Default")
      (node (ref "Q28") (pin "4") (pinfunction "G_4") (pintype "passive"))
      (node (ref "U22") (pin "1") (pinfunction "TG_1") (pintype "passive"))
    )
    (net (code "36") (name "/HO16") (class "Default")
      (node (ref "Q40") (pin "4") (pinfunction "G_4") (pintype "passive"))
      (node (ref "U26") (pin "1") (pinfunction "TG_1") (pintype "passive"))
    )
    (net (code "37") (name "/LO1") (class "Default")
      (node (ref "Q5") (pin "4") (pinfunction "G_4") (pintype "passive"))
      (node (ref "Q6") (pin "4") (pinfunction "G_4") (pintype "passive"))
      (node (ref "U11") (pin "3") (pinfunction "BG_3") (pintype "passive"))
    )
    (net (code "38") (name "/LO2") (class "Default")
      (node (ref "Q17") (pin "4") (pinfunction "G_4") (pintype "passive"))
      (node (ref "Q18") (pin "4") (pinfunction "G_4") (pintype "passive"))
      (node (ref "U15") (pin "3") (pinfunction "BG_3") (pintype "passive"))
    )
    (net (code "39") (name "/LO3") (class "Default")
      (node (ref "Q29") (pin "4") (pinfunction "G_4") (pintype "passive"))
      (node (ref "Q30") (pin "4") (pinfunction "G_4") (pintype "passive"))
      (node (ref "U19") (pin "3") (pinfunction "BG_3") (pintype "passive"))
    )
    (net (code "40") (name "/LO4") (class "Default")
      (node (ref "Q41") (pin "4") (pinfunction "G_4") (pintype "passive"))
      (node (ref "Q42") (pin "4") (pinfunction "G_4") (pintype "passive"))
      (node (ref "U23") (pin "3") (pinfunction "BG_3") (pintype "passive"))
    )
    (net (code "41") (name "/LO5") (class "Default")
      (node (ref "Q7") (pin "4") (pinfunction "G_4") (pintype "passive"))
      (node (ref "Q8") (pin "4") (pinfunction "G_4") (pintype "passive"))
      (node (ref "U12") (pin "3") (pinfunction "BG_3") (pintype "passive"))
    )
    (net (code "42") (name "/LO6") (class "Default")
      (node (ref "Q19") (pin "4") (pinfunction "G_4") (pintype "passive"))
      (node (ref "Q20") (pin "4") (pinfunction "G_4") (pintype "passive"))
      (node (ref "U16") (pin "3") (pinfunction "BG_3") (pintype "passive"))
    )
    (net (code "43") (name "/LO7") (class "Default")
      (node (ref "Q31") (pin "4") (pinfunction "G_4") (pintype "passive"))
      (node (ref "Q32") (pin "4") (pinfunction "G_4") (pintype "passive"))
      (node (ref "U20") (pin "3") (pinfunction "BG_3") (pintype "passive"))
    )
    (net (code "44") (name "/LO8") (class "Default")
      (node (ref "Q43") (pin "4") (pinfunction "G_4") (pintype "passive"))
      (node (ref "Q44") (pin "4") (pinfunction "G_4") (pintype "passive"))
      (node (ref "U24") (pin "3") (pinfunction "BG_3") (pintype "passive"))
    )
    (net (code "45") (name "/LO9") (class "Default")
      (node (ref "Q10") (pin "4") (pinfunction "G_4") (pintype "passive"))
      (node (ref "Q9") (pin "4") (pinfunction "G_4") (pintype "passive"))
      (node (ref "U13") (pin "3") (pinfunction "BG_3") (pintype "passive"))
    )
    (net (code "46") (name "/LO10") (class "Default")
      (node (ref "Q21") (pin "4") (pinfunction "G_4") (pintype "passive"))
      (node (ref "Q22") (pin "4") (pinfunction "G_4") (pintype "passive"))
      (node (ref "U17") (pin "3") (pinfunction "BG_3") (pintype "passive"))
    )
    (net (code "47") (name "/LO11") (class "Default")
      (node (ref "Q33") (pin "4") (pinfunction "G_4") (pintype "passive"))
      (node (ref "Q34") (pin "4") (pinfunction "G_4") (pintype "passive"))
      (node (ref "U21") (pin "3") (pinfunction "BG_3") (pintype "passive"))
    )
    (net (code "48") (name "/LO12") (class "Default")
      (node (ref "Q45") (pin "4") (pinfunction "G_4") (pintype "passive"))
      (node (ref "Q46") (pin "4") (pinfunction "G_4") (pintype "passive"))
      (node (ref "U25") (pin "3") (pinfunction "BG_3") (pintype "passive"))
    )
    (net (code "49") (name "/LO13") (class "Default")
      (node (ref "Q11") (pin "4") (pinfunction "G_4") (pintype "passive"))
      (node (ref "Q12") (pin "4") (pinfunction "G_4") (pintype "passive"))
      (node (ref "U14") (pin "3") (pinfunction "BG_3") (pintype "passive"))
    )
    (net (code "50") (name "/LO14") (class "Default")
      (node (ref "Q23") (pin "4") (pinfunction "G_4") (pintype "passive"))
      (node (ref "Q24") (pin "4") (pinfunction "G_4") (pintype "passive"))
      (node (ref "U18") (pin "3") (pinfunction "BG_3") (pintype "passive"))
    )
    (net (code "51") (name "/LO15") (class "Default")
      (node (ref "Q35") (pin "4") (pinfunction "G_4") (pintype "passive"))
      (node (ref "Q36") (pin "4") (pinfunction "G_4") (pintype "passive"))
      (node (ref "U22") (pin "3") (pinfunction "BG_3") (pintype "passive"))
    )
    (net (code "52") (name "/LO16") (class "Default")
      (node (ref "Q47") (pin "4") (pinfunction "G_4") (pintype "passive"))
      (node (ref "Q48") (pin "4") (pinfunction "G_4") (pintype "passive"))
      (node (ref "U26") (pin "3") (pinfunction "BG_3") (pintype "passive"))
    )
    (net (code "53") (name "/PWM1H") (class "Default")
      (node (ref "U12") (pin "5") (pinfunction "IN_5") (pintype "passive"))
      (node (ref "U14") (pin "5") (pinfunction "IN_5") (pintype "passive"))
    )
    (net (code "54") (name "/PWM1L") (class "Default")
      (node (ref "U11") (pin "5") (pinfunction "IN_5") (pintype "passive"))
      (node (ref "U13") (pin "5") (pinfunction "IN_5") (pintype "passive"))
    )
    (net (code "55") (name "/PWM2H") (class "Default")
      (node (ref "U16") (pin "5") (pinfunction "IN_5") (pintype "passive"))
      (node (ref "U18") (pin "5") (pinfunction "IN_5") (pintype "passive"))
    )
    (net (code "56") (name "/PWM2L") (class "Default")
      (node (ref "U15") (pin "5") (pinfunction "IN_5") (pintype "passive"))
      (node (ref "U17") (pin "5") (pinfunction "IN_5") (pintype "passive"))
    )
    (net (code "57") (name "/PWM3H") (class "Default")
      (node (ref "U20") (pin "5") (pinfunction "IN_5") (pintype "passive"))
      (node (ref "U22") (pin "5") (pinfunction "IN_5") (pintype "passive"))
    )
    (net (code "58") (name "/PWM3L") (class "Default")
      (node (ref "U19") (pin "5") (pinfunction "IN_5") (pintype "passive"))
      (node (ref "U21") (pin "5") (pinfunction "IN_5") (pintype "passive"))
    )
    (net (code "59") (name "/PWM4H") (class "Default")
      (node (ref "U24") (pin "5") (pinfunction "IN_5") (pintype "passive"))
      (node (ref "U26") (pin "5") (pinfunction "IN_5") (pintype "passive"))
    )
    (net (code "60") (name "/PWM4L") (class "Default")
      (node (ref "U23") (pin "5") (pinfunction "IN_5") (pintype "passive"))
      (node (ref "U25") (pin "5") (pinfunction "IN_5") (pintype "passive"))
    )
    (net (code "61") (name "/SWN1") (class "Default")
      (node (ref "C28") (pin "2") (pinfunction "2_2") (pintype "passive"))
      (node (ref "L1") (pin "1") (pinfunction "1_1") (pintype "passive"))
      (node (ref "Q1") (pin "1") (pinfunction "S_1") (pintype "passive"))
      (node (ref "Q1") (pin "2") (pinfunction "S_2") (pintype "passive"))
      (node (ref "Q1") (pin "3") (pinfunction "S_3") (pintype "passive"))
      (node (ref "Q5") (pin "5") (pinfunction "D_5") (pintype "passive"))
      (node (ref "Q5") (pin "6") (pinfunction "D_6") (pintype "passive"))
      (node (ref "Q5") (pin "7") (pinfunction "D_7") (pintype "passive"))
      (node (ref "Q5") (pin "8") (pinfunction "D_8") (pintype "passive"))
      (node (ref "Q6") (pin "5") (pinfunction "D_5") (pintype "passive"))
      (node (ref "Q6") (pin "6") (pinfunction "D_6") (pintype "passive"))
      (node (ref "Q6") (pin "7") (pinfunction "D_7") (pintype "passive"))
      (node (ref "Q6") (pin "8") (pinfunction "D_8") (pintype "passive"))
      (node (ref "U11") (pin "2") (pinfunction "TS_2") (pintype "passive"))
    )
    (net (code "62") (name "/SWN2") (class "Default")
      (node (ref "C60") (pin "2") (pinfunction "2_2") (pintype "passive"))
      (node (ref "L5") (pin "1") (pinfunction "1_1") (pintype "passive"))
      (node (ref "Q13") (pin "1") (pinfunction "S_1") (pintype "passive"))
      (node (ref "Q13") (pin "2") (pinfunction "S_2") (pintype "passive"))
      (node (ref "Q13") (pin "3") (pinfunction "S_3") (pintype "passive"))
      (node (ref "Q17") (pin "5") (pinfunction "D_5") (pintype "passive"))
      (node (ref "Q17") (pin "6") (pinfunction "D_6") (pintype "passive"))
      (node (ref "Q17") (pin "7") (pinfunction "D_7") (pintype "passive"))
      (node (ref "Q17") (pin "8") (pinfunction "D_8") (pintype "passive"))
      (node (ref "Q18") (pin "5") (pinfunction "D_5") (pintype "passive"))
      (node (ref "Q18") (pin "6") (pinfunction "D_6") (pintype "passive"))
      (node (ref "Q18") (pin "7") (pinfunction "D_7") (pintype "passive"))
      (node (ref "Q18") (pin "8") (pinfunction "D_8") (pintype "passive"))
      (node (ref "U15") (pin "2") (pinfunction "TS_2") (pintype "passive"))
    )
    (net (code "63") (name "/SWN3") (class "Default")
      (node (ref "C92") (pin "2") (pinfunction "2_2") (pintype "passive"))
      (node (ref "L9") (pin "1") (pinfunction "1_1") (pintype "passive"))
      (node (ref "Q25") (pin "1") (pinfunction "S_1") (pintype "passive"))
      (node (ref "Q25") (pin "2") (pinfunction "S_2") (pintype "passive"))
      (node (ref "Q25") (pin "3") (pinfunction "S_3") (pintype "passive"))
      (node (ref "Q29") (pin "5") (pinfunction "D_5") (pintype "passive"))
      (node (ref "Q29") (pin "6") (pinfunction "D_6") (pintype "passive"))
      (node (ref "Q29") (pin "7") (pinfunction "D_7") (pintype "passive"))
      (node (ref "Q29") (pin "8") (pinfunction "D_8") (pintype "passive"))
      (node (ref "Q30") (pin "5") (pinfunction "D_5") (pintype "passive"))
      (node (ref "Q30") (pin "6") (pinfunction "D_6") (pintype "passive"))
      (node (ref "Q30") (pin "7") (pinfunction "D_7") (pintype "passive"))
      (node (ref "Q30") (pin "8") (pinfunction "D_8") (pintype "passive"))
      (node (ref "U19") (pin "2") (pinfunction "TS_2") (pintype "passive"))
    )
    (net (code "64") (name "/SWN4") (class "Default")
      (node (ref "C124") (pin "2") (pinfunction "2_2") (pintype "passive"))
      (node (ref "L13") (pin "1") (pinfunction "1_1") (pintype "passive"))
      (node (ref "Q37") (pin "1") (pinfunction "S_1") (pintype "passive"))
      (node (ref "Q37") (pin "2") (pinfunction "S_2") (pintype "passive"))
      (node (ref "Q37") (pin "3") (pinfunction "S_3") (pintype "passive"))
      (node (ref "Q41") (pin "5") (pinfunction "D_5") (pintype "passive"))
      (node (ref "Q41") (pin "6") (pinfunction "D_6") (pintype "passive"))
      (node (ref "Q41") (pin "7") (pinfunction "D_7") (pintype "passive"))
      (node (ref "Q41") (pin "8") (pinfunction "D_8") (pintype "passive"))
      (node (ref "Q42") (pin "5") (pinfunction "D_5") (pintype "passive"))
      (node (ref "Q42") (pin "6") (pinfunction "D_6") (pintype "passive"))
      (node (ref "Q42") (pin "7") (pinfunction "D_7") (pintype "passive"))
      (node (ref "Q42") (pin "8") (pinfunction "D_8") (pintype "passive"))
      (node (ref "U23") (pin "2") (pinfunction "TS_2") (pintype "passive"))
    )
    (net (code "65") (name "/SWN5") (class "Default")
      (node (ref "C29") (pin "2") (pinfunction "2_2") (pintype "passive"))
      (node (ref "L2") (pin "1") (pinfunction "1_1") (pintype "passive"))
      (node (ref "Q2") (pin "1") (pinfunction "S_1") (pintype "passive"))
      (node (ref "Q2") (pin "2") (pinfunction "S_2") (pintype "passive"))
      (node (ref "Q2") (pin "3") (pinfunction "S_3") (pintype "passive"))
      (node (ref "Q7") (pin "5") (pinfunction "D_5") (pintype "passive"))
      (node (ref "Q7") (pin "6") (pinfunction "D_6") (pintype "passive"))
      (node (ref "Q7") (pin "7") (pinfunction "D_7") (pintype "passive"))
      (node (ref "Q7") (pin "8") (pinfunction "D_8") (pintype "passive"))
      (node (ref "Q8") (pin "5") (pinfunction "D_5") (pintype "passive"))
      (node (ref "Q8") (pin "6") (pinfunction "D_6") (pintype "passive"))
      (node (ref "Q8") (pin "7") (pinfunction "D_7") (pintype "passive"))
      (node (ref "Q8") (pin "8") (pinfunction "D_8") (pintype "passive"))
      (node (ref "U12") (pin "2") (pinfunction "TS_2") (pintype "passive"))
    )
    (net (code "66") (name "/SWN6") (class "Default")
      (node (ref "C61") (pin "2") (pinfunction "2_2") (pintype "passive"))
      (node (ref "L6") (pin "1") (pinfunction "1_1") (pintype "passive"))
      (node (ref "Q14") (pin "1") (pinfunction "S_1") (pintype "passive"))
      (node (ref "Q14") (pin "2") (pinfunction "S_2") (pintype "passive"))
      (node (ref "Q14") (pin "3") (pinfunction "S_3") (pintype "passive"))
      (node (ref "Q19") (pin "5") (pinfunction "D_5") (pintype "passive"))
      (node (ref "Q19") (pin "6") (pinfunction "D_6") (pintype "passive"))
      (node (ref "Q19") (pin "7") (pinfunction "D_7") (pintype "passive"))
      (node (ref "Q19") (pin "8") (pinfunction "D_8") (pintype "passive"))
      (node (ref "Q20") (pin "5") (pinfunction "D_5") (pintype "passive"))
      (node (ref "Q20") (pin "6") (pinfunction "D_6") (pintype "passive"))
      (node (ref "Q20") (pin "7") (pinfunction "D_7") (pintype "passive"))
      (node (ref "Q20") (pin "8") (pinfunction "D_8") (pintype "passive"))
      (node (ref "U16") (pin "2") (pinfunction "TS_2") (pintype "passive"))
    )
    (net (code "67") (name "/SWN7") (class "Default")
      (node (ref "C93") (pin "2") (pinfunction "2_2") (pintype "passive"))
      (node (ref "L10") (pin "1") (pinfunction "1_1") (pintype "passive"))
      (node (ref "Q26") (pin "1") (pinfunction "S_1") (pintype "passive"))
      (node (ref "Q26") (pin "2") (pinfunction "S_2") (pintype "passive"))
      (node (ref "Q26") (pin "3") (pinfunction "S_3") (pintype "passive"))
      (node (ref "Q31") (pin "5") (pinfunction "D_5") (pintype "passive"))
      (node (ref "Q31") (pin "6") (pinfunction "D_6") (pintype "passive"))
      (node (ref "Q31") (pin "7") (pinfunction "D_7") (pintype "passive"))
      (node (ref "Q31") (pin "8") (pinfunction "D_8") (pintype "passive"))
      (node (ref "Q32") (pin "5") (pinfunction "D_5") (pintype "passive"))
      (node (ref "Q32") (pin "6") (pinfunction "D_6") (pintype "passive"))
      (node (ref "Q32") (pin "7") (pinfunction "D_7") (pintype "passive"))
      (node (ref "Q32") (pin "8") (pinfunction "D_8") (pintype "passive"))
      (node (ref "U20") (pin "2") (pinfunction "TS_2") (pintype "passive"))
    )
    (net (code "68") (name "/SWN8") (class "Default")
      (node (ref "C125") (pin "2") (pinfunction "2_2") (pintype "passive"))
      (node (ref "L14") (pin "1") (pinfunction "1_1") (pintype "passive"))
      (node (ref "Q38") (pin "1") (pinfunction "S_1") (pintype "passive"))
      (node (ref "Q38") (pin "2") (pinfunction "S_2") (pintype "passive"))
      (node (ref "Q38") (pin "3") (pinfunction "S_3") (pintype "passive"))
      (node (ref "Q43") (pin "5") (pinfunction "D_5") (pintype "passive"))
      (node (ref "Q43") (pin "6") (pinfunction "D_6") (pintype "passive"))
      (node (ref "Q43") (pin "7") (pinfunction "D_7") (pintype "passive"))
      (node (ref "Q43") (pin "8") (pinfunction "D_8") (pintype "passive"))
      (node (ref "Q44") (pin "5") (pinfunction "D_5") (pintype "passive"))
      (node (ref "Q44") (pin "6") (pinfunction "D_6") (pintype "passive"))
      (node (ref "Q44") (pin "7") (pinfunction "D_7") (pintype "passive"))
      (node (ref "Q44") (pin "8") (pinfunction "D_8") (pintype "passive"))
      (node (ref "U24") (pin "2") (pinfunction "TS_2") (pintype "passive"))
    )
    (net (code "69") (name "/SWN9") (class "Default")
      (node (ref "C30") (pin "2") (pinfunction "2_2") (pintype "passive"))
      (node (ref "L3") (pin "1") (pinfunction "1_1") (pintype "passive"))
      (node (ref "Q10") (pin "5") (pinfunction "D_5") (pintype "passive"))
      (node (ref "Q10") (pin "6") (pinfunction "D_6") (pintype "passive"))
      (node (ref "Q10") (pin "7") (pinfunction "D_7") (pintype "passive"))
      (node (ref "Q10") (pin "8") (pinfunction "D_8") (pintype "passive"))
      (node (ref "Q3") (pin "1") (pinfunction "S_1") (pintype "passive"))
      (node (ref "Q3") (pin "2") (pinfunction "S_2") (pintype "passive"))
      (node (ref "Q3") (pin "3") (pinfunction "S_3") (pintype "passive"))
      (node (ref "Q9") (pin "5") (pinfunction "D_5") (pintype "passive"))
      (node (ref "Q9") (pin "6") (pinfunction "D_6") (pintype "passive"))
      (node (ref "Q9") (pin "7") (pinfunction "D_7") (pintype "passive"))
      (node (ref "Q9") (pin "8") (pinfunction "D_8") (pintype "passive"))
      (node (ref "U13") (pin "2") (pinfunction "TS_2") (pintype "passive"))
    )
    (net (code "70") (name "/SWN10") (class "Default")
      (node (ref "C62") (pin "2") (pinfunction "2_2") (pintype "passive"))
      (node (ref "L7") (pin "1") (pinfunction "1_1") (pintype "passive"))
      (node (ref "Q15") (pin "1") (pinfunction "S_1") (pintype "passive"))
      (node (ref "Q15") (pin "2") (pinfunction "S_2") (pintype "passive"))
      (node (ref "Q15") (pin "3") (pinfunction "S_3") (pintype "passive"))
      (node (ref "Q21") (pin "5") (pinfunction "D_5") (pintype "passive"))
      (node (ref "Q21") (pin "6") (pinfunction "D_6") (pintype "passive"))
      (node (ref "Q21") (pin "7") (pinfunction "D_7") (pintype "passive"))
      (node (ref "Q21") (pin "8") (pinfunction "D_8") (pintype "passive"))
      (node (ref "Q22") (pin "5") (pinfunction "D_5") (pintype "passive"))
      (node (ref "Q22") (pin "6") (pinfunction "D_6") (pintype "passive"))
      (node (ref "Q22") (pin "7") (pinfunction "D_7") (pintype "passive"))
      (node (ref "Q22") (pin "8") (pinfunction "D_8") (pintype "passive"))
      (node (ref "U17") (pin "2") (pinfunction "TS_2") (pintype "passive"))
    )
    (net (code "71") (name "/SWN11") (class "Default")
      (node (ref "C94") (pin "2") (pinfunction "2_2") (pintype "passive"))
      (node (ref "L11") (pin "1") (pinfunction "1_1") (pintype "passive"))
      (node (ref "Q27") (pin "1") (pinfunction "S_1") (pintype "passive"))
      (node (ref "Q27") (pin "2") (pinfunction "S_2") (pintype "passive"))
      (node (ref "Q27") (pin "3") (pinfunction "S_3") (pintype "passive"))
      (node (ref "Q33") (pin "5") (pinfunction "D_5") (pintype "passive"))
      (node (ref "Q33") (pin "6") (pinfunction "D_6") (pintype "passive"))
      (node (ref "Q33") (pin "7") (pinfunction "D_7") (pintype "passive"))
      (node (ref "Q33") (pin "8") (pinfunction "D_8") (pintype "passive"))
      (node (ref "Q34") (pin "5") (pinfunction "D_5") (pintype "passive"))
      (node (ref "Q34") (pin "6") (pinfunction "D_6") (pintype "passive"))
      (node (ref "Q34") (pin "7") (pinfunction "D_7") (pintype "passive"))
      (node (ref "Q34") (pin "8") (pinfunction "D_8") (pintype "passive"))
      (node (ref "U21") (pin "2") (pinfunction "TS_2") (pintype "passive"))
    )
    (net (code "72") (name "/SWN12") (class "Default")
      (node (ref "C126") (pin "2") (pinfunction "2_2") (pintype "passive"))
      (node (ref "L15") (pin "1") (pinfunction "1_1") (pintype "passive"))
      (node (ref "Q39") (pin "1") (pinfunction "S_1") (pintype "passive"))
      (node (ref "Q39") (pin "2") (pinfunction "S_2") (pintype "passive"))
      (node (ref "Q39") (pin "3") (pinfunction "S_3") (pintype "passive"))
      (node (ref "Q45") (pin "5") (pinfunction "D_5") (pintype "passive"))
      (node (ref "Q45") (pin "6") (pinfunction "D_6") (pintype "passive"))
      (node (ref "Q45") (pin "7") (pinfunction "D_7") (pintype "passive"))
      (node (ref "Q45") (pin "8") (pinfunction "D_8") (pintype "passive"))
      (node (ref "Q46") (pin "5") (pinfunction "D_5") (pintype "passive"))
      (node (ref "Q46") (pin "6") (pinfunction "D_6") (pintype "passive"))
      (node (ref "Q46") (pin "7") (pinfunction "D_7") (pintype "passive"))
      (node (ref "Q46") (pin "8") (pinfunction "D_8") (pintype "passive"))
      (node (ref "U25") (pin "2") (pinfunction "TS_2") (pintype "passive"))
    )
    (net (code "73") (name "/SWN13") (class "Default")
      (node (ref "C31") (pin "2") (pinfunction "2_2") (pintype "passive"))
      (node (ref "L4") (pin "1") (pinfunction "1_1") (pintype "passive"))
      (node (ref "Q11") (pin "5") (pinfunction "D_5") (pintype "passive"))
      (node (ref "Q11") (pin "6") (pinfunction "D_6") (pintype "passive"))
      (node (ref "Q11") (pin "7") (pinfunction "D_7") (pintype "passive"))
      (node (ref "Q11") (pin "8") (pinfunction "D_8") (pintype "passive"))
      (node (ref "Q12") (pin "5") (pinfunction "D_5") (pintype "passive"))
      (node (ref "Q12") (pin "6") (pinfunction "D_6") (pintype "passive"))
      (node (ref "Q12") (pin "7") (pinfunction "D_7") (pintype "passive"))
      (node (ref "Q12") (pin "8") (pinfunction "D_8") (pintype "passive"))
      (node (ref "Q4") (pin "1") (pinfunction "S_1") (pintype "passive"))
      (node (ref "Q4") (pin "2") (pinfunction "S_2") (pintype "passive"))
      (node (ref "Q4") (pin "3") (pinfunction "S_3") (pintype "passive"))
      (node (ref "U14") (pin "2") (pinfunction "TS_2") (pintype "passive"))
    )
    (net (code "74") (name "/SWN14") (class "Default")
      (node (ref "C63") (pin "2") (pinfunction "2_2") (pintype "passive"))
      (node (ref "L8") (pin "1") (pinfunction "1_1") (pintype "passive"))
      (node (ref "Q16") (pin "1") (pinfunction "S_1") (pintype "passive"))
      (node (ref "Q16") (pin "2") (pinfunction "S_2") (pintype "passive"))
      (node (ref "Q16") (pin "3") (pinfunction "S_3") (pintype "passive"))
      (node (ref "Q23") (pin "5") (pinfunction "D_5") (pintype "passive"))
      (node (ref "Q23") (pin "6") (pinfunction "D_6") (pintype "passive"))
      (node (ref "Q23") (pin "7") (pinfunction "D_7") (pintype "passive"))
      (node (ref "Q23") (pin "8") (pinfunction "D_8") (pintype "passive"))
      (node (ref "Q24") (pin "5") (pinfunction "D_5") (pintype "passive"))
      (node (ref "Q24") (pin "6") (pinfunction "D_6") (pintype "passive"))
      (node (ref "Q24") (pin "7") (pinfunction "D_7") (pintype "passive"))
      (node (ref "Q24") (pin "8") (pinfunction "D_8") (pintype "passive"))
      (node (ref "U18") (pin "2") (pinfunction "TS_2") (pintype "passive"))
    )
    (net (code "75") (name "/SWN15") (class "Default")
      (node (ref "C95") (pin "2") (pinfunction "2_2") (pintype "passive"))
      (node (ref "L12") (pin "1") (pinfunction "1_1") (pintype "passive"))
      (node (ref "Q28") (pin "1") (pinfunction "S_1") (pintype "passive"))
      (node (ref "Q28") (pin "2") (pinfunction "S_2") (pintype "passive"))
      (node (ref "Q28") (pin "3") (pinfunction "S_3") (pintype "passive"))
      (node (ref "Q35") (pin "5") (pinfunction "D_5") (pintype "passive"))
      (node (ref "Q35") (pin "6") (pinfunction "D_6") (pintype "passive"))
      (node (ref "Q35") (pin "7") (pinfunction "D_7") (pintype "passive"))
      (node (ref "Q35") (pin "8") (pinfunction "D_8") (pintype "passive"))
      (node (ref "Q36") (pin "5") (pinfunction "D_5") (pintype "passive"))
      (node (ref "Q36") (pin "6") (pinfunction "D_6") (pintype "passive"))
      (node (ref "Q36") (pin "7") (pinfunction "D_7") (pintype "passive"))
      (node (ref "Q36") (pin "8") (pinfunction "D_8") (pintype "passive"))
      (node (ref "U22") (pin "2") (pinfunction "TS_2") (pintype "passive"))
    )
    (net (code "76") (name "/SWN16") (class "Default")
      (node (ref "C127") (pin "2") (pinfunction "2_2") (pintype "passive"))
      (node (ref "L16") (pin "1") (pinfunction "1_1") (pintype "passive"))
      (node (ref "Q40") (pin "1") (pinfunction "S_1") (pintype "passive"))
      (node (ref "Q40") (pin "2") (pinfunction "S_2") (pintype "passive"))
      (node (ref "Q40") (pin "3") (pinfunction "S_3") (pintype "passive"))
      (node (ref "Q47") (pin "5") (pinfunction "D_5") (pintype "passive"))
      (node (ref "Q47") (pin "6") (pinfunction "D_6") (pintype "passive"))
      (node (ref "Q47") (pin "7") (pinfunction "D_7") (pintype "passive"))
      (node (ref "Q47") (pin "8") (pinfunction "D_8") (pintype "passive"))
      (node (ref "Q48") (pin "5") (pinfunction "D_5") (pintype "passive"))
      (node (ref "Q48") (pin "6") (pinfunction "D_6") (pintype "passive"))
      (node (ref "Q48") (pin "7") (pinfunction "D_7") (pintype "passive"))
      (node (ref "Q48") (pin "8") (pinfunction "D_8") (pintype "passive"))
      (node (ref "U26") (pin "2") (pinfunction "TS_2") (pintype "passive"))
    )
    (net (code "77") (name "GND") (class "Default")
      (node (ref "C100") (pin "1") (pinfunction "1_1") (pintype "passive"))
      (node (ref "C101") (pin "1") (pinfunction "1_1") (pintype "passive"))
      (node (ref "C102") (pin "1") (pinfunction "1_1") (pintype "passive"))
      (node (ref "C103") (pin "1") (pinfunction "1_1") (pintype "passive"))
      (node (ref "C104") (pin "1") (pinfunction "1_1") (pintype "passive"))
      (node (ref "C105") (pin "1") (pinfunction "1_1") (pintype "passive"))
      (node (ref "C106") (pin "1") (pinfunction "1_1") (pintype "passive"))
      (node (ref "C107") (pin "1") (pinfunction "1_1") (pintype "passive"))
      (node (ref "C108") (pin "1") (pinfunction "1_1") (pintype "passive"))
      (node (ref "C109") (pin "1") (pinfunction "1_1") (pintype "passive"))
      (node (ref "C110") (pin "1") (pinfunction "1_1") (pintype "passive"))
      (node (ref "C111") (pin "1") (pinfunction "1_1") (pintype "passive"))
      (node (ref "C112") (pin "1") (pinfunction "1_1") (pintype "passive"))
      (node (ref "C113") (pin "1") (pinfunction "1_1") (pintype "passive"))
      (node (ref "C114") (pin "1") (pinfunction "1_1") (pintype "passive"))
      (node (ref "C115") (pin "1") (pinfunction "1_1") (pintype "passive"))
      (node (ref "C116") (pin "1") (pinfunction "1_1") (pintype "passive"))
      (node (ref "C117") (pin "1") (pinfunction "1_1") (pintype "passive"))
      (node (ref "C118") (pin "1") (pinfunction "1_1") (pintype "passive"))
      (node (ref "C119") (pin "1") (pinfunction "1_1") (pintype "passive"))
      (node (ref "C120") (pin "2") (pinfunction "2_2") (pintype "passive"))
      (node (ref "C121") (pin "2") (pinfunction "2_2") (pintype "passive"))
      (node (ref "C122") (pin "2") (pinfunction "2_2") (pintype "passive"))
      (node (ref "C123") (pin "2") (pinfunction "2_2") (pintype "passive"))
      (node (ref "C128") (pin "1") (pinfunction "1_1") (pintype "passive"))
      (node (ref "C129") (pin "1") (pinfunction "1_1") (pintype "passive"))
      (node (ref "C130") (pin "1") (pinfunction "1_1") (pintype "passive"))
      (node (ref "C131") (pin "1") (pinfunction "1_1") (pintype "passive"))
      (node (ref "C132") (pin "1") (pinfunction "1_1") (pintype "passive"))
      (node (ref "C133") (pin "1") (pinfunction "1_1") (pintype "passive"))
      (node (ref "C134") (pin "1") (pinfunction "1_1") (pintype "passive"))
      (node (ref "C135") (pin "1") (pinfunction "1_1") (pintype "passive"))
      (node (ref "C136") (pin "1") (pinfunction "1_1") (pintype "passive"))
      (node (ref "C137") (pin "1") (pinfunction "1_1") (pintype "passive"))
      (node (ref "C138") (pin "1") (pinfunction "1_1") (pintype "passive"))
      (node (ref "C139") (pin "1") (pinfunction "1_1") (pintype "passive"))
      (node (ref "C140") (pin "1") (pinfunction "1_1") (pintype "passive"))
      (node (ref "C141") (pin "1") (pinfunction "1_1") (pintype "passive"))
      (node (ref "C142") (pin "1") (pinfunction "1_1") (pintype "passive"))
      (node (ref "C143") (pin "1") (pinfunction "1_1") (pintype "passive"))
      (node (ref "C144") (pin "1") (pinfunction "1_1") (pintype "passive"))
      (node (ref "C145") (pin "1") (pinfunction "1_1") (pintype "passive"))
      (node (ref "C146") (pin "1") (pinfunction "1_1") (pintype "passive"))
      (node (ref "C147") (pin "1") (pinfunction "1_1") (pintype "passive"))
      (node (ref "C20") (pin "1") (pinfunction "1_1") (pintype "passive"))
      (node (ref "C21") (pin "1") (pinfunction "1_1") (pintype "passive"))
      (node (ref "C22") (pin "1") (pinfunction "1_1") (pintype "passive"))
      (node (ref "C23") (pin "1") (pinfunction "1_1") (pintype "passive"))
      (node (ref "C236") (pin "1") (pinfunction "1_1") (pintype "passive"))
      (node (ref "C24") (pin "2") (pinfunction "2_2") (pintype "passive"))
      (node (ref "C25") (pin "2") (pinfunction "2_2") (pintype "passive"))
      (node (ref "C26") (pin "2") (pinfunction "2_2") (pintype "passive"))
      (node (ref "C27") (pin "2") (pinfunction "2_2") (pintype "passive"))
      (node (ref "C32") (pin "1") (pinfunction "1_1") (pintype "passive"))
      (node (ref "C33") (pin "1") (pinfunction "1_1") (pintype "passive"))
      (node (ref "C34") (pin "1") (pinfunction "1_1") (pintype "passive"))
      (node (ref "C348") (pin "1") (pinfunction "1_1") (pintype "passive"))
      (node (ref "C349") (pin "1") (pinfunction "1_1") (pintype "passive"))
      (node (ref "C35") (pin "1") (pinfunction "1_1") (pintype "passive"))
      (node (ref "C350") (pin "1") (pinfunction "1_1") (pintype "passive"))
      (node (ref "C351") (pin "1") (pinfunction "1_1") (pintype "passive"))
      (node (ref "C352") (pin "1") (pinfunction "1_1") (pintype "passive"))
      (node (ref "C353") (pin "1") (pinfunction "1_1") (pintype "passive"))
      (node (ref "C354") (pin "1") (pinfunction "1_1") (pintype "passive"))
      (node (ref "C355") (pin "1") (pinfunction "1_1") (pintype "passive"))
      (node (ref "C356") (pin "1") (pinfunction "1_1") (pintype "passive"))
      (node (ref "C357") (pin "1") (pinfunction "1_1") (pintype "passive"))
      (node (ref "C358") (pin "1") (pinfunction "1_1") (pintype "passive"))
      (node (ref "C359") (pin "1") (pinfunction "1_1") (pintype "passive"))
      (node (ref "C360") (pin "1") (pinfunction "1_1") (pintype "passive"))
      (node (ref "C361") (pin "1") (pinfunction "1_1") (pintype "passive"))
      (node (ref "C362") (pin "1") (pinfunction "1_1") (pintype "passive"))
      (node (ref "C363") (pin "1") (pinfunction "1_1") (pintype "passive"))
      (node (ref "C364") (pin "1") (pinfunction "1_1") (pintype "passive"))
      (node (ref "C365") (pin "1") (pinfunction "1_1") (pintype "passive"))
      (node (ref "C366") (pin "1") (pinfunction "1_1") (pintype "passive"))
      (node (ref "C367") (pin "1") (pinfunction "1_1") (pintype "passive"))
      (node (ref "C368") (pin "1") (pinfunction "1_1") (pintype "passive"))
      (node (ref "C369") (pin "1") (pinfunction "1_1") (pintype "passive"))
      (node (ref "C37") (pin "1") (pinfunction "1_1") (pintype "passive"))
      (node (ref "C370") (pin "1") (pinfunction "1_1") (pintype "passive"))
      (node (ref "C371") (pin "1") (pinfunction "1_1") (pintype "passive"))
      (node (ref "C372") (pin "1") (pinfunction "1_1") (pintype "passive"))
      (node (ref "C373") (pin "1") (pinfunction "1_1") (pintype "passive"))
      (node (ref "C374") (pin "1") (pinfunction "1_1") (pintype "passive"))
      (node (ref "C375") (pin "1") (pinfunction "1_1") (pintype "passive"))
      (node (ref "C376") (pin "1") (pinfunction "1_1") (pintype "passive"))
      (node (ref "C377") (pin "1") (pinfunction "1_1") (pintype "passive"))
      (node (ref "C378") (pin "1") (pinfunction "1_1") (pintype "passive"))
      (node (ref "C379") (pin "1") (pinfunction "1_1") (pintype "passive"))
      (node (ref "C38") (pin "1") (pinfunction "1_1") (pintype "passive"))
      (node (ref "C380") (pin "1") (pinfunction "1_1") (pintype "passive"))
      (node (ref "C381") (pin "1") (pinfunction "1_1") (pintype "passive"))
      (node (ref "C382") (pin "1") (pinfunction "1_1") (pintype "passive"))
      (node (ref "C383") (pin "1") (pinfunction "1_1") (pintype "passive"))
      (node (ref "C384") (pin "1") (pinfunction "1_1") (pintype "passive"))
      (node (ref "C385") (pin "1") (pinfunction "1_1") (pintype "passive"))
      (node (ref "C386") (pin "1") (pinfunction "1_1") (pintype "passive"))
      (node (ref "C387") (pin "1") (pinfunction "1_1") (pintype "passive"))
      (node (ref "C388") (pin "1") (pinfunction "1_1") (pintype "passive"))
      (node (ref "C389") (pin "1") (pinfunction "1_1") (pintype "passive"))
      (node (ref "C39") (pin "1") (pinfunction "1_1") (pintype "passive"))
      (node (ref "C390") (pin "1") (pinfunction "1_1") (pintype "passive"))
      (node (ref "C391") (pin "1") (pinfunction "1_1") (pintype "passive"))
      (node (ref "C392") (pin "1") (pinfunction "1_1") (pintype "passive"))
      (node (ref "C393") (pin "1") (pinfunction "1_1") (pintype "passive"))
      (node (ref "C394") (pin "1") (pinfunction "1_1") (pintype "passive"))
      (node (ref "C395") (pin "1") (pinfunction "1_1") (pintype "passive"))
      (node (ref "C396") (pin "1") (pinfunction "1_1") (pintype "passive"))
      (node (ref "C397") (pin "1") (pinfunction "1_1") (pintype "passive"))
      (node (ref "C398") (pin "1") (pinfunction "1_1") (pintype "passive"))
      (node (ref "C399") (pin "1") (pinfunction "1_1") (pintype "passive"))
      (node (ref "C40") (pin "1") (pinfunction "1_1") (pintype "passive"))
      (node (ref "C400") (pin "1") (pinfunction "1_1") (pintype "passive"))
      (node (ref "C401") (pin "1") (pinfunction "1_1") (pintype "passive"))
      (node (ref "C402") (pin "1") (pinfunction "1_1") (pintype "passive"))
      (node (ref "C403") (pin "1") (pinfunction "1_1") (pintype "passive"))
      (node (ref "C404") (pin "1") (pinfunction "1_1") (pintype "passive"))
      (node (ref "C405") (pin "1") (pinfunction "1_1") (pintype "passive"))
      (node (ref "C406") (pin "1") (pinfunction "1_1") (pintype "passive"))
      (node (ref "C407") (pin "1") (pinfunction "1_1") (pintype "passive"))
      (node (ref "C408") (pin "1") (pinfunction "1_1") (pintype "passive"))
      (node (ref "C409") (pin "1") (pinfunction "1_1") (pintype "passive"))
      (node (ref "C41") (pin "1") (pinfunction "1_1") (pintype "passive"))
      (node (ref "C410") (pin "1") (pinfunction "1_1") (pintype "passive"))
      (node (ref "C411") (pin "1") (pinfunction "1_1") (pintype "passive"))
      (node (ref "C412") (pin "1") (pinfunction "1_1") (pintype "passive"))
      (node (ref "C413") (pin "1") (pinfunction "1_1") (pintype "passive"))
      (node (ref "C414") (pin "1") (pinfunction "1_1") (pintype "passive"))
      (node (ref "C415") (pin "1") (pinfunction "1_1") (pintype "passive"))
      (node (ref "C416") (pin "1") (pinfunction "1_1") (pintype "passive"))
      (node (ref "C417") (pin "1") (pinfunction "1_1") (pintype "passive"))
      (node (ref "C418") (pin "1") (pinfunction "1_1") (pintype "passive"))
      (node (ref "C419") (pin "1") (pinfunction "1_1") (pintype "passive"))
      (node (ref "C42") (pin "1") (pinfunction "1_1") (pintype "passive"))
      (node (ref "C420") (pin "1") (pinfunction "1_1") (pintype "passive"))
      (node (ref "C421") (pin "1") (pinfunction "1_1") (pintype "passive"))
      (node (ref "C422") (pin "1") (pinfunction "1_1") (pintype "passive"))
      (node (ref "C423") (pin "1") (pinfunction "1_1") (pintype "passive"))
      (node (ref "C424") (pin "1") (pinfunction "1_1") (pintype "passive"))
      (node (ref "C425") (pin "1") (pinfunction "1_1") (pintype "passive"))
      (node (ref "C426") (pin "1") (pinfunction "1_1") (pintype "passive"))
      (node (ref "C427") (pin "1") (pinfunction "1_1") (pintype "passive"))
      (node (ref "C43") (pin "1") (pinfunction "1_1") (pintype "passive"))
      (node (ref "C44") (pin "1") (pinfunction "1_1") (pintype "passive"))
      (node (ref "C45") (pin "1") (pinfunction "1_1") (pintype "passive"))
      (node (ref "C46") (pin "1") (pinfunction "1_1") (pintype "passive"))
      (node (ref "C47") (pin "1") (pinfunction "1_1") (pintype "passive"))
      (node (ref "C48") (pin "1") (pinfunction "1_1") (pintype "passive"))
      (node (ref "C49") (pin "1") (pinfunction "1_1") (pintype "passive"))
      (node (ref "C50") (pin "1") (pinfunction "1_1") (pintype "passive"))
      (node (ref "C51") (pin "1") (pinfunction "1_1") (pintype "passive"))
      (node (ref "C52") (pin "1") (pinfunction "1_1") (pintype "passive"))
      (node (ref "C53") (pin "1") (pinfunction "1_1") (pintype "passive"))
      (node (ref "C54") (pin "1") (pinfunction "1_1") (pintype "passive"))
      (node (ref "C55") (pin "1") (pinfunction "1_1") (pintype "passive"))
      (node (ref "C56") (pin "2") (pinfunction "2_2") (pintype "passive"))
      (node (ref "C57") (pin "2") (pinfunction "2_2") (pintype "passive"))
      (node (ref "C58") (pin "2") (pinfunction "2_2") (pintype "passive"))
      (node (ref "C59") (pin "2") (pinfunction "2_2") (pintype "passive"))
      (node (ref "C64") (pin "1") (pinfunction "1_1") (pintype "passive"))
      (node (ref "C65") (pin "1") (pinfunction "1_1") (pintype "passive"))
      (node (ref "C66") (pin "1") (pinfunction "1_1") (pintype "passive"))
      (node (ref "C67") (pin "1") (pinfunction "1_1") (pintype "passive"))
      (node (ref "C68") (pin "1") (pinfunction "1_1") (pintype "passive"))
      (node (ref "C69") (pin "1") (pinfunction "1_1") (pintype "passive"))
      (node (ref "C70") (pin "1") (pinfunction "1_1") (pintype "passive"))
      (node (ref "C71") (pin "1") (pinfunction "1_1") (pintype "passive"))
      (node (ref "C72") (pin "1") (pinfunction "1_1") (pintype "passive"))
      (node (ref "C73") (pin "1") (pinfunction "1_1") (pintype "passive"))
      (node (ref "C74") (pin "1") (pinfunction "1_1") (pintype "passive"))
      (node (ref "C75") (pin "1") (pinfunction "1_1") (pintype "passive"))
      (node (ref "C76") (pin "1") (pinfunction "1_1") (pintype "passive"))
      (node (ref "C77") (pin "1") (pinfunction "1_1") (pintype "passive"))
      (node (ref "C78") (pin "1") (pinfunction "1_1") (pintype "passive"))
      (node (ref "C79") (pin "1") (pinfunction "1_1") (pintype "passive"))
      (node (ref "C80") (pin "1") (pinfunction "1_1") (pintype "passive"))
      (node (ref "C81") (pin "1") (pinfunction "1_1") (pintype "passive"))
      (node (ref "C82") (pin "1") (pinfunction "1_1") (pintype "passive"))
      (node (ref "C83") (pin "1") (pinfunction "1_1") (pintype "passive"))
      (node (ref "C84") (pin "1") (pinfunction "1_1") (pintype "passive"))
      (node (ref "C85") (pin "1") (pinfunction "1_1") (pintype "passive"))
      (node (ref "C86") (pin "1") (pinfunction "1_1") (pintype "passive"))
      (node (ref "C87") (pin "1") (pinfunction "1_1") (pintype "passive"))
      (node (ref "C88") (pin "2") (pinfunction "2_2") (pintype "passive"))
      (node (ref "C89") (pin "2") (pinfunction "2_2") (pintype "passive"))
      (node (ref "C90") (pin "2") (pinfunction "2_2") (pintype "passive"))
      (node (ref "C91") (pin "2") (pinfunction "2_2") (pintype "passive"))
      (node (ref "C96") (pin "1") (pinfunction "1_1") (pintype "passive"))
      (node (ref "C97") (pin "1") (pinfunction "1_1") (pintype "passive"))
      (node (ref "C98") (pin "1") (pinfunction "1_1") (pintype "passive"))
      (node (ref "C99") (pin "1") (pinfunction "1_1") (pintype "passive"))
      (node (ref "Q10") (pin "1") (pinfunction "S_1") (pintype "passive"))
      (node (ref "Q10") (pin "2") (pinfunction "S_2") (pintype "passive"))
      (node (ref "Q10") (pin "3") (pinfunction "S_3") (pintype "passive"))
      (node (ref "Q11") (pin "1") (pinfunction "S_1") (pintype "passive"))
      (node (ref "Q11") (pin "2") (pinfunction "S_2") (pintype "passive"))
      (node (ref "Q11") (pin "3") (pinfunction "S_3") (pintype "passive"))
      (node (ref "Q12") (pin "1") (pinfunction "S_1") (pintype "passive"))
      (node (ref "Q12") (pin "2") (pinfunction "S_2") (pintype "passive"))
      (node (ref "Q12") (pin "3") (pinfunction "S_3") (pintype "passive"))
      (node (ref "Q17") (pin "1") (pinfunction "S_1") (pintype "passive"))
      (node (ref "Q17") (pin "2") (pinfunction "S_2") (pintype "passive"))
      (node (ref "Q17") (pin "3") (pinfunction "S_3") (pintype "passive"))
      (node (ref "Q18") (pin "1") (pinfunction "S_1") (pintype "passive"))
      (node (ref "Q18") (pin "2") (pinfunction "S_2") (pintype "passive"))
      (node (ref "Q18") (pin "3") (pinfunction "S_3") (pintype "passive"))
      (node (ref "Q19") (pin "1") (pinfunction "S_1") (pintype "passive"))
      (node (ref "Q19") (pin "2") (pinfunction "S_2") (pintype "passive"))
      (node (ref "Q19") (pin "3") (pinfunction "S_3") (pintype "passive"))
      (node (ref "Q20") (pin "1") (pinfunction "S_1") (pintype "passive"))
      (node (ref "Q20") (pin "2") (pinfunction "S_2") (pintype "passive"))
      (node (ref "Q20") (pin "3") (pinfunction "S_3") (pintype "passive"))
      (node (ref "Q21") (pin "1") (pinfunction "S_1") (pintype "passive"))
      (node (ref "Q21") (pin "2") (pinfunction "S_2") (pintype "passive"))
      (node (ref "Q21") (pin "3") (pinfunction "S_3") (pintype "passive"))
      (node (ref "Q22") (pin "1") (pinfunction "S_1") (pintype "passive"))
      (node (ref "Q22") (pin "2") (pinfunction "S_2") (pintype "passive"))
      (node (ref "Q22") (pin "3") (pinfunction "S_3") (pintype "passive"))
      (node (ref "Q23") (pin "1") (pinfunction "S_1") (pintype "passive"))
      (node (ref "Q23") (pin "2") (pinfunction "S_2") (pintype "passive"))
      (node (ref "Q23") (pin "3") (pinfunction "S_3") (pintype "passive"))
      (node (ref "Q24") (pin "1") (pinfunction "S_1") (pintype "passive"))
      (node (ref "Q24") (pin "2") (pinfunction "S_2") (pintype "passive"))
      (node (ref "Q24") (pin "3") (pinfunction "S_3") (pintype "passive"))
      (node (ref "Q29") (pin "1") (pinfunction "S_1") (pintype "passive"))
      (node (ref "Q29") (pin "2") (pinfunction "S_2") (pintype "passive"))
      (node (ref "Q29") (pin "3") (pinfunction "S_3") (pintype "passive"))
      (node (ref "Q30") (pin "1") (pinfunction "S_1") (pintype "passive"))
      (node (ref "Q30") (pin "2") (pinfunction "S_2") (pintype "passive"))
      (node (ref "Q30") (pin "3") (pinfunction "S_3") (pintype "passive"))
      (node (ref "Q31") (pin "1") (pinfunction "S_1") (pintype "passive"))
      (node (ref "Q31") (pin "2") (pinfunction "S_2") (pintype "passive"))
      (node (ref "Q31") (pin "3") (pinfunction "S_3") (pintype "passive"))
      (node (ref "Q32") (pin "1") (pinfunction "S_1") (pintype "passive"))
      (node (ref "Q32") (pin "2") (pinfunction "S_2") (pintype "passive"))
      (node (ref "Q32") (pin "3") (pinfunction "S_3") (pintype "passive"))
      (node (ref "Q33") (pin "1") (pinfunction "S_1") (pintype "passive"))
      (node (ref "Q33") (pin "2") (pinfunction "S_2") (pintype "passive"))
      (node (ref "Q33") (pin "3") (pinfunction "S_3") (pintype "passive"))
      (node (ref "Q34") (pin "1") (pinfunction "S_1") (pintype "passive"))
      (node (ref "Q34") (pin "2") (pinfunction "S_2") (pintype "passive"))
      (node (ref "Q34") (pin "3") (pinfunction "S_3") (pintype "passive"))
      (node (ref "Q35") (pin "1") (pinfunction "S_1") (pintype "passive"))
      (node (ref "Q35") (pin "2") (pinfunction "S_2") (pintype "passive"))
      (node (ref "Q35") (pin "3") (pinfunction "S_3") (pintype "passive"))
      (node (ref "Q36") (pin "1") (pinfunction "S_1") (pintype "passive"))
      (node (ref "Q36") (pin "2") (pinfunction "S_2") (pintype "passive"))
      (node (ref "Q36") (pin "3") (pinfunction "S_3") (pintype "passive"))
      (node (ref "Q41") (pin "1") (pinfunction "S_1") (pintype "passive"))
      (node (ref "Q41") (pin "2") (pinfunction "S_2") (pintype "passive"))
      (node (ref "Q41") (pin "3") (pinfunction "S_3") (pintype "passive"))
      (node (ref "Q42") (pin "1") (pinfunction "S_1") (pintype "passive"))
      (node (ref "Q42") (pin "2") (pinfunction "S_2") (pintype "passive"))
      (node (ref "Q42") (pin "3") (pinfunction "S_3") (pintype "passive"))
      (node (ref "Q43") (pin "1") (pinfunction "S_1") (pintype "passive"))
      (node (ref "Q43") (pin "2") (pinfunction "S_2") (pintype "passive"))
      (node (ref "Q43") (pin "3") (pinfunction "S_3") (pintype "passive"))
      (node (ref "Q44") (pin "1") (pinfunction "S_1") (pintype "passive"))
      (node (ref "Q44") (pin "2") (pinfunction "S_2") (pintype "passive"))
      (node (ref "Q44") (pin "3") (pinfunction "S_3") (pintype "passive"))
      (node (ref "Q45") (pin "1") (pinfunction "S_1") (pintype "passive"))
      (node (ref "Q45") (pin "2") (pinfunction "S_2") (pintype "passive"))
      (node (ref "Q45") (pin "3") (pinfunction "S_3") (pintype "passive"))
      (node (ref "Q46") (pin "1") (pinfunction "S_1") (pintype "passive"))
      (node (ref "Q46") (pin "2") (pinfunction "S_2") (pintype "passive"))
      (node (ref "Q46") (pin "3") (pinfunction "S_3") (pintype "passive"))
      (node (ref "Q47") (pin "1") (pinfunction "S_1") (pintype "passive"))
      (node (ref "Q47") (pin "2") (pinfunction "S_2") (pintype "passive"))
      (node (ref "Q47") (pin "3") (pinfunction "S_3") (pintype "passive"))
      (node (ref "Q48") (pin "1") (pinfunction "S_1") (pintype "passive"))
      (node (ref "Q48") (pin "2") (pinfunction "S_2") (pintype "passive"))
      (node (ref "Q48") (pin "3") (pinfunction "S_3") (pintype "passive"))
      (node (ref "Q5") (pin "1") (pinfunction "S_1") (pintype "passive"))
      (node (ref "Q5") (pin "2") (pinfunction "S_2") (pintype "passive"))
      (node (ref "Q5") (pin "3") (pinfunction "S_3") (pintype "passive"))
      (node (ref "Q6") (pin "1") (pinfunction "S_1") (pintype "passive"))
      (node (ref "Q6") (pin "2") (pinfunction "S_2") (pintype "passive"))
      (node (ref "Q6") (pin "3") (pinfunction "S_3") (pintype "passive"))
      (node (ref "Q7") (pin "1") (pinfunction "S_1") (pintype "passive"))
      (node (ref "Q7") (pin "2") (pinfunction "S_2") (pintype "passive"))
      (node (ref "Q7") (pin "3") (pinfunction "S_3") (pintype "passive"))
      (node (ref "Q8") (pin "1") (pinfunction "S_1") (pintype "passive"))
      (node (ref "Q8") (pin "2") (pinfunction "S_2") (pintype "passive"))
      (node (ref "Q8") (pin "3") (pinfunction "S_3") (pintype "passive"))
      (node (ref "Q9") (pin "1") (pinfunction "S_1") (pintype "passive"))
      (node (ref "Q9") (pin "2") (pinfunction "S_2") (pintype "passive"))
      (node (ref "Q9") (pin "3") (pinfunction "S_3") (pintype "passive"))
      (node (ref "U11") (pin "4") (pinfunction "GND_4") (pintype "passive"))
      (node (ref "U11") (pin "9") (pinfunction "EP_9") (pintype "passive"))
      (node (ref "U12") (pin "4") (pinfunction "GND_4") (pintype "passive"))
      (node (ref "U12") (pin "9") (pinfunction "EP_9") (pintype "passive"))
      (node (ref "U13") (pin "4") (pinfunction "GND_4") (pintype "passive"))
      (node (ref "U13") (pin "9") (pinfunction "EP_9") (pintype "passive"))
      (node (ref "U14") (pin "4") (pinfunction "GND_4") (pintype "passive"))
      (node (ref "U14") (pin "9") (pinfunction "EP_9") (pintype "passive"))
      (node (ref "U15") (pin "4") (pinfunction "GND_4") (pintype "passive"))
      (node (ref "U15") (pin "9") (pinfunction "EP_9") (pintype "passive"))
      (node (ref "U16") (pin "4") (pinfunction "GND_4") (pintype "passive"))
      (node (ref "U16") (pin "9") (pinfunction "EP_9") (pintype "passive"))
      (node (ref "U17") (pin "4") (pinfunction "GND_4") (pintype "passive"))
      (node (ref "U17") (pin "9") (pinfunction "EP_9") (pintype "passive"))
      (node (ref "U18") (pin "4") (pinfunction "GND_4") (pintype "passive"))
      (node (ref "U18") (pin "9") (pinfunction "EP_9") (pintype "passive"))
      (node (ref "U19") (pin "4") (pinfunction "GND_4") (pintype "passive"))
      (node (ref "U19") (pin "9") (pinfunction "EP_9") (pintype "passive"))
      (node (ref "U20") (pin "4") (pinfunction "GND_4") (pintype "passive"))
      (node (ref "U20") (pin "9") (pinfunction "EP_9") (pintype "passive"))
      (node (ref "U21") (pin "4") (pinfunction "GND_4") (pintype "passive"))
      (node (ref "U21") (pin "9") (pinfunction "EP_9") (pintype "passive"))
      (node (ref "U22") (pin "4") (pinfunction "GND_4") (pintype "passive"))
      (node (ref "U22") (pin "9") (pinfunction "EP_9") (pintype "passive"))
      (node (ref "U23") (pin "4") (pinfunction "GND_4") (pintype "passive"))
      (node (ref "U23") (pin "9") (pinfunction "EP_9") (pintype "passive"))
      (node (ref "U24") (pin "4") (pinfunction "GND_4") (pintype "passive"))
      (node (ref "U24") (pin "9") (pinfunction "EP_9") (pintype "passive"))
      (node (ref "U25") (pin "4") (pinfunction "GND_4") (pintype "passive"))
      (node (ref "U25") (pin "9") (pinfunction "EP_9") (pintype "passive"))
      (node (ref "U26") (pin "4") (pinfunction "GND_4") (pintype "passive"))
      (node (ref "U26") (pin "9") (pinfunction "EP_9") (pintype "passive"))
    )
  )
)
